# combined-v2.net
KiCad netlist of a schematic drawn in EAGLE
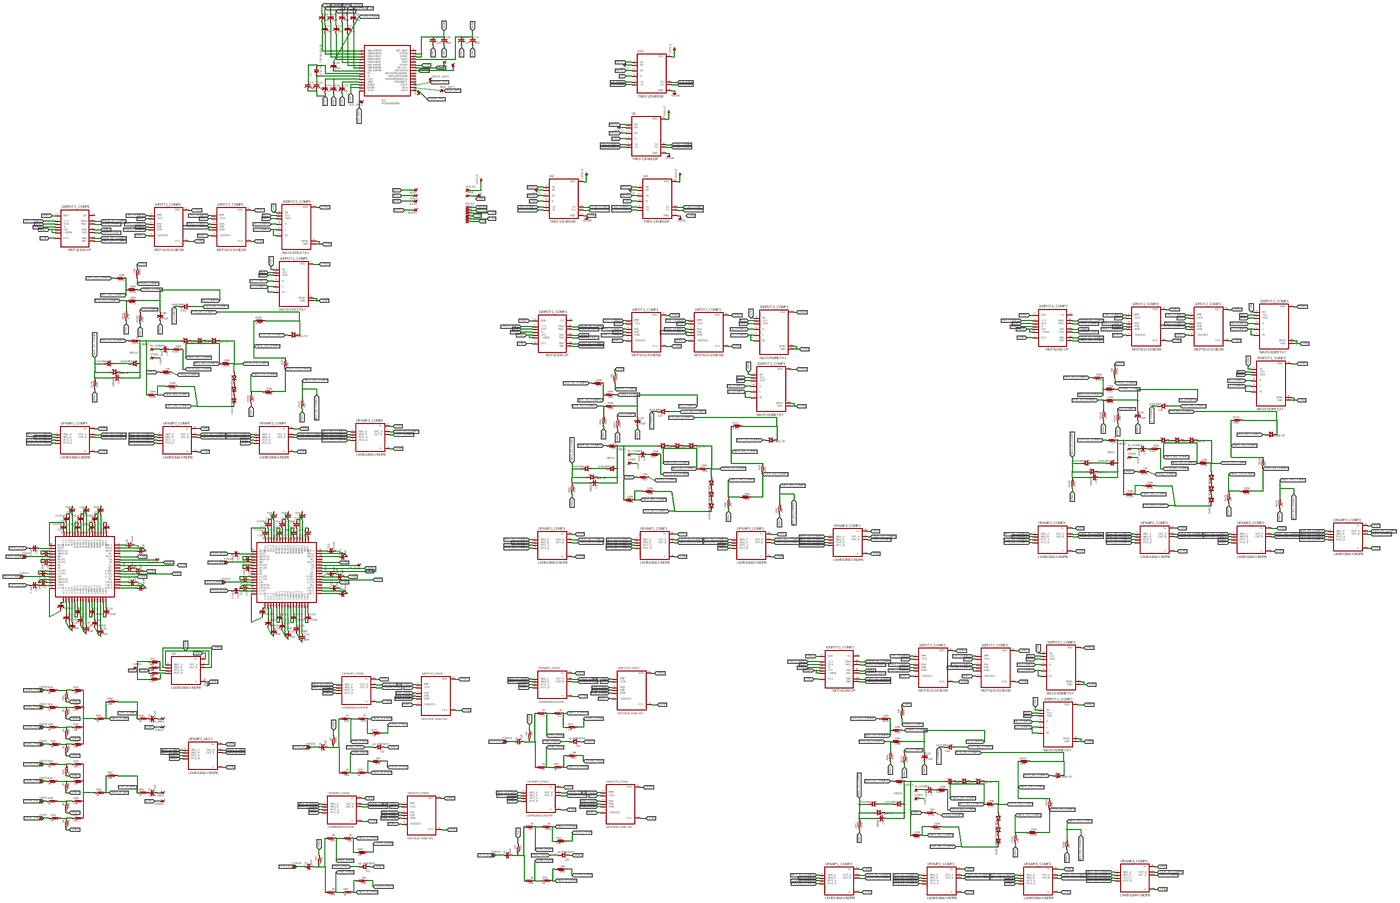
[diagram p0: schematic, sheet 1, overview]
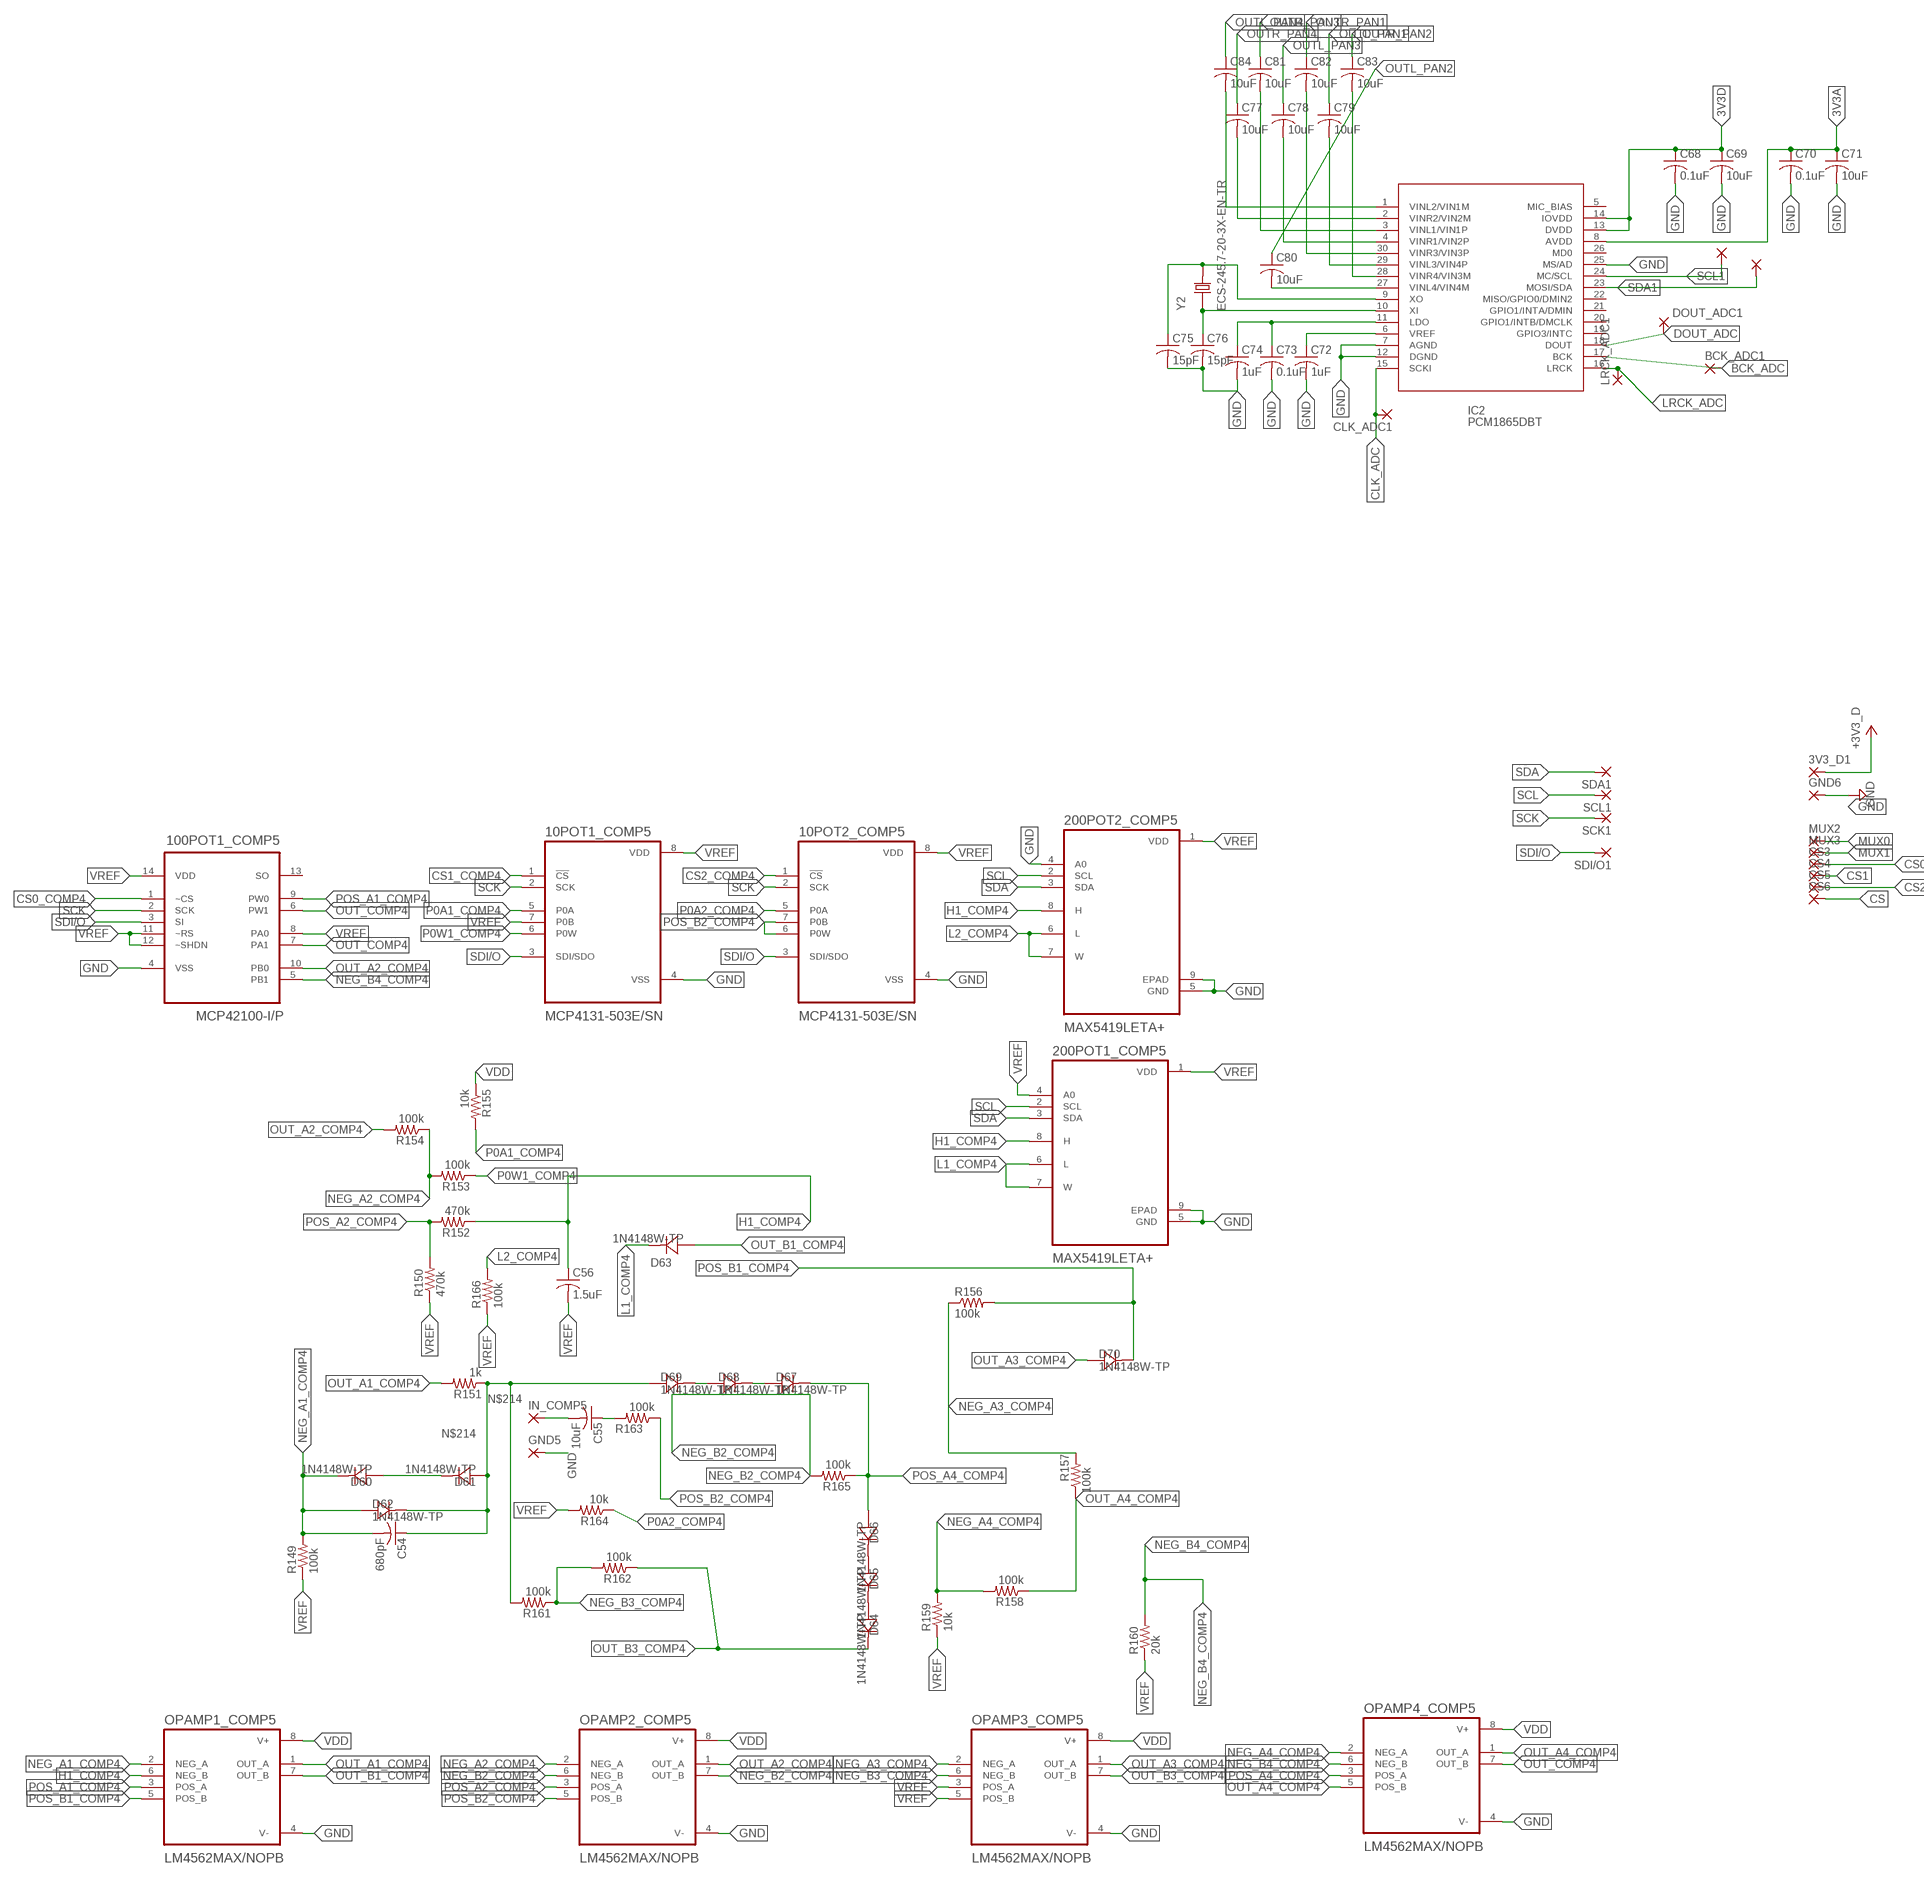
[diagram p1: schematic, sheet 1, part 1 of 5]
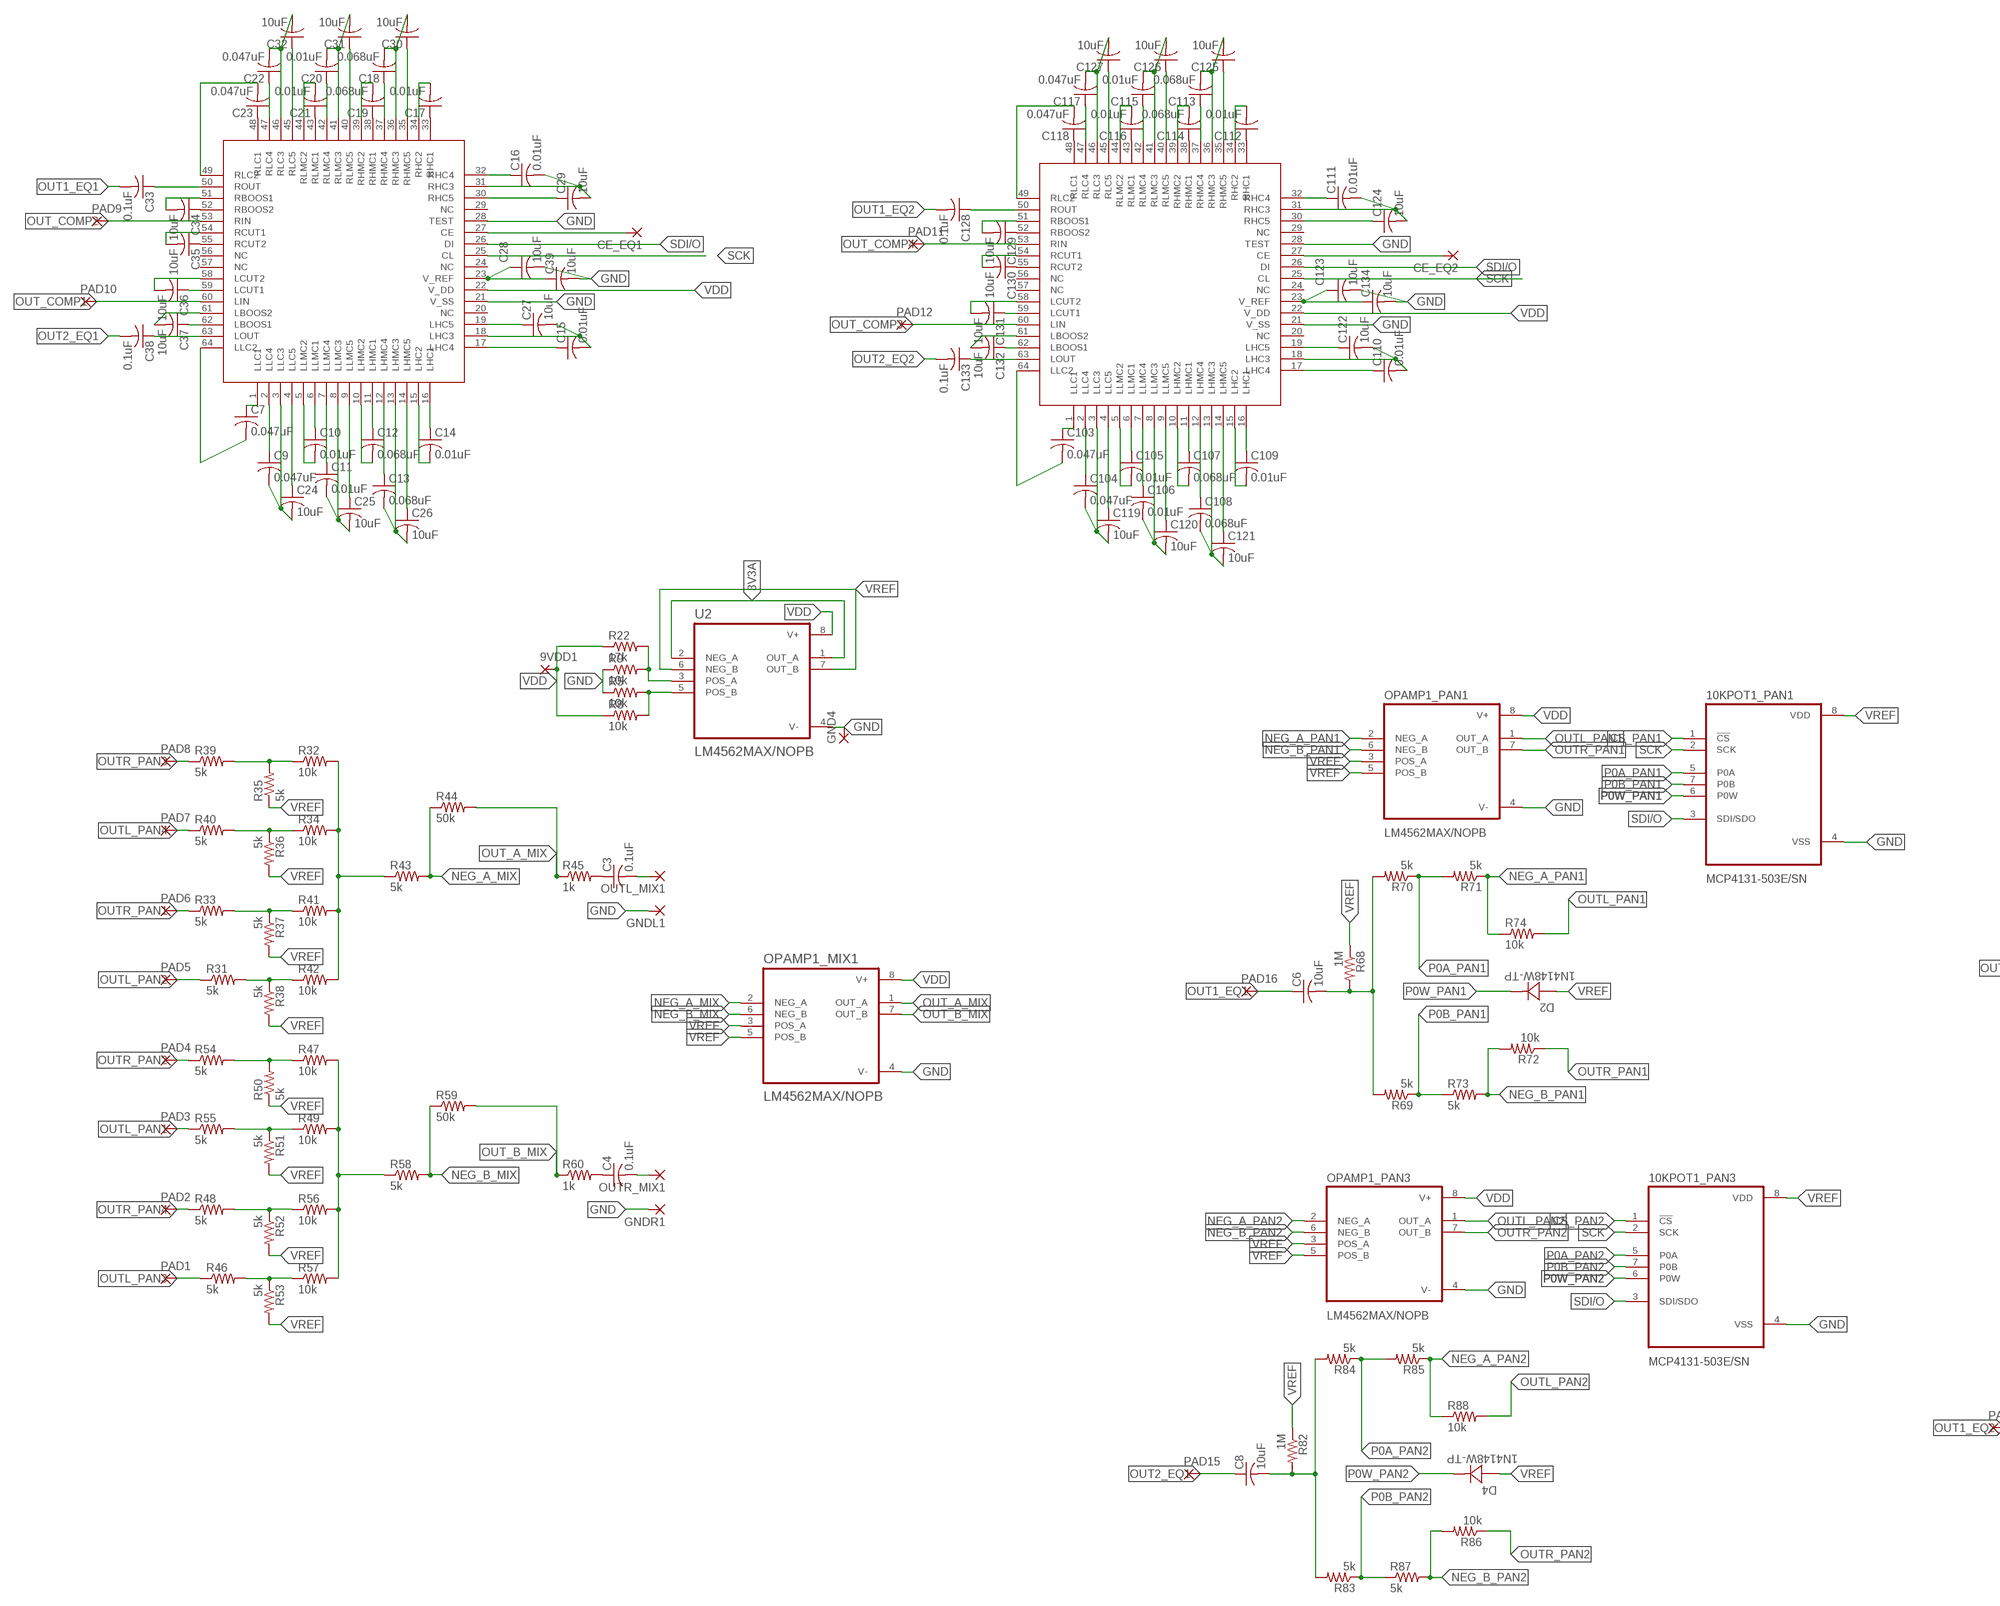
[diagram p2: schematic, sheet 1, part 2 of 5]
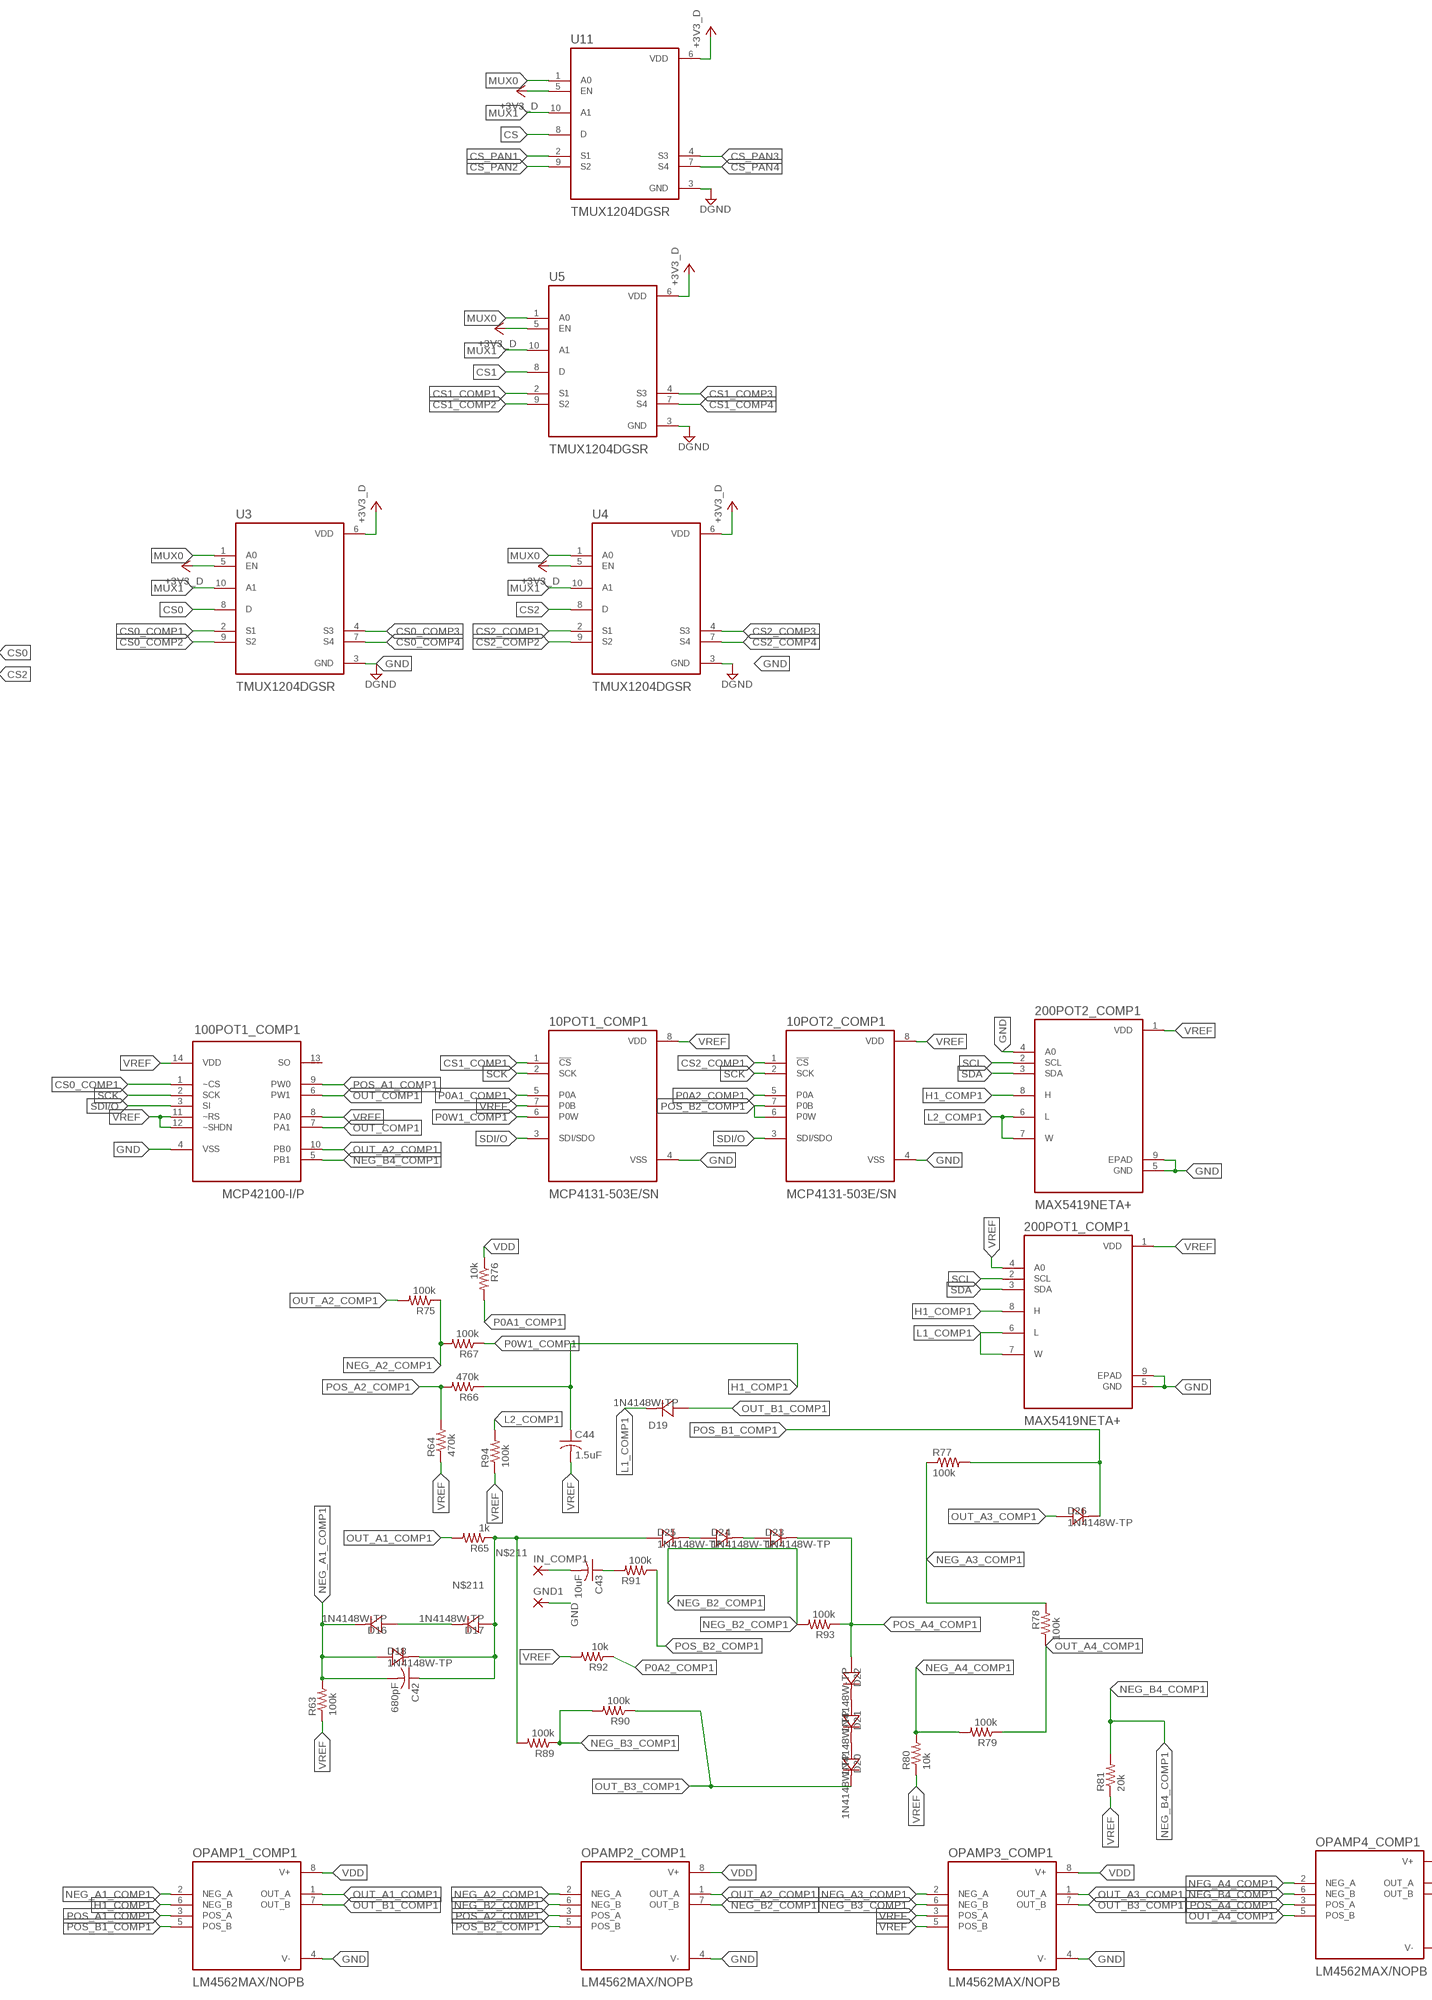
[diagram p3: schematic, sheet 1, part 3 of 5]
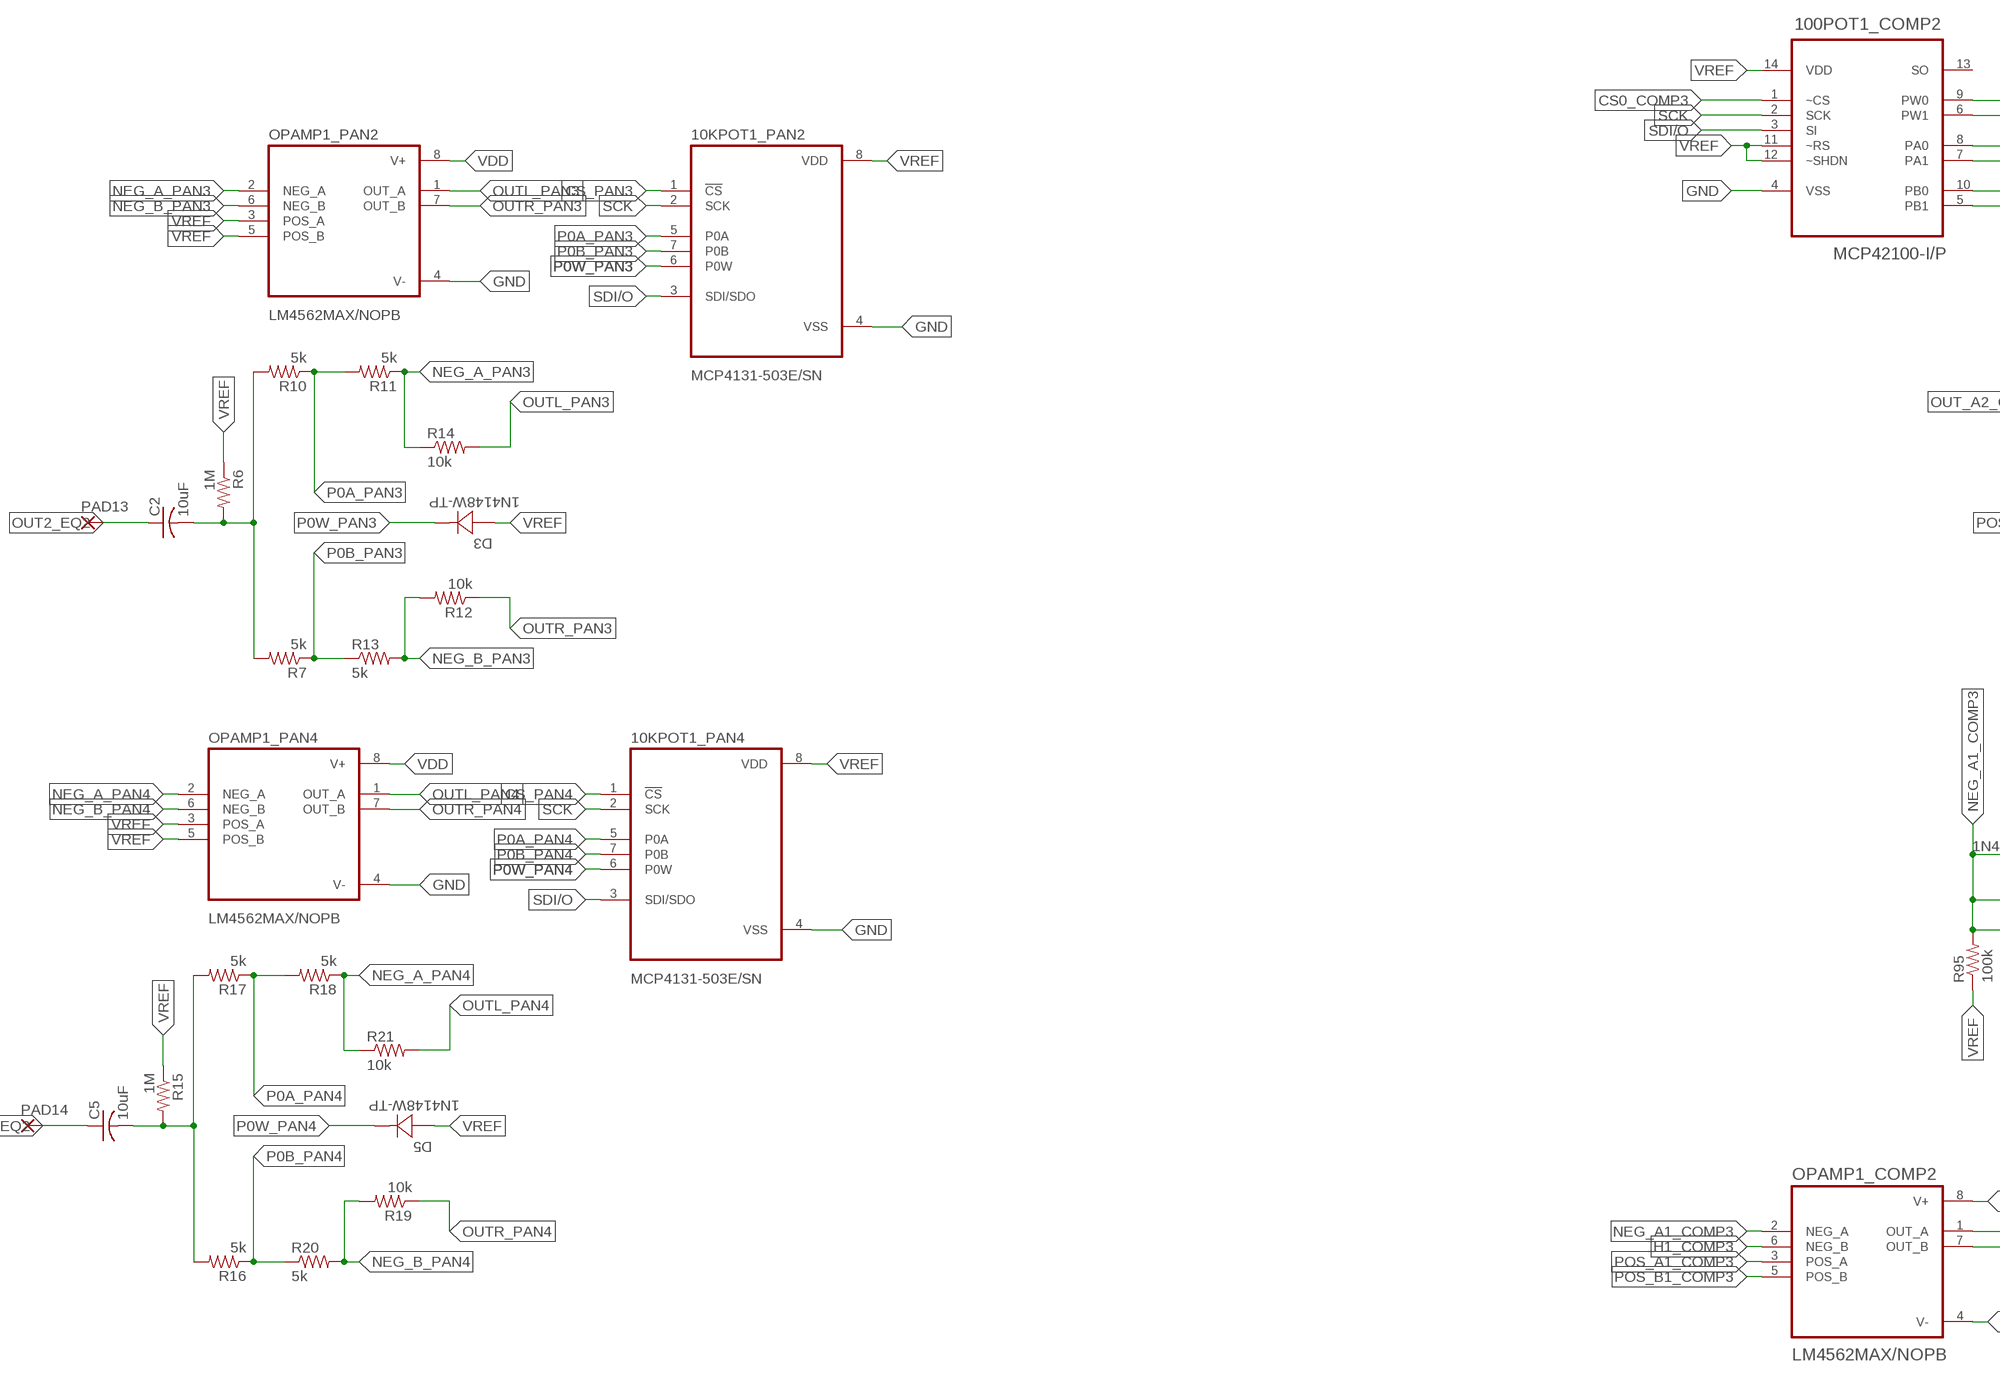
[diagram p4: schematic, sheet 1, part 4 of 5]
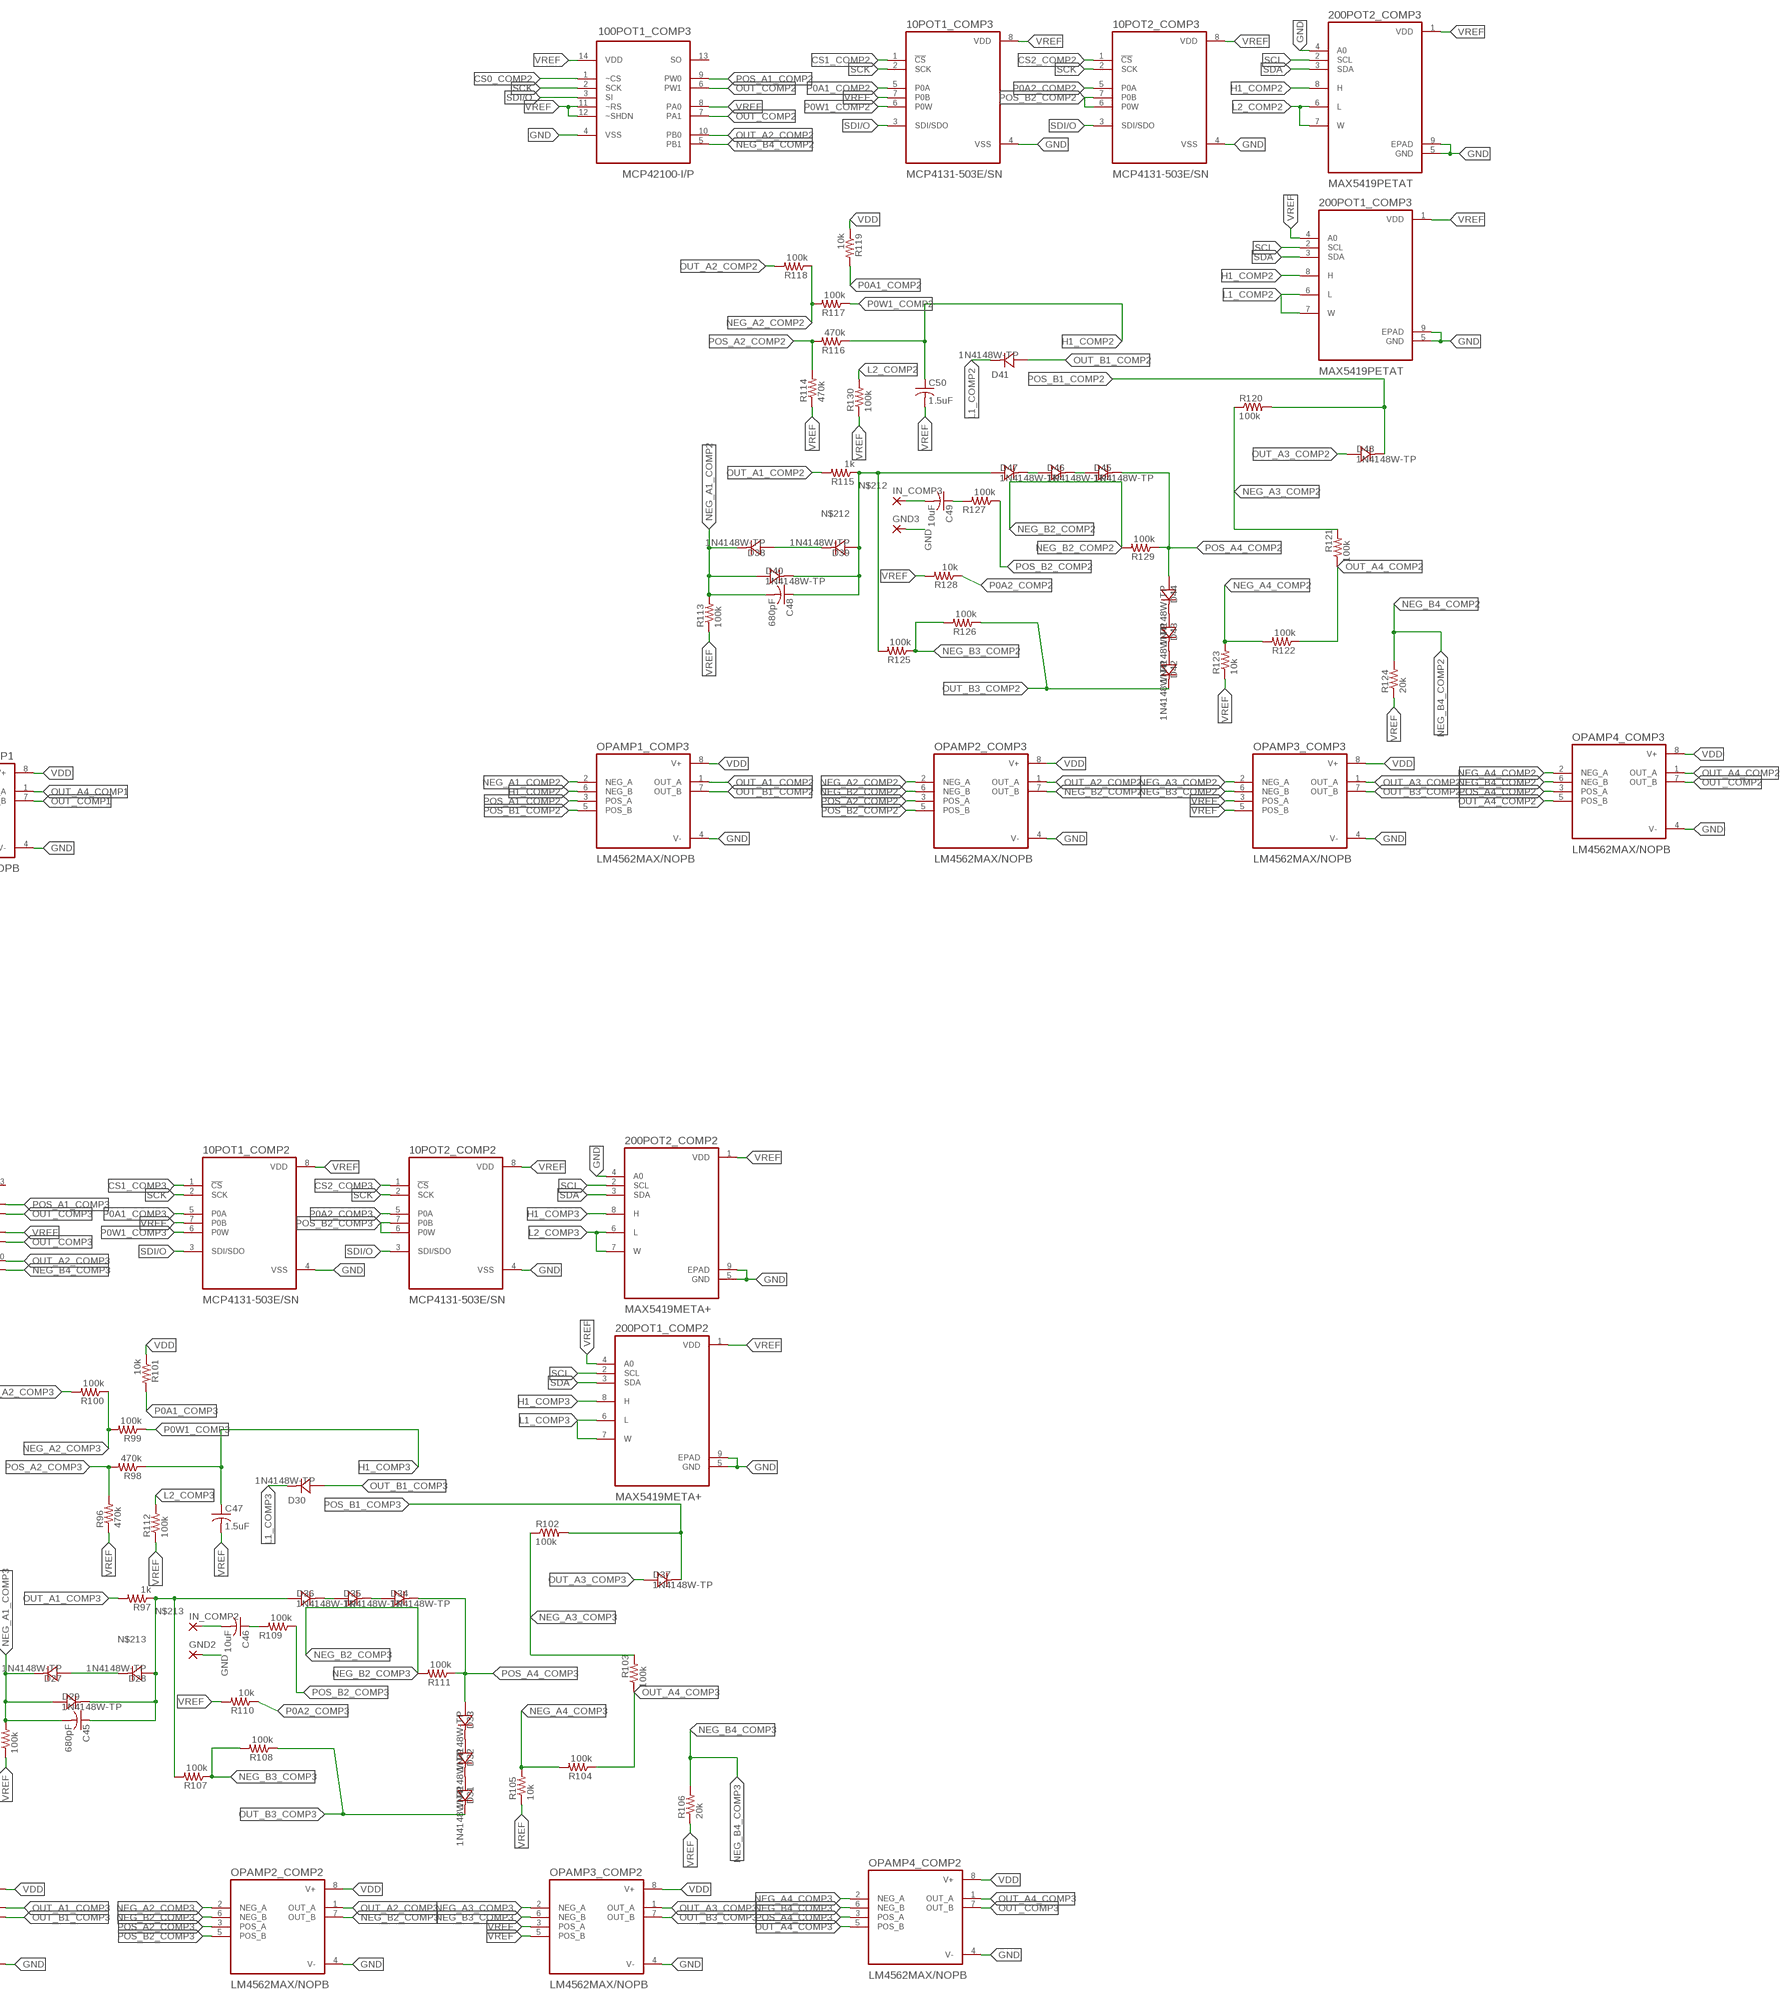
[diagram p5: schematic, sheet 1, part 5 of 5]

(export (version "E")
  (design (tool "Eeschema 10.0.6"))
  (components
    (comp (ref "3V3_D1")
      (value "SMD2")
      (footprint "eagle-import:SMD1,27-2,54")
      (libsource (lib "eagle-import") (part "SMD2"))
    )
    (comp (ref "9VDD1")
      (value "SMD2")
      (footprint "eagle-import:SMD1,27-2,54")
      (libsource (lib "eagle-import") (part "SMD2"))
    )
    (comp (ref "10KPOT1_PAN1")
      (value "MCP4131-503E/SN")
      (footprint "eagle-import:SOIC127P599X175-8N")
      (fields (field (name "MF") "Microchip") (field (name "SPICEPREFIX") "X"))
      (libsource (lib "eagle-import") (part "MCP4131-503E/SN"))
    )
    (comp (ref "10KPOT1_PAN2")
      (value "MCP4131-503E/SN")
      (footprint "eagle-import:SOIC127P599X175-8N")
      (fields (field (name "MF") "Microchip") (field (name "SPICEPREFIX") "X"))
      (libsource (lib "eagle-import") (part "MCP4131-503E/SN"))
    )
    (comp (ref "10KPOT1_PAN3")
      (value "MCP4131-503E/SN")
      (footprint "eagle-import:SOIC127P599X175-8N")
      (fields (field (name "MF") "Microchip") (field (name "SPICEPREFIX") "X"))
      (libsource (lib "eagle-import") (part "MCP4131-503E/SN"))
    )
    (comp (ref "10KPOT1_PAN4")
      (value "MCP4131-503E/SN")
      (footprint "eagle-import:SOIC127P599X175-8N")
      (fields (field (name "MF") "Microchip") (field (name "SPICEPREFIX") "X"))
      (libsource (lib "eagle-import") (part "MCP4131-503E/SN"))
    )
    (comp (ref "10POT1_COMP1")
      (value "MCP4131-503E/SN")
      (footprint "eagle-import:SOIC127P599X175-8N")
      (fields (field (name "MF") "Microchip"))
      (libsource (lib "eagle-import") (part "MCP4131-503E/SN"))
    )
    (comp (ref "10POT1_COMP2")
      (value "MCP4131-503E/SN")
      (footprint "eagle-import:SOIC127P599X175-8N")
      (fields (field (name "MF") "Microchip"))
      (libsource (lib "eagle-import") (part "MCP4131-503E/SN"))
    )
    (comp (ref "10POT1_COMP3")
      (value "MCP4131-503E/SN")
      (footprint "eagle-import:SOIC127P599X175-8N")
      (fields (field (name "MF") "Microchip"))
      (libsource (lib "eagle-import") (part "MCP4131-503E/SN"))
    )
    (comp (ref "10POT1_COMP5")
      (value "MCP4131-503E/SN")
      (footprint "eagle-import:SOIC127P599X175-8N")
      (fields (field (name "MF") "Microchip"))
      (libsource (lib "eagle-import") (part "MCP4131-503E/SN"))
    )
    (comp (ref "10POT2_COMP1")
      (value "MCP4131-503E/SN")
      (footprint "eagle-import:SOIC127P599X175-8N")
      (fields (field (name "MF") "Microchip"))
      (libsource (lib "eagle-import") (part "MCP4131-503E/SN"))
    )
    (comp (ref "10POT2_COMP2")
      (value "MCP4131-503E/SN")
      (footprint "eagle-import:SOIC127P599X175-8N")
      (fields (field (name "MF") "Microchip"))
      (libsource (lib "eagle-import") (part "MCP4131-503E/SN"))
    )
    (comp (ref "10POT2_COMP3")
      (value "MCP4131-503E/SN")
      (footprint "eagle-import:SOIC127P599X175-8N")
      (fields (field (name "MF") "Microchip"))
      (libsource (lib "eagle-import") (part "MCP4131-503E/SN"))
    )
    (comp (ref "10POT2_COMP5")
      (value "MCP4131-503E/SN")
      (footprint "eagle-import:SOIC127P599X175-8N")
      (fields (field (name "MF") "Microchip"))
      (libsource (lib "eagle-import") (part "MCP4131-503E/SN"))
    )
    (comp (ref "100POT1_COMP1")
      (value "MCP42100-I/P")
      (footprint "eagle-import:DIP254P762X432-14")
      (fields (field (name "MF") "Microchip"))
      (libsource (lib "eagle-import") (part "MCP42100-I/P"))
    )
    (comp (ref "100POT1_COMP2")
      (value "MCP42100-I/P")
      (footprint "eagle-import:DIP254P762X432-14")
      (fields (field (name "MF") "Microchip"))
      (libsource (lib "eagle-import") (part "MCP42100-I/P"))
    )
    (comp (ref "100POT1_COMP3")
      (value "MCP42100-I/P")
      (footprint "eagle-import:DIP254P762X432-14")
      (fields (field (name "MF") "Microchip"))
      (libsource (lib "eagle-import") (part "MCP42100-I/P"))
    )
    (comp (ref "100POT1_COMP5")
      (value "MCP42100-I/P")
      (footprint "eagle-import:DIP254P762X432-14")
      (fields (field (name "MF") "Microchip"))
      (libsource (lib "eagle-import") (part "MCP42100-I/P"))
    )
    (comp (ref "200POT1_COMP1")
      (value "MAX5419NETA+")
      (footprint "eagle-import:SON65P300X300X80-9N")
      (fields (field (name "MF") "Analog Devices"))
      (libsource (lib "eagle-import") (part "MAX5419NETA+"))
    )
    (comp (ref "200POT1_COMP2")
      (value "MAX5419META+")
      (footprint "eagle-import:SON65P300X300X80-9N")
      (fields (field (name "MF") "Analog Devices") (field (name "MP") "MAX5419LETA+"))
      (libsource (lib "eagle-import") (part "MAX5419META+"))
    )
    (comp (ref "200POT1_COMP3")
      (value "MAX5419PETAT")
      (footprint "eagle-import:SON65P300X300X80-9N")
      (fields (field (name "MF") "Analog Devices") (field (name "MP") "MAX5419PETA+"))
      (libsource (lib "eagle-import") (part "MAX5419PETAT"))
    )
    (comp (ref "200POT1_COMP5")
      (value "MAX5419LETA+")
      (footprint "eagle-import:SON65P300X300X80-9N")
      (fields (field (name "MF") "Analog Devices"))
      (libsource (lib "eagle-import") (part "MAX5419LETA+"))
    )
    (comp (ref "200POT2_COMP1")
      (value "MAX5419NETA+")
      (footprint "eagle-import:SON65P300X300X80-9N")
      (fields (field (name "MF") "Analog Devices"))
      (libsource (lib "eagle-import") (part "MAX5419NETA+"))
    )
    (comp (ref "200POT2_COMP2")
      (value "MAX5419META+")
      (footprint "eagle-import:SON65P300X300X80-9N")
      (fields (field (name "MF") "Analog Devices") (field (name "MP") "MAX5419LETA+"))
      (libsource (lib "eagle-import") (part "MAX5419META+"))
    )
    (comp (ref "200POT2_COMP3")
      (value "MAX5419PETAT")
      (footprint "eagle-import:SON65P300X300X80-9N")
      (fields (field (name "MF") "Analog Devices") (field (name "MP") "MAX5419PETA+"))
      (libsource (lib "eagle-import") (part "MAX5419PETAT"))
    )
    (comp (ref "200POT2_COMP5")
      (value "MAX5419LETA+")
      (footprint "eagle-import:SON65P300X300X80-9N")
      (fields (field (name "MF") "Analog Devices"))
      (libsource (lib "eagle-import") (part "MAX5419LETA+"))
    )
    (comp (ref "BCK_ADC1")
      (value "SMD2")
      (footprint "eagle-import:SMD1,27-2,54")
      (libsource (lib "eagle-import") (part "SMD2"))
    )
    (comp (ref "C2")
      (value "10uF")
      (footprint "eagle-import:C0402")
      (libsource (lib "eagle-import") (part "C-USC0402"))
    )
    (comp (ref "C3")
      (value "0.1uF")
      (footprint "eagle-import:C0402")
      (libsource (lib "eagle-import") (part "C-USC0402"))
    )
    (comp (ref "C4")
      (value "0.1uF")
      (footprint "eagle-import:C0402")
      (libsource (lib "eagle-import") (part "C-USC0402"))
    )
    (comp (ref "C5")
      (value "10uF")
      (footprint "eagle-import:C0402")
      (libsource (lib "eagle-import") (part "C-USC0402"))
    )
    (comp (ref "C6")
      (value "10uF")
      (footprint "eagle-import:C0402")
      (libsource (lib "eagle-import") (part "C-USC0402"))
    )
    (comp (ref "C7")
      (value "0.047uF")
      (footprint "eagle-import:C0402")
      (libsource (lib "eagle-import") (part "C-USC0402"))
    )
    (comp (ref "C8")
      (value "10uF")
      (footprint "eagle-import:C0402")
      (libsource (lib "eagle-import") (part "C-USC0402"))
    )
    (comp (ref "C9")
      (value "0.047uF")
      (footprint "eagle-import:C0402")
      (libsource (lib "eagle-import") (part "C-USC0402"))
    )
    (comp (ref "C10")
      (value "0.01uF")
      (footprint "eagle-import:C0402")
      (libsource (lib "eagle-import") (part "C-USC0402"))
    )
    (comp (ref "C11")
      (value "0.01uF")
      (footprint "eagle-import:C0402")
      (libsource (lib "eagle-import") (part "C-USC0402"))
    )
    (comp (ref "C12")
      (value "0.068uF")
      (footprint "eagle-import:C0402")
      (libsource (lib "eagle-import") (part "C-USC0402"))
    )
    (comp (ref "C13")
      (value "0.068uF")
      (footprint "eagle-import:C0402")
      (libsource (lib "eagle-import") (part "C-USC0402"))
    )
    (comp (ref "C14")
      (value "0.01uF")
      (footprint "eagle-import:C0402")
      (libsource (lib "eagle-import") (part "C-USC0402"))
    )
    (comp (ref "C15")
      (value "0.01uF")
      (footprint "eagle-import:C0402")
      (libsource (lib "eagle-import") (part "C-USC0402"))
    )
    (comp (ref "C16")
      (value "0.01uF")
      (footprint "eagle-import:C0402")
      (libsource (lib "eagle-import") (part "C-USC0402"))
    )
    (comp (ref "C17")
      (value "0.01uF")
      (footprint "eagle-import:C0402")
      (libsource (lib "eagle-import") (part "C-USC0402"))
    )
    (comp (ref "C18")
      (value "0.068uF")
      (footprint "eagle-import:C0402")
      (libsource (lib "eagle-import") (part "C-USC0402"))
    )
    (comp (ref "C19")
      (value "0.068uF")
      (footprint "eagle-import:C0402")
      (libsource (lib "eagle-import") (part "C-USC0402"))
    )
    (comp (ref "C20")
      (value "0.01uF")
      (footprint "eagle-import:C0402")
      (libsource (lib "eagle-import") (part "C-USC0402"))
    )
    (comp (ref "C21")
      (value "0.01uF")
      (footprint "eagle-import:C0402")
      (libsource (lib "eagle-import") (part "C-USC0402"))
    )
    (comp (ref "C22")
      (value "0.047uF")
      (footprint "eagle-import:C0402")
      (libsource (lib "eagle-import") (part "C-USC0402"))
    )
    (comp (ref "C23")
      (value "0.047uF")
      (footprint "eagle-import:C0402")
      (libsource (lib "eagle-import") (part "C-USC0402"))
    )
    (comp (ref "C24")
      (value "10uF")
      (footprint "eagle-import:C0402")
      (libsource (lib "eagle-import") (part "C-USC0402"))
    )
    (comp (ref "C25")
      (value "10uF")
      (footprint "eagle-import:C0402")
      (libsource (lib "eagle-import") (part "C-USC0402"))
    )
    (comp (ref "C26")
      (value "10uF")
      (footprint "eagle-import:C0402")
      (libsource (lib "eagle-import") (part "C-USC0402"))
    )
    (comp (ref "C27")
      (value "10uF")
      (footprint "eagle-import:C0402")
      (libsource (lib "eagle-import") (part "C-USC0402"))
    )
    (comp (ref "C28")
      (value "10uF")
      (footprint "eagle-import:C0402")
      (libsource (lib "eagle-import") (part "C-USC0402"))
    )
    (comp (ref "C29")
      (value "10uF")
      (footprint "eagle-import:C0402")
      (libsource (lib "eagle-import") (part "C-USC0402"))
    )
    (comp (ref "C30")
      (value "10uF")
      (footprint "eagle-import:C0402")
      (libsource (lib "eagle-import") (part "C-USC0402"))
    )
    (comp (ref "C31")
      (value "10uF")
      (footprint "eagle-import:C0402")
      (libsource (lib "eagle-import") (part "C-USC0402"))
    )
    (comp (ref "C32")
      (value "10uF")
      (footprint "eagle-import:C0402")
      (libsource (lib "eagle-import") (part "C-USC0402"))
    )
    (comp (ref "C33")
      (value "0.1uF")
      (footprint "eagle-import:C0402")
      (libsource (lib "eagle-import") (part "C-USC0402"))
    )
    (comp (ref "C34")
      (value "10uF")
      (footprint "eagle-import:C0402")
      (libsource (lib "eagle-import") (part "C-USC0402"))
    )
    (comp (ref "C35")
      (value "10uF")
      (footprint "eagle-import:C0402")
      (libsource (lib "eagle-import") (part "C-USC0402"))
    )
    (comp (ref "C36")
      (value "10uF")
      (footprint "eagle-import:C0402")
      (libsource (lib "eagle-import") (part "C-USC0402"))
    )
    (comp (ref "C37")
      (value "10uF")
      (footprint "eagle-import:C0402")
      (libsource (lib "eagle-import") (part "C-USC0402"))
    )
    (comp (ref "C38")
      (value "0.1uF")
      (footprint "eagle-import:C0402")
      (libsource (lib "eagle-import") (part "C-USC0402"))
    )
    (comp (ref "C39")
      (value "10uF")
      (footprint "eagle-import:C0402")
      (libsource (lib "eagle-import") (part "C-USC0402"))
    )
    (comp (ref "C42")
      (value "680pF")
      (footprint "eagle-import:C0402")
      (libsource (lib "eagle-import") (part "C-USC0402"))
    )
    (comp (ref "C43")
      (value "10uF")
      (footprint "eagle-import:C0402")
      (libsource (lib "eagle-import") (part "C-USC0402"))
    )
    (comp (ref "C44")
      (value "1.5uF")
      (footprint "eagle-import:C0402")
      (libsource (lib "eagle-import") (part "C-USC0402"))
    )
    (comp (ref "C45")
      (value "680pF")
      (footprint "eagle-import:C0402")
      (libsource (lib "eagle-import") (part "C-USC0402"))
    )
    (comp (ref "C46")
      (value "10uF")
      (footprint "eagle-import:C0402")
      (libsource (lib "eagle-import") (part "C-USC0402"))
    )
    (comp (ref "C47")
      (value "1.5uF")
      (footprint "eagle-import:C0402")
      (libsource (lib "eagle-import") (part "C-USC0402"))
    )
    (comp (ref "C48")
      (value "680pF")
      (footprint "eagle-import:C0402")
      (libsource (lib "eagle-import") (part "C-USC0402"))
    )
    (comp (ref "C49")
      (value "10uF")
      (footprint "eagle-import:C0402")
      (libsource (lib "eagle-import") (part "C-USC0402"))
    )
    (comp (ref "C50")
      (value "1.5uF")
      (footprint "eagle-import:C0402")
      (libsource (lib "eagle-import") (part "C-USC0402"))
    )
    (comp (ref "C54")
      (value "680pF")
      (footprint "eagle-import:C0402")
      (libsource (lib "eagle-import") (part "C-USC0402"))
    )
    (comp (ref "C55")
      (value "10uF")
      (footprint "eagle-import:C0402")
      (libsource (lib "eagle-import") (part "C-USC0402"))
    )
    (comp (ref "C56")
      (value "1.5uF")
      (footprint "eagle-import:C0402")
      (libsource (lib "eagle-import") (part "C-USC0402"))
    )
    (comp (ref "C68")
      (value "0.1uF")
      (footprint "eagle-import:C0402")
      (libsource (lib "eagle-import") (part "C-USC0402"))
    )
    (comp (ref "C69")
      (value "10uF")
      (footprint "eagle-import:C0402")
      (libsource (lib "eagle-import") (part "C-USC0402"))
    )
    (comp (ref "C70")
      (value "0.1uF")
      (footprint "eagle-import:C0402")
      (libsource (lib "eagle-import") (part "C-USC0402"))
    )
    (comp (ref "C71")
      (value "10uF")
      (footprint "eagle-import:C0402")
      (libsource (lib "eagle-import") (part "C-USC0402"))
    )
    (comp (ref "C72")
      (value "1uF")
      (footprint "eagle-import:C0402")
      (libsource (lib "eagle-import") (part "C-USC0402"))
    )
    (comp (ref "C73")
      (value "0.1uF")
      (footprint "eagle-import:C0402")
      (libsource (lib "eagle-import") (part "C-USC0402"))
    )
    (comp (ref "C74")
      (value "1uF")
      (footprint "eagle-import:C0402")
      (libsource (lib "eagle-import") (part "C-USC0402"))
    )
    (comp (ref "C75")
      (value "15pF")
      (footprint "eagle-import:C0402")
      (libsource (lib "eagle-import") (part "C-USC0402"))
    )
    (comp (ref "C76")
      (value "15pF")
      (footprint "eagle-import:C0402")
      (libsource (lib "eagle-import") (part "C-USC0402"))
    )
    (comp (ref "C77")
      (value "10uF")
      (footprint "eagle-import:C0402")
      (libsource (lib "eagle-import") (part "C-USC0402"))
    )
    (comp (ref "C78")
      (value "10uF")
      (footprint "eagle-import:C0402")
      (libsource (lib "eagle-import") (part "C-USC0402"))
    )
    (comp (ref "C79")
      (value "10uF")
      (footprint "eagle-import:C0402")
      (libsource (lib "eagle-import") (part "C-USC0402"))
    )
    (comp (ref "C80")
      (value "10uF")
      (footprint "eagle-import:C0402")
      (libsource (lib "eagle-import") (part "C-USC0402"))
    )
    (comp (ref "C81")
      (value "10uF")
      (footprint "eagle-import:C0402")
      (libsource (lib "eagle-import") (part "C-USC0402"))
    )
    (comp (ref "C82")
      (value "10uF")
      (footprint "eagle-import:C0402")
      (libsource (lib "eagle-import") (part "C-USC0402"))
    )
    (comp (ref "C83")
      (value "10uF")
      (footprint "eagle-import:C0402")
      (libsource (lib "eagle-import") (part "C-USC0402"))
    )
    (comp (ref "C84")
      (value "10uF")
      (footprint "eagle-import:C0402")
      (libsource (lib "eagle-import") (part "C-USC0402"))
    )
    (comp (ref "C103")
      (value "0.047uF")
      (footprint "eagle-import:C0402")
      (libsource (lib "eagle-import") (part "C-USC0402"))
    )
    (comp (ref "C104")
      (value "0.047uF")
      (footprint "eagle-import:C0402")
      (libsource (lib "eagle-import") (part "C-USC0402"))
    )
    (comp (ref "C105")
      (value "0.01uF")
      (footprint "eagle-import:C0402")
      (libsource (lib "eagle-import") (part "C-USC0402"))
    )
    (comp (ref "C106")
      (value "0.01uF")
      (footprint "eagle-import:C0402")
      (libsource (lib "eagle-import") (part "C-USC0402"))
    )
    (comp (ref "C107")
      (value "0.068uF")
      (footprint "eagle-import:C0402")
      (libsource (lib "eagle-import") (part "C-USC0402"))
    )
    (comp (ref "C108")
      (value "0.068uF")
      (footprint "eagle-import:C0402")
      (libsource (lib "eagle-import") (part "C-USC0402"))
    )
    (comp (ref "C109")
      (value "0.01uF")
      (footprint "eagle-import:C0402")
      (libsource (lib "eagle-import") (part "C-USC0402"))
    )
    (comp (ref "C110")
      (value "0.01uF")
      (footprint "eagle-import:C0402")
      (libsource (lib "eagle-import") (part "C-USC0402"))
    )
    (comp (ref "C111")
      (value "0.01uF")
      (footprint "eagle-import:C0402")
      (libsource (lib "eagle-import") (part "C-USC0402"))
    )
    (comp (ref "C112")
      (value "0.01uF")
      (footprint "eagle-import:C0402")
      (libsource (lib "eagle-import") (part "C-USC0402"))
    )
    (comp (ref "C113")
      (value "0.068uF")
      (footprint "eagle-import:C0402")
      (libsource (lib "eagle-import") (part "C-USC0402"))
    )
    (comp (ref "C114")
      (value "0.068uF")
      (footprint "eagle-import:C0402")
      (libsource (lib "eagle-import") (part "C-USC0402"))
    )
    (comp (ref "C115")
      (value "0.01uF")
      (footprint "eagle-import:C0402")
      (libsource (lib "eagle-import") (part "C-USC0402"))
    )
    (comp (ref "C116")
      (value "0.01uF")
      (footprint "eagle-import:C0402")
      (libsource (lib "eagle-import") (part "C-USC0402"))
    )
    (comp (ref "C117")
      (value "0.047uF")
      (footprint "eagle-import:C0402")
      (libsource (lib "eagle-import") (part "C-USC0402"))
    )
    (comp (ref "C118")
      (value "0.047uF")
      (footprint "eagle-import:C0402")
      (libsource (lib "eagle-import") (part "C-USC0402"))
    )
    (comp (ref "C119")
      (value "10uF")
      (footprint "eagle-import:C0402")
      (libsource (lib "eagle-import") (part "C-USC0402"))
    )
    (comp (ref "C120")
      (value "10uF")
      (footprint "eagle-import:C0402")
      (libsource (lib "eagle-import") (part "C-USC0402"))
    )
    (comp (ref "C121")
      (value "10uF")
      (footprint "eagle-import:C0402")
      (libsource (lib "eagle-import") (part "C-USC0402"))
    )
    (comp (ref "C122")
      (value "10uF")
      (footprint "eagle-import:C0402")
      (libsource (lib "eagle-import") (part "C-USC0402"))
    )
    (comp (ref "C123")
      (value "10uF")
      (footprint "eagle-import:C0402")
      (libsource (lib "eagle-import") (part "C-USC0402"))
    )
    (comp (ref "C124")
      (value "10uF")
      (footprint "eagle-import:C0402")
      (libsource (lib "eagle-import") (part "C-USC0402"))
    )
    (comp (ref "C125")
      (value "10uF")
      (footprint "eagle-import:C0402")
      (libsource (lib "eagle-import") (part "C-USC0402"))
    )
    (comp (ref "C126")
      (value "10uF")
      (footprint "eagle-import:C0402")
      (libsource (lib "eagle-import") (part "C-USC0402"))
    )
    (comp (ref "C127")
      (value "10uF")
      (footprint "eagle-import:C0402")
      (libsource (lib "eagle-import") (part "C-USC0402"))
    )
    (comp (ref "C128")
      (value "0.1uF")
      (footprint "eagle-import:C0402")
      (libsource (lib "eagle-import") (part "C-USC0402"))
    )
    (comp (ref "C129")
      (value "10uF")
      (footprint "eagle-import:C0402")
      (libsource (lib "eagle-import") (part "C-USC0402"))
    )
    (comp (ref "C130")
      (value "10uF")
      (footprint "eagle-import:C0402")
      (libsource (lib "eagle-import") (part "C-USC0402"))
    )
    (comp (ref "C131")
      (value "10uF")
      (footprint "eagle-import:C0402")
      (libsource (lib "eagle-import") (part "C-USC0402"))
    )
    (comp (ref "C132")
      (value "10uF")
      (footprint "eagle-import:C0402")
      (libsource (lib "eagle-import") (part "C-USC0402"))
    )
    (comp (ref "C133")
      (value "0.1uF")
      (footprint "eagle-import:C0402")
      (libsource (lib "eagle-import") (part "C-USC0402"))
    )
    (comp (ref "C134")
      (value "10uF")
      (footprint "eagle-import:C0402")
      (libsource (lib "eagle-import") (part "C-USC0402"))
    )
    (comp (ref "CE_EQ1")
      (value "SMD2")
      (footprint "eagle-import:SMD1,27-2,54")
      (libsource (lib "eagle-import") (part "SMD2"))
    )
    (comp (ref "CE_EQ2")
      (value "SMD2")
      (footprint "eagle-import:SMD1,27-2,54")
      (libsource (lib "eagle-import") (part "SMD2"))
    )
    (comp (ref "CLK_ADC1")
      (value "SMD2")
      (footprint "eagle-import:SMD1,27-2,54")
      (libsource (lib "eagle-import") (part "SMD2"))
    )
    (comp (ref "CS3")
      (value "SMD2")
      (footprint "eagle-import:SMD1,27-2,54")
      (libsource (lib "eagle-import") (part "SMD2"))
    )
    (comp (ref "CS4")
      (value "SMD2")
      (footprint "eagle-import:SMD1,27-2,54")
      (libsource (lib "eagle-import") (part "SMD2"))
    )
    (comp (ref "CS5")
      (value "SMD2")
      (footprint "eagle-import:SMD1,27-2,54")
      (libsource (lib "eagle-import") (part "SMD2"))
    )
    (comp (ref "CS6")
      (value "SMD2")
      (footprint "eagle-import:SMD1,27-2,54")
      (libsource (lib "eagle-import") (part "SMD2"))
    )
    (comp (ref "D2")
      (value "1N4148W-TP")
      (footprint "eagle-import:SOD123")
      (fields (field (name "MF") "Diodes Inc.") (field (name "MP") "1N4148WTP"))
      (libsource (lib "eagle-import") (part "1N4148W-TP"))
    )
    (comp (ref "D3")
      (value "1N4148W-TP")
      (footprint "eagle-import:SOD123")
      (fields (field (name "MF") "Diodes Inc.") (field (name "MP") "1N4148WTP"))
      (libsource (lib "eagle-import") (part "1N4148W-TP"))
    )
    (comp (ref "D4")
      (value "1N4148W-TP")
      (footprint "eagle-import:SOD123")
      (fields (field (name "MF") "Diodes Inc.") (field (name "MP") "1N4148WTP"))
      (libsource (lib "eagle-import") (part "1N4148W-TP"))
    )
    (comp (ref "D5")
      (value "1N4148W-TP")
      (footprint "eagle-import:SOD123")
      (fields (field (name "MF") "Diodes Inc.") (field (name "MP") "1N4148WTP"))
      (libsource (lib "eagle-import") (part "1N4148W-TP"))
    )
    (comp (ref "D16")
      (value "1N4148W-TP")
      (footprint "eagle-import:SOD123")
      (fields (field (name "MF") "Diodes Inc.") (field (name "MP") "1N4148WTP"))
      (libsource (lib "eagle-import") (part "1N4148W-TP"))
    )
    (comp (ref "D17")
      (value "1N4148W-TP")
      (footprint "eagle-import:SOD123")
      (fields (field (name "MF") "Diodes Inc.") (field (name "MP") "1N4148WTP"))
      (libsource (lib "eagle-import") (part "1N4148W-TP"))
    )
    (comp (ref "D18")
      (value "1N4148W-TP")
      (footprint "eagle-import:SOD123")
      (fields (field (name "MF") "Diodes Inc.") (field (name "MP") "1N4148WTP"))
      (libsource (lib "eagle-import") (part "1N4148W-TP"))
    )
    (comp (ref "D19")
      (value "1N4148W-TP")
      (footprint "eagle-import:SOD123")
      (fields (field (name "MF") "Diodes Inc.") (field (name "MP") "1N4148WTP"))
      (libsource (lib "eagle-import") (part "1N4148W-TP"))
    )
    (comp (ref "D20")
      (value "1N4148W-TP")
      (footprint "eagle-import:SOD123")
      (fields (field (name "MF") "Diodes Inc.") (field (name "MP") "1N4148WTP"))
      (libsource (lib "eagle-import") (part "1N4148W-TP"))
    )
    (comp (ref "D21")
      (value "1N4148W-TP")
      (footprint "eagle-import:SOD123")
      (fields (field (name "MF") "Diodes Inc.") (field (name "MP") "1N4148WTP"))
      (libsource (lib "eagle-import") (part "1N4148W-TP"))
    )
    (comp (ref "D22")
      (value "1N4148W-TP")
      (footprint "eagle-import:SOD123")
      (fields (field (name "MF") "Diodes Inc.") (field (name "MP") "1N4148WTP"))
      (libsource (lib "eagle-import") (part "1N4148W-TP"))
    )
    (comp (ref "D23")
      (value "1N4148W-TP")
      (footprint "eagle-import:SOD123")
      (fields (field (name "MF") "Diodes Inc.") (field (name "MP") "1N4148WTP"))
      (libsource (lib "eagle-import") (part "1N4148W-TP"))
    )
    (comp (ref "D24")
      (value "1N4148W-TP")
      (footprint "eagle-import:SOD123")
      (fields (field (name "MF") "Diodes Inc.") (field (name "MP") "1N4148WTP"))
      (libsource (lib "eagle-import") (part "1N4148W-TP"))
    )
    (comp (ref "D25")
      (value "1N4148W-TP")
      (footprint "eagle-import:SOD123")
      (fields (field (name "MF") "Diodes Inc.") (field (name "MP") "1N4148WTP"))
      (libsource (lib "eagle-import") (part "1N4148W-TP"))
    )
    (comp (ref "D26")
      (value "1N4148W-TP")
      (footprint "eagle-import:SOD123")
      (fields (field (name "MF") "Diodes Inc.") (field (name "MP") "1N4148WTP"))
      (libsource (lib "eagle-import") (part "1N4148W-TP"))
    )
    (comp (ref "D27")
      (value "1N4148W-TP")
      (footprint "eagle-import:SOD123")
      (fields (field (name "MF") "Diodes Inc.") (field (name "MP") "1N4148WTP"))
      (libsource (lib "eagle-import") (part "1N4148W-TP"))
    )
    (comp (ref "D28")
      (value "1N4148W-TP")
      (footprint "eagle-import:SOD123")
      (fields (field (name "MF") "Diodes Inc.") (field (name "MP") "1N4148WTP"))
      (libsource (lib "eagle-import") (part "1N4148W-TP"))
    )
    (comp (ref "D29")
      (value "1N4148W-TP")
      (footprint "eagle-import:SOD123")
      (fields (field (name "MF") "Diodes Inc.") (field (name "MP") "1N4148WTP"))
      (libsource (lib "eagle-import") (part "1N4148W-TP"))
    )
    (comp (ref "D30")
      (value "1N4148W-TP")
      (footprint "eagle-import:SOD123")
      (fields (field (name "MF") "Diodes Inc.") (field (name "MP") "1N4148WTP"))
      (libsource (lib "eagle-import") (part "1N4148W-TP"))
    )
    (comp (ref "D31")
      (value "1N4148W-TP")
      (footprint "eagle-import:SOD123")
      (fields (field (name "MF") "Diodes Inc.") (field (name "MP") "1N4148WTP"))
      (libsource (lib "eagle-import") (part "1N4148W-TP"))
    )
    (comp (ref "D32")
      (value "1N4148W-TP")
      (footprint "eagle-import:SOD123")
      (fields (field (name "MF") "Diodes Inc.") (field (name "MP") "1N4148WTP"))
      (libsource (lib "eagle-import") (part "1N4148W-TP"))
    )
    (comp (ref "D33")
      (value "1N4148W-TP")
      (footprint "eagle-import:SOD123")
      (fields (field (name "MF") "Diodes Inc.") (field (name "MP") "1N4148WTP"))
      (libsource (lib "eagle-import") (part "1N4148W-TP"))
    )
    (comp (ref "D34")
      (value "1N4148W-TP")
      (footprint "eagle-import:SOD123")
      (fields (field (name "MF") "Diodes Inc.") (field (name "MP") "1N4148WTP"))
      (libsource (lib "eagle-import") (part "1N4148W-TP"))
    )
    (comp (ref "D35")
      (value "1N4148W-TP")
      (footprint "eagle-import:SOD123")
      (fields (field (name "MF") "Diodes Inc.") (field (name "MP") "1N4148WTP"))
      (libsource (lib "eagle-import") (part "1N4148W-TP"))
    )
    (comp (ref "D36")
      (value "1N4148W-TP")
      (footprint "eagle-import:SOD123")
      (fields (field (name "MF") "Diodes Inc.") (field (name "MP") "1N4148WTP"))
      (libsource (lib "eagle-import") (part "1N4148W-TP"))
    )
    (comp (ref "D37")
      (value "1N4148W-TP")
      (footprint "eagle-import:SOD123")
      (fields (field (name "MF") "Diodes Inc.") (field (name "MP") "1N4148WTP"))
      (libsource (lib "eagle-import") (part "1N4148W-TP"))
    )
    (comp (ref "D38")
      (value "1N4148W-TP")
      (footprint "eagle-import:SOD123")
      (fields (field (name "MF") "Diodes Inc.") (field (name "MP") "1N4148WTP"))
      (libsource (lib "eagle-import") (part "1N4148W-TP"))
    )
    (comp (ref "D39")
      (value "1N4148W-TP")
      (footprint "eagle-import:SOD123")
      (fields (field (name "MF") "Diodes Inc.") (field (name "MP") "1N4148WTP"))
      (libsource (lib "eagle-import") (part "1N4148W-TP"))
    )
    (comp (ref "D40")
      (value "1N4148W-TP")
      (footprint "eagle-import:SOD123")
      (fields (field (name "MF") "Diodes Inc.") (field (name "MP") "1N4148WTP"))
      (libsource (lib "eagle-import") (part "1N4148W-TP"))
    )
    (comp (ref "D41")
      (value "1N4148W-TP")
      (footprint "eagle-import:SOD123")
      (fields (field (name "MF") "Diodes Inc.") (field (name "MP") "1N4148WTP"))
      (libsource (lib "eagle-import") (part "1N4148W-TP"))
    )
    (comp (ref "D42")
      (value "1N4148W-TP")
      (footprint "eagle-import:SOD123")
      (fields (field (name "MF") "Diodes Inc.") (field (name "MP") "1N4148WTP"))
      (libsource (lib "eagle-import") (part "1N4148W-TP"))
    )
    (comp (ref "D43")
      (value "1N4148W-TP")
      (footprint "eagle-import:SOD123")
      (fields (field (name "MF") "Diodes Inc.") (field (name "MP") "1N4148WTP"))
      (libsource (lib "eagle-import") (part "1N4148W-TP"))
    )
    (comp (ref "D44")
      (value "1N4148W-TP")
      (footprint "eagle-import:SOD123")
      (fields (field (name "MF") "Diodes Inc.") (field (name "MP") "1N4148WTP"))
      (libsource (lib "eagle-import") (part "1N4148W-TP"))
    )
    (comp (ref "D45")
      (value "1N4148W-TP")
      (footprint "eagle-import:SOD123")
      (fields (field (name "MF") "Diodes Inc.") (field (name "MP") "1N4148WTP"))
      (libsource (lib "eagle-import") (part "1N4148W-TP"))
    )
    (comp (ref "D46")
      (value "1N4148W-TP")
      (footprint "eagle-import:SOD123")
      (fields (field (name "MF") "Diodes Inc.") (field (name "MP") "1N4148WTP"))
      (libsource (lib "eagle-import") (part "1N4148W-TP"))
    )
    (comp (ref "D47")
      (value "1N4148W-TP")
      (footprint "eagle-import:SOD123")
      (fields (field (name "MF") "Diodes Inc.") (field (name "MP") "1N4148WTP"))
      (libsource (lib "eagle-import") (part "1N4148W-TP"))
    )
    (comp (ref "D48")
      (value "1N4148W-TP")
      (footprint "eagle-import:SOD123")
      (fields (field (name "MF") "Diodes Inc.") (field (name "MP") "1N4148WTP"))
      (libsource (lib "eagle-import") (part "1N4148W-TP"))
    )
    (comp (ref "D60")
      (value "1N4148W-TP")
      (footprint "eagle-import:SOD123")
      (fields (field (name "MF") "Diodes Inc.") (field (name "MP") "1N4148WTP"))
      (libsource (lib "eagle-import") (part "1N4148W-TP"))
    )
    (comp (ref "D61")
      (value "1N4148W-TP")
      (footprint "eagle-import:SOD123")
      (fields (field (name "MF") "Diodes Inc.") (field (name "MP") "1N4148WTP"))
      (libsource (lib "eagle-import") (part "1N4148W-TP"))
    )
    (comp (ref "D62")
      (value "1N4148W-TP")
      (footprint "eagle-import:SOD123")
      (fields (field (name "MF") "Diodes Inc.") (field (name "MP") "1N4148WTP"))
      (libsource (lib "eagle-import") (part "1N4148W-TP"))
    )
    (comp (ref "D63")
      (value "1N4148W-TP")
      (footprint "eagle-import:SOD123")
      (fields (field (name "MF") "Diodes Inc.") (field (name "MP") "1N4148WTP"))
      (libsource (lib "eagle-import") (part "1N4148W-TP"))
    )
    (comp (ref "D64")
      (value "1N4148W-TP")
      (footprint "eagle-import:SOD123")
      (fields (field (name "MF") "Diodes Inc.") (field (name "MP") "1N4148WTP"))
      (libsource (lib "eagle-import") (part "1N4148W-TP"))
    )
    (comp (ref "D65")
      (value "1N4148W-TP")
      (footprint "eagle-import:SOD123")
      (fields (field (name "MF") "Diodes Inc.") (field (name "MP") "1N4148WTP"))
      (libsource (lib "eagle-import") (part "1N4148W-TP"))
    )
    (comp (ref "D66")
      (value "1N4148W-TP")
      (footprint "eagle-import:SOD123")
      (fields (field (name "MF") "Diodes Inc.") (field (name "MP") "1N4148WTP"))
      (libsource (lib "eagle-import") (part "1N4148W-TP"))
    )
    (comp (ref "D67")
      (value "1N4148W-TP")
      (footprint "eagle-import:SOD123")
      (fields (field (name "MF") "Diodes Inc.") (field (name "MP") "1N4148WTP"))
      (libsource (lib "eagle-import") (part "1N4148W-TP"))
    )
    (comp (ref "D68")
      (value "1N4148W-TP")
      (footprint "eagle-import:SOD123")
      (fields (field (name "MF") "Diodes Inc.") (field (name "MP") "1N4148WTP"))
      (libsource (lib "eagle-import") (part "1N4148W-TP"))
    )
    (comp (ref "D69")
      (value "1N4148W-TP")
      (footprint "eagle-import:SOD123")
      (fields (field (name "MF") "Diodes Inc.") (field (name "MP") "1N4148WTP"))
      (libsource (lib "eagle-import") (part "1N4148W-TP"))
    )
    (comp (ref "D70")
      (value "1N4148W-TP")
      (footprint "eagle-import:SOD123")
      (fields (field (name "MF") "Diodes Inc.") (field (name "MP") "1N4148WTP"))
      (libsource (lib "eagle-import") (part "1N4148W-TP"))
    )
    (comp (ref "DOUT_ADC1")
      (value "SMD2")
      (footprint "eagle-import:SMD1,27-2,54")
      (libsource (lib "eagle-import") (part "SMD2"))
    )
    (comp (ref "GND1")
      (value "SMD5")
      (footprint "eagle-import:SMD2,54-5,08")
      (libsource (lib "eagle-import") (part "SMD5"))
    )
    (comp (ref "GND2")
      (value "SMD5")
      (footprint "eagle-import:SMD2,54-5,08")
      (libsource (lib "eagle-import") (part "SMD5"))
    )
    (comp (ref "GND3")
      (value "SMD5")
      (footprint "eagle-import:SMD2,54-5,08")
      (libsource (lib "eagle-import") (part "SMD5"))
    )
    (comp (ref "GND4")
      (value "SMD2")
      (footprint "eagle-import:SMD1,27-2,54")
      (libsource (lib "eagle-import") (part "SMD2"))
    )
    (comp (ref "GND5")
      (value "SMD5")
      (footprint "eagle-import:SMD2,54-5,08")
      (libsource (lib "eagle-import") (part "SMD5"))
    )
    (comp (ref "GND6")
      (value "SMD2")
      (footprint "eagle-import:SMD1,27-2,54")
      (libsource (lib "eagle-import") (part "SMD2"))
    )
    (comp (ref "GNDL1")
      (value "SMD5")
      (footprint "eagle-import:SMD2,54-5,08")
      (libsource (lib "eagle-import") (part "SMD5"))
    )
    (comp (ref "GNDR1")
      (value "SMD5")
      (footprint "eagle-import:SMD2,54-5,08")
      (libsource (lib "eagle-import") (part "SMD5"))
    )
    (comp (ref "IC2")
      (value "PCM1865DBT")
      (footprint "eagle-import:TSSOP-30")
      (fields (field (name "MF") "Texas Instruments"))
      (libsource (lib "eagle-import") (part "PCM1865DBT"))
    )
    (comp (ref "IN_COMP1")
      (value "SMD5")
      (footprint "eagle-import:SMD2,54-5,08")
      (libsource (lib "eagle-import") (part "SMD5"))
    )
    (comp (ref "IN_COMP2")
      (value "SMD5")
      (footprint "eagle-import:SMD2,54-5,08")
      (libsource (lib "eagle-import") (part "SMD5"))
    )
    (comp (ref "IN_COMP3")
      (value "SMD5")
      (footprint "eagle-import:SMD2,54-5,08")
      (libsource (lib "eagle-import") (part "SMD5"))
    )
    (comp (ref "IN_COMP5")
      (value "SMD5")
      (footprint "eagle-import:SMD2,54-5,08")
      (libsource (lib "eagle-import") (part "SMD5"))
    )
    (comp (ref "LRCK_ADC1")
      (value "SMD2")
      (footprint "eagle-import:SMD1,27-2,54")
      (libsource (lib "eagle-import") (part "SMD2"))
    )
    (comp (ref "MUX2")
      (value "SMD2")
      (footprint "eagle-import:SMD1,27-2,54")
      (libsource (lib "eagle-import") (part "SMD2"))
    )
    (comp (ref "MUX3")
      (value "SMD2")
      (footprint "eagle-import:SMD1,27-2,54")
      (libsource (lib "eagle-import") (part "SMD2"))
    )
    (comp (ref "OPAMP1_COMP1")
      (value "LM4562MAX/NOPB")
      (footprint "eagle-import:SOIC127P599X175-8N")
      (fields (field (name "MF") "Texas Instruments"))
      (libsource (lib "eagle-import") (part "LM4562MAX/NOPB"))
    )
    (comp (ref "OPAMP1_COMP2")
      (value "LM4562MAX/NOPB")
      (footprint "eagle-import:SOIC127P599X175-8N")
      (fields (field (name "MF") "Texas Instruments"))
      (libsource (lib "eagle-import") (part "LM4562MAX/NOPB"))
    )
    (comp (ref "OPAMP1_COMP3")
      (value "LM4562MAX/NOPB")
      (footprint "eagle-import:SOIC127P599X175-8N")
      (fields (field (name "MF") "Texas Instruments"))
      (libsource (lib "eagle-import") (part "LM4562MAX/NOPB"))
    )
    (comp (ref "OPAMP1_COMP5")
      (value "LM4562MAX/NOPB")
      (footprint "eagle-import:SOIC127P599X175-8N")
      (fields (field (name "MF") "Texas Instruments"))
      (libsource (lib "eagle-import") (part "LM4562MAX/NOPB"))
    )
    (comp (ref "OPAMP1_MIX1")
      (value "LM4562MAX/NOPB")
      (footprint "eagle-import:SOIC127P599X175-8N")
      (fields (field (name "MF") "Texas Instruments"))
      (libsource (lib "eagle-import") (part "LM4562MAX/NOPB"))
    )
    (comp (ref "OPAMP1_PAN1")
      (value "LM4562MAX/NOPB")
      (footprint "eagle-import:SOIC127P599X175-8N")
      (fields (field (name "MF") "Texas Instruments"))
      (libsource (lib "eagle-import") (part "LM4562MAX/NOPB"))
    )
    (comp (ref "OPAMP1_PAN2")
      (value "LM4562MAX/NOPB")
      (footprint "eagle-import:SOIC127P599X175-8N")
      (fields (field (name "MF") "Texas Instruments"))
      (libsource (lib "eagle-import") (part "LM4562MAX/NOPB"))
    )
    (comp (ref "OPAMP1_PAN3")
      (value "LM4562MAX/NOPB")
      (footprint "eagle-import:SOIC127P599X175-8N")
      (fields (field (name "MF") "Texas Instruments"))
      (libsource (lib "eagle-import") (part "LM4562MAX/NOPB"))
    )
    (comp (ref "OPAMP1_PAN4")
      (value "LM4562MAX/NOPB")
      (footprint "eagle-import:SOIC127P599X175-8N")
      (fields (field (name "MF") "Texas Instruments"))
      (libsource (lib "eagle-import") (part "LM4562MAX/NOPB"))
    )
    (comp (ref "OPAMP2_COMP1")
      (value "LM4562MAX/NOPB")
      (footprint "eagle-import:SOIC127P599X175-8N")
      (fields (field (name "MF") "Texas Instruments"))
      (libsource (lib "eagle-import") (part "LM4562MAX/NOPB"))
    )
    (comp (ref "OPAMP2_COMP2")
      (value "LM4562MAX/NOPB")
      (footprint "eagle-import:SOIC127P599X175-8N")
      (fields (field (name "MF") "Texas Instruments"))
      (libsource (lib "eagle-import") (part "LM4562MAX/NOPB"))
    )
    (comp (ref "OPAMP2_COMP3")
      (value "LM4562MAX/NOPB")
      (footprint "eagle-import:SOIC127P599X175-8N")
      (fields (field (name "MF") "Texas Instruments"))
      (libsource (lib "eagle-import") (part "LM4562MAX/NOPB"))
    )
    (comp (ref "OPAMP2_COMP5")
      (value "LM4562MAX/NOPB")
      (footprint "eagle-import:SOIC127P599X175-8N")
      (fields (field (name "MF") "Texas Instruments"))
      (libsource (lib "eagle-import") (part "LM4562MAX/NOPB"))
    )
    (comp (ref "OPAMP3_COMP1")
      (value "LM4562MAX/NOPB")
      (footprint "eagle-import:SOIC127P599X175-8N")
      (fields (field (name "MF") "Texas Instruments"))
      (libsource (lib "eagle-import") (part "LM4562MAX/NOPB"))
    )
    (comp (ref "OPAMP3_COMP2")
      (value "LM4562MAX/NOPB")
      (footprint "eagle-import:SOIC127P599X175-8N")
      (fields (field (name "MF") "Texas Instruments"))
      (libsource (lib "eagle-import") (part "LM4562MAX/NOPB"))
    )
    (comp (ref "OPAMP3_COMP3")
      (value "LM4562MAX/NOPB")
      (footprint "eagle-import:SOIC127P599X175-8N")
      (fields (field (name "MF") "Texas Instruments"))
      (libsource (lib "eagle-import") (part "LM4562MAX/NOPB"))
    )
    (comp (ref "OPAMP3_COMP5")
      (value "LM4562MAX/NOPB")
      (footprint "eagle-import:SOIC127P599X175-8N")
      (fields (field (name "MF") "Texas Instruments"))
      (libsource (lib "eagle-import") (part "LM4562MAX/NOPB"))
    )
    (comp (ref "OPAMP4_COMP1")
      (value "LM4562MAX/NOPB")
      (footprint "eagle-import:SOIC127P599X175-8N")
      (fields (field (name "MF") "Texas Instruments"))
      (libsource (lib "eagle-import") (part "LM4562MAX/NOPB"))
    )
    (comp (ref "OPAMP4_COMP2")
      (value "LM4562MAX/NOPB")
      (footprint "eagle-import:SOIC127P599X175-8N")
      (fields (field (name "MF") "Texas Instruments"))
      (libsource (lib "eagle-import") (part "LM4562MAX/NOPB"))
    )
    (comp (ref "OPAMP4_COMP3")
      (value "LM4562MAX/NOPB")
      (footprint "eagle-import:SOIC127P599X175-8N")
      (fields (field (name "MF") "Texas Instruments"))
      (libsource (lib "eagle-import") (part "LM4562MAX/NOPB"))
    )
    (comp (ref "OPAMP4_COMP5")
      (value "LM4562MAX/NOPB")
      (footprint "eagle-import:SOIC127P599X175-8N")
      (fields (field (name "MF") "Texas Instruments"))
      (libsource (lib "eagle-import") (part "LM4562MAX/NOPB"))
    )
    (comp (ref "OUTL_MIX1")
      (value "SMD5")
      (footprint "eagle-import:SMD2,54-5,08")
      (libsource (lib "eagle-import") (part "SMD5"))
    )
    (comp (ref "OUTR_MIX1")
      (value "SMD5")
      (footprint "eagle-import:SMD2,54-5,08")
      (libsource (lib "eagle-import") (part "SMD5"))
    )
    (comp (ref "PAD1")
      (value "SMD2")
      (footprint "eagle-import:SMD1,27-2,54")
      (libsource (lib "eagle-import") (part "SMD2"))
    )
    (comp (ref "PAD2")
      (value "SMD2")
      (footprint "eagle-import:SMD1,27-2,54")
      (libsource (lib "eagle-import") (part "SMD2"))
    )
    (comp (ref "PAD3")
      (value "SMD2")
      (footprint "eagle-import:SMD1,27-2,54")
      (libsource (lib "eagle-import") (part "SMD2"))
    )
    (comp (ref "PAD4")
      (value "SMD2")
      (footprint "eagle-import:SMD1,27-2,54")
      (libsource (lib "eagle-import") (part "SMD2"))
    )
    (comp (ref "PAD5")
      (value "SMD2")
      (footprint "eagle-import:SMD1,27-2,54")
      (libsource (lib "eagle-import") (part "SMD2"))
    )
    (comp (ref "PAD6")
      (value "SMD2")
      (footprint "eagle-import:SMD1,27-2,54")
      (libsource (lib "eagle-import") (part "SMD2"))
    )
    (comp (ref "PAD7")
      (value "SMD2")
      (footprint "eagle-import:SMD1,27-2,54")
      (libsource (lib "eagle-import") (part "SMD2"))
    )
    (comp (ref "PAD8")
      (value "SMD2")
      (footprint "eagle-import:SMD1,27-2,54")
      (libsource (lib "eagle-import") (part "SMD2"))
    )
    (comp (ref "PAD9")
      (value "SMD2")
      (footprint "eagle-import:SMD1,27-2,54")
      (libsource (lib "eagle-import") (part "SMD2"))
    )
    (comp (ref "PAD10")
      (value "SMD2")
      (footprint "eagle-import:SMD1,27-2,54")
      (libsource (lib "eagle-import") (part "SMD2"))
    )
    (comp (ref "PAD11")
      (value "SMD2")
      (footprint "eagle-import:SMD1,27-2,54")
      (libsource (lib "eagle-import") (part "SMD2"))
    )
    (comp (ref "PAD12")
      (value "SMD2")
      (footprint "eagle-import:SMD1,27-2,54")
      (libsource (lib "eagle-import") (part "SMD2"))
    )
    (comp (ref "PAD13")
      (value "SMD2")
      (footprint "eagle-import:SMD1,27-2,54")
      (libsource (lib "eagle-import") (part "SMD2"))
    )
    (comp (ref "PAD14")
      (value "SMD2")
      (footprint "eagle-import:SMD1,27-2,54")
      (libsource (lib "eagle-import") (part "SMD2"))
    )
    (comp (ref "PAD15")
      (value "SMD2")
      (footprint "eagle-import:SMD1,27-2,54")
      (libsource (lib "eagle-import") (part "SMD2"))
    )
    (comp (ref "PAD16")
      (value "SMD2")
      (footprint "eagle-import:SMD1,27-2,54")
      (libsource (lib "eagle-import") (part "SMD2"))
    )
    (comp (ref "R5")
      (value "10k")
      (footprint "eagle-import:R0402")
      (libsource (lib "eagle-import") (part "R-US_R0402"))
    )
    (comp (ref "R6")
      (value "1M")
      (footprint "eagle-import:R0402")
      (libsource (lib "eagle-import") (part "R-US_R0402"))
    )
    (comp (ref "R7")
      (value "5k")
      (footprint "eagle-import:R0402")
      (libsource (lib "eagle-import") (part "R-US_R0402"))
    )
    (comp (ref "R8")
      (value "10k")
      (footprint "eagle-import:R0402")
      (libsource (lib "eagle-import") (part "R-US_R0402"))
    )
    (comp (ref "R9")
      (value "10k")
      (footprint "eagle-import:R0402")
      (libsource (lib "eagle-import") (part "R-US_R0402"))
    )
    (comp (ref "R10")
      (value "5k")
      (footprint "eagle-import:R0402")
      (libsource (lib "eagle-import") (part "R-US_R0402"))
    )
    (comp (ref "R11")
      (value "5k")
      (footprint "eagle-import:R0402")
      (libsource (lib "eagle-import") (part "R-US_R0402"))
    )
    (comp (ref "R12")
      (value "10k")
      (footprint "eagle-import:R0402")
      (libsource (lib "eagle-import") (part "R-US_R0402"))
    )
    (comp (ref "R13")
      (value "5k")
      (footprint "eagle-import:R0402")
      (libsource (lib "eagle-import") (part "R-US_R0402"))
    )
    (comp (ref "R14")
      (value "10k")
      (footprint "eagle-import:R0402")
      (libsource (lib "eagle-import") (part "R-US_R0402"))
    )
    (comp (ref "R15")
      (value "1M")
      (footprint "eagle-import:R0402")
      (libsource (lib "eagle-import") (part "R-US_R0402"))
    )
    (comp (ref "R16")
      (value "5k")
      (footprint "eagle-import:R0402")
      (libsource (lib "eagle-import") (part "R-US_R0402"))
    )
    (comp (ref "R17")
      (value "5k")
      (footprint "eagle-import:R0402")
      (libsource (lib "eagle-import") (part "R-US_R0402"))
    )
    (comp (ref "R18")
      (value "5k")
      (footprint "eagle-import:R0402")
      (libsource (lib "eagle-import") (part "R-US_R0402"))
    )
    (comp (ref "R19")
      (value "10k")
      (footprint "eagle-import:R0402")
      (libsource (lib "eagle-import") (part "R-US_R0402"))
    )
    (comp (ref "R20")
      (value "5k")
      (footprint "eagle-import:R0402")
      (libsource (lib "eagle-import") (part "R-US_R0402"))
    )
    (comp (ref "R21")
      (value "10k")
      (footprint "eagle-import:R0402")
      (libsource (lib "eagle-import") (part "R-US_R0402"))
    )
    (comp (ref "R22")
      (value "17k")
      (footprint "eagle-import:R0402")
      (libsource (lib "eagle-import") (part "R-US_R0402"))
    )
    (comp (ref "R31")
      (value "5k")
      (footprint "eagle-import:R0402")
      (libsource (lib "eagle-import") (part "R-US_R0402"))
    )
    (comp (ref "R32")
      (value "10k")
      (footprint "eagle-import:R0402")
      (libsource (lib "eagle-import") (part "R-US_R0402"))
    )
    (comp (ref "R33")
      (value "5k")
      (footprint "eagle-import:R0402")
      (libsource (lib "eagle-import") (part "R-US_R0402"))
    )
    (comp (ref "R34")
      (value "10k")
      (footprint "eagle-import:R0402")
      (libsource (lib "eagle-import") (part "R-US_R0402"))
    )
    (comp (ref "R35")
      (value "5k")
      (footprint "eagle-import:R0402")
      (libsource (lib "eagle-import") (part "R-US_R0402"))
    )
    (comp (ref "R36")
      (value "5k")
      (footprint "eagle-import:R0402")
      (libsource (lib "eagle-import") (part "R-US_R0402"))
    )
    (comp (ref "R37")
      (value "5k")
      (footprint "eagle-import:R0402")
      (libsource (lib "eagle-import") (part "R-US_R0402"))
    )
    (comp (ref "R38")
      (value "5k")
      (footprint "eagle-import:R0402")
      (libsource (lib "eagle-import") (part "R-US_R0402"))
    )
    (comp (ref "R39")
      (value "5k")
      (footprint "eagle-import:R0402")
      (libsource (lib "eagle-import") (part "R-US_R0402"))
    )
    (comp (ref "R40")
      (value "5k")
      (footprint "eagle-import:R0402")
      (libsource (lib "eagle-import") (part "R-US_R0402"))
    )
    (comp (ref "R41")
      (value "10k")
      (footprint "eagle-import:R0402")
      (libsource (lib "eagle-import") (part "R-US_R0402"))
    )
    (comp (ref "R42")
      (value "10k")
      (footprint "eagle-import:R0402")
      (libsource (lib "eagle-import") (part "R-US_R0402"))
    )
    (comp (ref "R43")
      (value "5k")
      (footprint "eagle-import:R0402")
      (libsource (lib "eagle-import") (part "R-US_R0402"))
    )
    (comp (ref "R44")
      (value "50k")
      (footprint "eagle-import:R0402")
      (libsource (lib "eagle-import") (part "R-US_R0402"))
    )
    (comp (ref "R45")
      (value "1k")
      (footprint "eagle-import:R0402")
      (libsource (lib "eagle-import") (part "R-US_R0402"))
    )
    (comp (ref "R46")
      (value "5k")
      (footprint "eagle-import:R0402")
      (libsource (lib "eagle-import") (part "R-US_R0402"))
    )
    (comp (ref "R47")
      (value "10k")
      (footprint "eagle-import:R0402")
      (libsource (lib "eagle-import") (part "R-US_R0402"))
    )
    (comp (ref "R48")
      (value "5k")
      (footprint "eagle-import:R0402")
      (libsource (lib "eagle-import") (part "R-US_R0402"))
    )
    (comp (ref "R49")
      (value "10k")
      (footprint "eagle-import:R0402")
      (libsource (lib "eagle-import") (part "R-US_R0402"))
    )
    (comp (ref "R50")
      (value "5k")
      (footprint "eagle-import:R0402")
      (libsource (lib "eagle-import") (part "R-US_R0402"))
    )
    (comp (ref "R51")
      (value "5k")
      (footprint "eagle-import:R0402")
      (libsource (lib "eagle-import") (part "R-US_R0402"))
    )
    (comp (ref "R52")
      (value "5k")
      (footprint "eagle-import:R0402")
      (libsource (lib "eagle-import") (part "R-US_R0402"))
    )
    (comp (ref "R53")
      (value "5k")
      (footprint "eagle-import:R0402")
      (libsource (lib "eagle-import") (part "R-US_R0402"))
    )
    (comp (ref "R54")
      (value "5k")
      (footprint "eagle-import:R0402")
      (libsource (lib "eagle-import") (part "R-US_R0402"))
    )
    (comp (ref "R55")
      (value "5k")
      (footprint "eagle-import:R0402")
      (libsource (lib "eagle-import") (part "R-US_R0402"))
    )
    (comp (ref "R56")
      (value "10k")
      (footprint "eagle-import:R0402")
      (libsource (lib "eagle-import") (part "R-US_R0402"))
    )
    (comp (ref "R57")
      (value "10k")
      (footprint "eagle-import:R0402")
      (libsource (lib "eagle-import") (part "R-US_R0402"))
    )
    (comp (ref "R58")
      (value "5k")
      (footprint "eagle-import:R0402")
      (libsource (lib "eagle-import") (part "R-US_R0402"))
    )
    (comp (ref "R59")
      (value "50k")
      (footprint "eagle-import:R0402")
      (libsource (lib "eagle-import") (part "R-US_R0402"))
    )
    (comp (ref "R60")
      (value "1k")
      (footprint "eagle-import:R0402")
      (libsource (lib "eagle-import") (part "R-US_R0402"))
    )
    (comp (ref "R63")
      (value "100k")
      (footprint "eagle-import:R0402")
      (libsource (lib "eagle-import") (part "R-US_R0402"))
    )
    (comp (ref "R64")
      (value "470k")
      (footprint "eagle-import:R0402")
      (libsource (lib "eagle-import") (part "R-US_R0402"))
    )
    (comp (ref "R65")
      (value "1k")
      (footprint "eagle-import:R0402")
      (libsource (lib "eagle-import") (part "R-US_R0402"))
    )
    (comp (ref "R66")
      (value "470k")
      (footprint "eagle-import:R0402")
      (libsource (lib "eagle-import") (part "R-US_R0402"))
    )
    (comp (ref "R67")
      (value "100k")
      (footprint "eagle-import:R0402")
      (libsource (lib "eagle-import") (part "R-US_R0402"))
    )
    (comp (ref "R68")
      (value "1M")
      (footprint "eagle-import:R0402")
      (libsource (lib "eagle-import") (part "R-US_R0402"))
    )
    (comp (ref "R69")
      (value "5k")
      (footprint "eagle-import:R0402")
      (libsource (lib "eagle-import") (part "R-US_R0402"))
    )
    (comp (ref "R70")
      (value "5k")
      (footprint "eagle-import:R0402")
      (libsource (lib "eagle-import") (part "R-US_R0402"))
    )
    (comp (ref "R71")
      (value "5k")
      (footprint "eagle-import:R0402")
      (libsource (lib "eagle-import") (part "R-US_R0402"))
    )
    (comp (ref "R72")
      (value "10k")
      (footprint "eagle-import:R0402")
      (libsource (lib "eagle-import") (part "R-US_R0402"))
    )
    (comp (ref "R73")
      (value "5k")
      (footprint "eagle-import:R0402")
      (libsource (lib "eagle-import") (part "R-US_R0402"))
    )
    (comp (ref "R74")
      (value "10k")
      (footprint "eagle-import:R0402")
      (libsource (lib "eagle-import") (part "R-US_R0402"))
    )
    (comp (ref "R75")
      (value "100k")
      (footprint "eagle-import:R0402")
      (libsource (lib "eagle-import") (part "R-US_R0402"))
    )
    (comp (ref "R76")
      (value "10k")
      (footprint "eagle-import:R0402")
      (libsource (lib "eagle-import") (part "R-US_R0402"))
    )
    (comp (ref "R77")
      (value "100k")
      (footprint "eagle-import:R0402")
      (libsource (lib "eagle-import") (part "R-US_R0402"))
    )
    (comp (ref "R78")
      (value "100k")
      (footprint "eagle-import:R0402")
      (libsource (lib "eagle-import") (part "R-US_R0402"))
    )
    (comp (ref "R79")
      (value "100k")
      (footprint "eagle-import:R0402")
      (libsource (lib "eagle-import") (part "R-US_R0402"))
    )
    (comp (ref "R80")
      (value "10k")
      (footprint "eagle-import:R0402")
      (libsource (lib "eagle-import") (part "R-US_R0402"))
    )
    (comp (ref "R81")
      (value "20k")
      (footprint "eagle-import:R0402")
      (libsource (lib "eagle-import") (part "R-US_R0402"))
    )
    (comp (ref "R82")
      (value "1M")
      (footprint "eagle-import:R0402")
      (libsource (lib "eagle-import") (part "R-US_R0402"))
    )
    (comp (ref "R83")
      (value "5k")
      (footprint "eagle-import:R0402")
      (libsource (lib "eagle-import") (part "R-US_R0402"))
    )
    (comp (ref "R84")
      (value "5k")
      (footprint "eagle-import:R0402")
      (libsource (lib "eagle-import") (part "R-US_R0402"))
    )
    (comp (ref "R85")
      (value "5k")
      (footprint "eagle-import:R0402")
      (libsource (lib "eagle-import") (part "R-US_R0402"))
    )
    (comp (ref "R86")
      (value "10k")
      (footprint "eagle-import:R0402")
      (libsource (lib "eagle-import") (part "R-US_R0402"))
    )
    (comp (ref "R87")
      (value "5k")
      (footprint "eagle-import:R0402")
      (libsource (lib "eagle-import") (part "R-US_R0402"))
    )
    (comp (ref "R88")
      (value "10k")
      (footprint "eagle-import:R0402")
      (libsource (lib "eagle-import") (part "R-US_R0402"))
    )
    (comp (ref "R89")
      (value "100k")
      (footprint "eagle-import:R0402")
      (libsource (lib "eagle-import") (part "R-US_R0402"))
    )
    (comp (ref "R90")
      (value "100k")
      (footprint "eagle-import:R0402")
      (libsource (lib "eagle-import") (part "R-US_R0402"))
    )
    (comp (ref "R91")
      (value "100k")
      (footprint "eagle-import:R0402")
      (libsource (lib "eagle-import") (part "R-US_R0402"))
    )
    (comp (ref "R92")
      (value "10k")
      (footprint "eagle-import:R0402")
      (libsource (lib "eagle-import") (part "R-US_R0402"))
    )
    (comp (ref "R93")
      (value "100k")
      (footprint "eagle-import:R0402")
      (libsource (lib "eagle-import") (part "R-US_R0402"))
    )
    (comp (ref "R94")
      (value "100k")
      (footprint "eagle-import:R0402")
      (libsource (lib "eagle-import") (part "R-US_R0402"))
    )
    (comp (ref "R95")
      (value "100k")
      (footprint "eagle-import:R0402")
      (libsource (lib "eagle-import") (part "R-US_R0402"))
    )
    (comp (ref "R96")
      (value "470k")
      (footprint "eagle-import:R0402")
      (libsource (lib "eagle-import") (part "R-US_R0402"))
    )
    (comp (ref "R97")
      (value "1k")
      (footprint "eagle-import:R0402")
      (libsource (lib "eagle-import") (part "R-US_R0402"))
    )
    (comp (ref "R98")
      (value "470k")
      (footprint "eagle-import:R0402")
      (libsource (lib "eagle-import") (part "R-US_R0402"))
    )
    (comp (ref "R99")
      (value "100k")
      (footprint "eagle-import:R0402")
      (libsource (lib "eagle-import") (part "R-US_R0402"))
    )
    (comp (ref "R100")
      (value "100k")
      (footprint "eagle-import:R0402")
      (libsource (lib "eagle-import") (part "R-US_R0402"))
    )
    (comp (ref "R101")
      (value "10k")
      (footprint "eagle-import:R0402")
      (libsource (lib "eagle-import") (part "R-US_R0402"))
    )
    (comp (ref "R102")
      (value "100k")
      (footprint "eagle-import:R0402")
      (libsource (lib "eagle-import") (part "R-US_R0402"))
    )
    (comp (ref "R103")
      (value "100k")
      (footprint "eagle-import:R0402")
      (libsource (lib "eagle-import") (part "R-US_R0402"))
    )
    (comp (ref "R104")
      (value "100k")
      (footprint "eagle-import:R0402")
      (libsource (lib "eagle-import") (part "R-US_R0402"))
    )
    (comp (ref "R105")
      (value "10k")
      (footprint "eagle-import:R0402")
      (libsource (lib "eagle-import") (part "R-US_R0402"))
    )
    (comp (ref "R106")
      (value "20k")
      (footprint "eagle-import:R0402")
      (libsource (lib "eagle-import") (part "R-US_R0402"))
    )
    (comp (ref "R107")
      (value "100k")
      (footprint "eagle-import:R0402")
      (libsource (lib "eagle-import") (part "R-US_R0402"))
    )
    (comp (ref "R108")
      (value "100k")
      (footprint "eagle-import:R0402")
      (libsource (lib "eagle-import") (part "R-US_R0402"))
    )
    (comp (ref "R109")
      (value "100k")
      (footprint "eagle-import:R0402")
      (libsource (lib "eagle-import") (part "R-US_R0402"))
    )
    (comp (ref "R110")
      (value "10k")
      (footprint "eagle-import:R0402")
      (libsource (lib "eagle-import") (part "R-US_R0402"))
    )
    (comp (ref "R111")
      (value "100k")
      (footprint "eagle-import:R0402")
      (libsource (lib "eagle-import") (part "R-US_R0402"))
    )
    (comp (ref "R112")
      (value "100k")
      (footprint "eagle-import:R0402")
      (libsource (lib "eagle-import") (part "R-US_R0402"))
    )
    (comp (ref "R113")
      (value "100k")
      (footprint "eagle-import:R0402")
      (libsource (lib "eagle-import") (part "R-US_R0402"))
    )
    (comp (ref "R114")
      (value "470k")
      (footprint "eagle-import:R0402")
      (libsource (lib "eagle-import") (part "R-US_R0402"))
    )
    (comp (ref "R115")
      (value "1k")
      (footprint "eagle-import:R0402")
      (libsource (lib "eagle-import") (part "R-US_R0402"))
    )
    (comp (ref "R116")
      (value "470k")
      (footprint "eagle-import:R0402")
      (libsource (lib "eagle-import") (part "R-US_R0402"))
    )
    (comp (ref "R117")
      (value "100k")
      (footprint "eagle-import:R0402")
      (libsource (lib "eagle-import") (part "R-US_R0402"))
    )
    (comp (ref "R118")
      (value "100k")
      (footprint "eagle-import:R0402")
      (libsource (lib "eagle-import") (part "R-US_R0402"))
    )
    (comp (ref "R119")
      (value "10k")
      (footprint "eagle-import:R0402")
      (libsource (lib "eagle-import") (part "R-US_R0402"))
    )
    (comp (ref "R120")
      (value "100k")
      (footprint "eagle-import:R0402")
      (libsource (lib "eagle-import") (part "R-US_R0402"))
    )
    (comp (ref "R121")
      (value "100k")
      (footprint "eagle-import:R0402")
      (libsource (lib "eagle-import") (part "R-US_R0402"))
    )
    (comp (ref "R122")
      (value "100k")
      (footprint "eagle-import:R0402")
      (libsource (lib "eagle-import") (part "R-US_R0402"))
    )
    (comp (ref "R123")
      (value "10k")
      (footprint "eagle-import:R0402")
      (libsource (lib "eagle-import") (part "R-US_R0402"))
    )
    (comp (ref "R124")
      (value "20k")
      (footprint "eagle-import:R0402")
      (libsource (lib "eagle-import") (part "R-US_R0402"))
    )
    (comp (ref "R125")
      (value "100k")
      (footprint "eagle-import:R0402")
      (libsource (lib "eagle-import") (part "R-US_R0402"))
    )
    (comp (ref "R126")
      (value "100k")
      (footprint "eagle-import:R0402")
      (libsource (lib "eagle-import") (part "R-US_R0402"))
    )
    (comp (ref "R127")
      (value "100k")
      (footprint "eagle-import:R0402")
      (libsource (lib "eagle-import") (part "R-US_R0402"))
    )
    (comp (ref "R128")
      (value "10k")
      (footprint "eagle-import:R0402")
      (libsource (lib "eagle-import") (part "R-US_R0402"))
    )
    (comp (ref "R129")
      (value "100k")
      (footprint "eagle-import:R0402")
      (libsource (lib "eagle-import") (part "R-US_R0402"))
    )
    (comp (ref "R130")
      (value "100k")
      (footprint "eagle-import:R0402")
      (libsource (lib "eagle-import") (part "R-US_R0402"))
    )
    (comp (ref "R149")
      (value "100k")
      (footprint "eagle-import:R0402")
      (libsource (lib "eagle-import") (part "R-US_R0402"))
    )
    (comp (ref "R150")
      (value "470k")
      (footprint "eagle-import:R0402")
      (libsource (lib "eagle-import") (part "R-US_R0402"))
    )
    (comp (ref "R151")
      (value "1k")
      (footprint "eagle-import:R0402")
      (libsource (lib "eagle-import") (part "R-US_R0402"))
    )
    (comp (ref "R152")
      (value "470k")
      (footprint "eagle-import:R0402")
      (libsource (lib "eagle-import") (part "R-US_R0402"))
    )
    (comp (ref "R153")
      (value "100k")
      (footprint "eagle-import:R0402")
      (libsource (lib "eagle-import") (part "R-US_R0402"))
    )
    (comp (ref "R154")
      (value "100k")
      (footprint "eagle-import:R0402")
      (libsource (lib "eagle-import") (part "R-US_R0402"))
    )
    (comp (ref "R155")
      (value "10k")
      (footprint "eagle-import:R0402")
      (libsource (lib "eagle-import") (part "R-US_R0402"))
    )
    (comp (ref "R156")
      (value "100k")
      (footprint "eagle-import:R0402")
      (libsource (lib "eagle-import") (part "R-US_R0402"))
    )
    (comp (ref "R157")
      (value "100k")
      (footprint "eagle-import:R0402")
      (libsource (lib "eagle-import") (part "R-US_R0402"))
    )
    (comp (ref "R158")
      (value "100k")
      (footprint "eagle-import:R0402")
      (libsource (lib "eagle-import") (part "R-US_R0402"))
    )
    (comp (ref "R159")
      (value "10k")
      (footprint "eagle-import:R0402")
      (libsource (lib "eagle-import") (part "R-US_R0402"))
    )
    (comp (ref "R160")
      (value "20k")
      (footprint "eagle-import:R0402")
      (libsource (lib "eagle-import") (part "R-US_R0402"))
    )
    (comp (ref "R161")
      (value "100k")
      (footprint "eagle-import:R0402")
      (libsource (lib "eagle-import") (part "R-US_R0402"))
    )
    (comp (ref "R162")
      (value "100k")
      (footprint "eagle-import:R0402")
      (libsource (lib "eagle-import") (part "R-US_R0402"))
    )
    (comp (ref "R163")
      (value "100k")
      (footprint "eagle-import:R0402")
      (libsource (lib "eagle-import") (part "R-US_R0402"))
    )
    (comp (ref "R164")
      (value "10k")
      (footprint "eagle-import:R0402")
      (libsource (lib "eagle-import") (part "R-US_R0402"))
    )
    (comp (ref "R165")
      (value "100k")
      (footprint "eagle-import:R0402")
      (libsource (lib "eagle-import") (part "R-US_R0402"))
    )
    (comp (ref "R166")
      (value "100k")
      (footprint "eagle-import:R0402")
      (libsource (lib "eagle-import") (part "R-US_R0402"))
    )
    (comp (ref "SCK1")
      (value "SMD2")
      (footprint "eagle-import:SMD1,27-2,54")
      (libsource (lib "eagle-import") (part "SMD2"))
    )
    (comp (ref "SCL1")
      (value "SMD2")
      (footprint "eagle-import:SMD1,27-2,54")
      (libsource (lib "eagle-import") (part "SMD2"))
    )
    (comp (ref "SCL2")
      (value "SMD2")
      (footprint "eagle-import:SMD1,27-2,54")
      (libsource (lib "eagle-import") (part "SMD2"))
    )
    (comp (ref "SDA1")
      (value "SMD2")
      (footprint "eagle-import:SMD1,27-2,54")
      (libsource (lib "eagle-import") (part "SMD2"))
    )
    (comp (ref "SDA2")
      (value "SMD2")
      (footprint "eagle-import:SMD1,27-2,54")
      (libsource (lib "eagle-import") (part "SMD2"))
    )
    (comp (ref "SDI/O1")
      (value "SMD2")
      (footprint "eagle-import:SMD1,27-2,54")
      (libsource (lib "eagle-import") (part "SMD2"))
    )
    (comp (ref "U$1")
      (value "LC75281E")
      (footprint "eagle-import:QFP80P1720X1720X270-64N")
      (libsource (lib "eagle-import") (part "LC75281E"))
    )
    (comp (ref "U$3")
      (value "LC75281E")
      (footprint "eagle-import:QFP80P1720X1720X270-64N")
      (libsource (lib "eagle-import") (part "LC75281E"))
    )
    (comp (ref "U2")
      (value "LM4562MAX/NOPB")
      (footprint "eagle-import:SOIC127P599X175-8N")
      (fields (field (name "MF") "Texas Instruments"))
      (libsource (lib "eagle-import") (part "LM4562MAX/NOPB"))
    )
    (comp (ref "U3")
      (value "TMUX1204DGSR")
      (footprint "eagle-import:SOP50P490X110-10N")
      (fields (field (name "MF") "Texas Instruments"))
      (libsource (lib "eagle-import") (part "TMUX1204DGSR"))
    )
    (comp (ref "U4")
      (value "TMUX1204DGSR")
      (footprint "eagle-import:SOP50P490X110-10N")
      (fields (field (name "MF") "Texas Instruments"))
      (libsource (lib "eagle-import") (part "TMUX1204DGSR"))
    )
    (comp (ref "U5")
      (value "TMUX1204DGSR")
      (footprint "eagle-import:SOP50P490X110-10N")
      (fields (field (name "MF") "Texas Instruments"))
      (libsource (lib "eagle-import") (part "TMUX1204DGSR"))
    )
    (comp (ref "U11")
      (value "TMUX1204DGSR")
      (footprint "eagle-import:SOP50P490X110-10N")
      (fields (field (name "MF") "Texas Instruments"))
      (libsource (lib "eagle-import") (part "TMUX1204DGSR"))
    )
    (comp (ref "Y2")
      (value "ECS-245.7-20-3X-EN-TR")
      (footprint "eagle-import:XTAL_ECS-245.7-20-3X-EN-TR")
      (fields (field (name "MF") "ECS Inc."))
      (libsource (lib "eagle-import") (part "ECS-245.7-20-3X-EN-TR"))
    )
  )
  (nets
    (net (code "1") (name "+3V3_D") (class "Default")
      (node (ref "3V3_D1") (pin "1") (pinfunction "P_1") (pintype "passive"))
      (node (ref "U11") (pin "5") (pinfunction "EN_5") (pintype "input"))
      (node (ref "U11") (pin "6") (pinfunction "VDD_6") (pintype "power_in"))
      (node (ref "U3") (pin "5") (pinfunction "EN_5") (pintype "input"))
      (node (ref "U3") (pin "6") (pinfunction "VDD_6") (pintype "power_in"))
      (node (ref "U4") (pin "5") (pinfunction "EN_5") (pintype "input"))
      (node (ref "U4") (pin "6") (pinfunction "VDD_6") (pintype "power_in"))
      (node (ref "U5") (pin "5") (pinfunction "EN_5") (pintype "input"))
      (node (ref "U5") (pin "6") (pinfunction "VDD_6") (pintype "power_in"))
    )
    (net (code "2") (name "/N$211") (class "Default")
      (node (ref "C42") (pin "1") (pinfunction "1_1") (pintype "passive"))
      (node (ref "D17") (pin "2") (pinfunction "2_2") (pintype "passive"))
      (node (ref "D18") (pin "1") (pinfunction "1_1") (pintype "passive"))
      (node (ref "D25") (pin "2") (pinfunction "2_2") (pintype "passive"))
      (node (ref "R65") (pin "1") (pinfunction "1_1") (pintype "passive"))
      (node (ref "R89") (pin "2") (pinfunction "2_2") (pintype "passive"))
    )
    (net (code "3") (name "/N$212") (class "Default")
      (node (ref "C48") (pin "1") (pinfunction "1_1") (pintype "passive"))
      (node (ref "D39") (pin "2") (pinfunction "2_2") (pintype "passive"))
      (node (ref "D40") (pin "1") (pinfunction "1_1") (pintype "passive"))
      (node (ref "D47") (pin "2") (pinfunction "2_2") (pintype "passive"))
      (node (ref "R115") (pin "1") (pinfunction "1_1") (pintype "passive"))
      (node (ref "R125") (pin "2") (pinfunction "2_2") (pintype "passive"))
    )
    (net (code "4") (name "/N$213") (class "Default")
      (node (ref "C45") (pin "1") (pinfunction "1_1") (pintype "passive"))
      (node (ref "D28") (pin "2") (pinfunction "2_2") (pintype "passive"))
      (node (ref "D29") (pin "1") (pinfunction "1_1") (pintype "passive"))
      (node (ref "D36") (pin "2") (pinfunction "2_2") (pintype "passive"))
      (node (ref "R107") (pin "2") (pinfunction "2_2") (pintype "passive"))
      (node (ref "R97") (pin "1") (pinfunction "1_1") (pintype "passive"))
    )
    (net (code "5") (name "/N$214") (class "Default")
      (node (ref "C54") (pin "1") (pinfunction "1_1") (pintype "passive"))
      (node (ref "D61") (pin "2") (pinfunction "2_2") (pintype "passive"))
      (node (ref "D62") (pin "1") (pinfunction "1_1") (pintype "passive"))
      (node (ref "D69") (pin "2") (pinfunction "2_2") (pintype "passive"))
      (node (ref "R151") (pin "1") (pinfunction "1_1") (pintype "passive"))
      (node (ref "R161") (pin "2") (pinfunction "2_2") (pintype "passive"))
    )
    (net (code "6") (name "3V3A") (class "Default")
      (node (ref "C70") (pin "1") (pinfunction "1_1") (pintype "passive"))
      (node (ref "C71") (pin "1") (pinfunction "1_1") (pintype "passive"))
      (node (ref "IC2") (pin "8") (pinfunction "AVDD_8") (pintype "bidirectional"))
      (node (ref "U2") (pin "1") (pinfunction "OUT_A_1") (pintype "output"))
      (node (ref "U2") (pin "2") (pinfunction "NEG_A_2") (pintype "input"))
    )
    (net (code "7") (name "3V3D") (class "Default")
      (node (ref "C68") (pin "1") (pinfunction "1_1") (pintype "passive"))
      (node (ref "C69") (pin "1") (pinfunction "1_1") (pintype "passive"))
      (node (ref "IC2") (pin "13") (pinfunction "DVDD_13") (pintype "bidirectional"))
      (node (ref "IC2") (pin "14") (pinfunction "IOVDD_14") (pintype "bidirectional"))
    )
    (net (code "8") (name "BCK_ADC") (class "Default")
      (node (ref "BCK_ADC1") (pin "1") (pinfunction "P_1") (pintype "passive"))
      (node (ref "IC2") (pin "17") (pinfunction "BCK_17") (pintype "bidirectional"))
    )
    (net (code "9") (name "CLK_ADC") (class "Default")
      (node (ref "CLK_ADC1") (pin "1") (pinfunction "P_1") (pintype "passive"))
      (node (ref "IC2") (pin "15") (pinfunction "SCKI_15") (pintype "bidirectional"))
    )
    (net (code "10") (name "CS") (class "Default")
      (node (ref "CS6") (pin "1") (pinfunction "P_1") (pintype "passive"))
      (node (ref "U11") (pin "8") (pinfunction "D_8") (pintype "bidirectional"))
    )
    (net (code "11") (name "CS0") (class "Default")
      (node (ref "CS3") (pin "1") (pinfunction "P_1") (pintype "passive"))
      (node (ref "U3") (pin "8") (pinfunction "D_8") (pintype "bidirectional"))
    )
    (net (code "12") (name "CS0_COMP1") (class "Default")
      (node (ref "100POT1_COMP1") (pin "1") (pinfunction "~{CS}_1") (pintype "input"))
      (node (ref "U3") (pin "2") (pinfunction "S1_2") (pintype "bidirectional"))
    )
    (net (code "13") (name "CS0_COMP2") (class "Default")
      (node (ref "100POT1_COMP3") (pin "1") (pinfunction "~{CS}_1") (pintype "input"))
      (node (ref "U3") (pin "9") (pinfunction "S2_9") (pintype "bidirectional"))
    )
    (net (code "14") (name "CS0_COMP3") (class "Default")
      (node (ref "100POT1_COMP2") (pin "1") (pinfunction "~{CS}_1") (pintype "input"))
      (node (ref "U3") (pin "4") (pinfunction "S3_4") (pintype "bidirectional"))
    )
    (net (code "15") (name "CS0_COMP4") (class "Default")
      (node (ref "100POT1_COMP5") (pin "1") (pinfunction "~{CS}_1") (pintype "input"))
      (node (ref "U3") (pin "7") (pinfunction "S4_7") (pintype "bidirectional"))
    )
    (net (code "16") (name "CS1") (class "Default")
      (node (ref "CS4") (pin "1") (pinfunction "P_1") (pintype "passive"))
      (node (ref "U5") (pin "8") (pinfunction "D_8") (pintype "bidirectional"))
    )
    (net (code "17") (name "CS1_COMP1") (class "Default")
      (node (ref "10POT1_COMP1") (pin "1") (pinfunction "~{CS}_1") (pintype "input"))
      (node (ref "U5") (pin "2") (pinfunction "S1_2") (pintype "bidirectional"))
    )
    (net (code "18") (name "CS1_COMP2") (class "Default")
      (node (ref "10POT1_COMP3") (pin "1") (pinfunction "~{CS}_1") (pintype "input"))
      (node (ref "U5") (pin "9") (pinfunction "S2_9") (pintype "bidirectional"))
    )
    (net (code "19") (name "CS1_COMP3") (class "Default")
      (node (ref "10POT1_COMP2") (pin "1") (pinfunction "~{CS}_1") (pintype "input"))
      (node (ref "U5") (pin "4") (pinfunction "S3_4") (pintype "bidirectional"))
    )
    (net (code "20") (name "CS1_COMP4") (class "Default")
      (node (ref "10POT1_COMP5") (pin "1") (pinfunction "~{CS}_1") (pintype "input"))
      (node (ref "U5") (pin "7") (pinfunction "S4_7") (pintype "bidirectional"))
    )
    (net (code "21") (name "CS2") (class "Default")
      (node (ref "CS5") (pin "1") (pinfunction "P_1") (pintype "passive"))
      (node (ref "U4") (pin "8") (pinfunction "D_8") (pintype "bidirectional"))
    )
    (net (code "22") (name "CS2_COMP1") (class "Default")
      (node (ref "10POT2_COMP1") (pin "1") (pinfunction "~{CS}_1") (pintype "input"))
      (node (ref "U4") (pin "2") (pinfunction "S1_2") (pintype "bidirectional"))
    )
    (net (code "23") (name "CS2_COMP2") (class "Default")
      (node (ref "10POT2_COMP3") (pin "1") (pinfunction "~{CS}_1") (pintype "input"))
      (node (ref "U4") (pin "9") (pinfunction "S2_9") (pintype "bidirectional"))
    )
    (net (code "24") (name "CS2_COMP3") (class "Default")
      (node (ref "10POT2_COMP2") (pin "1") (pinfunction "~{CS}_1") (pintype "input"))
      (node (ref "U4") (pin "4") (pinfunction "S3_4") (pintype "bidirectional"))
    )
    (net (code "25") (name "CS2_COMP4") (class "Default")
      (node (ref "10POT2_COMP5") (pin "1") (pinfunction "~{CS}_1") (pintype "input"))
      (node (ref "U4") (pin "7") (pinfunction "S4_7") (pintype "bidirectional"))
    )
    (net (code "26") (name "CS_PAN1") (class "Default")
      (node (ref "10KPOT1_PAN1") (pin "1") (pinfunction "~{CS}_1") (pintype "input"))
      (node (ref "U11") (pin "2") (pinfunction "S1_2") (pintype "bidirectional"))
    )
    (net (code "27") (name "CS_PAN2") (class "Default")
      (node (ref "10KPOT1_PAN3") (pin "1") (pinfunction "~{CS}_1") (pintype "input"))
      (node (ref "U11") (pin "9") (pinfunction "S2_9") (pintype "bidirectional"))
    )
    (net (code "28") (name "CS_PAN3") (class "Default")
      (node (ref "10KPOT1_PAN2") (pin "1") (pinfunction "~{CS}_1") (pintype "input"))
      (node (ref "U11") (pin "4") (pinfunction "S3_4") (pintype "bidirectional"))
    )
    (net (code "29") (name "CS_PAN4") (class "Default")
      (node (ref "10KPOT1_PAN4") (pin "1") (pinfunction "~{CS}_1") (pintype "input"))
      (node (ref "U11") (pin "7") (pinfunction "S4_7") (pintype "bidirectional"))
    )
    (net (code "30") (name "DOUT_ADC") (class "Default")
      (node (ref "DOUT_ADC1") (pin "1") (pinfunction "P_1") (pintype "passive"))
      (node (ref "IC2") (pin "18") (pinfunction "DOUT_18") (pintype "bidirectional"))
    )
    (net (code "31") (name "GND") (class "Default")
      (node (ref "100POT1_COMP1") (pin "4") (pinfunction "VSS_4") (pintype "passive"))
      (node (ref "100POT1_COMP2") (pin "4") (pinfunction "VSS_4") (pintype "passive"))
      (node (ref "100POT1_COMP3") (pin "4") (pinfunction "VSS_4") (pintype "passive"))
      (node (ref "100POT1_COMP5") (pin "4") (pinfunction "VSS_4") (pintype "passive"))
      (node (ref "10KPOT1_PAN1") (pin "4") (pinfunction "VSS_4") (pintype "power_in"))
      (node (ref "10KPOT1_PAN2") (pin "4") (pinfunction "VSS_4") (pintype "power_in"))
      (node (ref "10KPOT1_PAN3") (pin "4") (pinfunction "VSS_4") (pintype "power_in"))
      (node (ref "10KPOT1_PAN4") (pin "4") (pinfunction "VSS_4") (pintype "power_in"))
      (node (ref "10POT1_COMP1") (pin "4") (pinfunction "VSS_4") (pintype "power_in"))
      (node (ref "10POT1_COMP2") (pin "4") (pinfunction "VSS_4") (pintype "power_in"))
      (node (ref "10POT1_COMP3") (pin "4") (pinfunction "VSS_4") (pintype "power_in"))
      (node (ref "10POT1_COMP5") (pin "4") (pinfunction "VSS_4") (pintype "power_in"))
      (node (ref "10POT2_COMP1") (pin "4") (pinfunction "VSS_4") (pintype "power_in"))
      (node (ref "10POT2_COMP2") (pin "4") (pinfunction "VSS_4") (pintype "power_in"))
      (node (ref "10POT2_COMP3") (pin "4") (pinfunction "VSS_4") (pintype "power_in"))
      (node (ref "10POT2_COMP5") (pin "4") (pinfunction "VSS_4") (pintype "power_in"))
      (node (ref "200POT1_COMP1") (pin "5") (pinfunction "GND_5") (pintype "power_in"))
      (node (ref "200POT1_COMP1") (pin "9") (pinfunction "EPAD_9") (pintype "power_in"))
      (node (ref "200POT1_COMP2") (pin "5") (pinfunction "GND_5") (pintype "power_in"))
      (node (ref "200POT1_COMP2") (pin "9") (pinfunction "EPAD_9") (pintype "power_in"))
      (node (ref "200POT1_COMP3") (pin "5") (pinfunction "GND_5") (pintype "power_in"))
      (node (ref "200POT1_COMP3") (pin "9") (pinfunction "EPAD_9") (pintype "power_in"))
      (node (ref "200POT1_COMP5") (pin "5") (pinfunction "GND_5") (pintype "power_in"))
      (node (ref "200POT1_COMP5") (pin "9") (pinfunction "EPAD_9") (pintype "power_in"))
      (node (ref "200POT2_COMP1") (pin "4") (pinfunction "A0_4") (pintype "input"))
      (node (ref "200POT2_COMP1") (pin "5") (pinfunction "GND_5") (pintype "power_in"))
      (node (ref "200POT2_COMP1") (pin "9") (pinfunction "EPAD_9") (pintype "power_in"))
      (node (ref "200POT2_COMP2") (pin "4") (pinfunction "A0_4") (pintype "input"))
      (node (ref "200POT2_COMP2") (pin "5") (pinfunction "GND_5") (pintype "power_in"))
      (node (ref "200POT2_COMP2") (pin "9") (pinfunction "EPAD_9") (pintype "power_in"))
      (node (ref "200POT2_COMP3") (pin "4") (pinfunction "A0_4") (pintype "input"))
      (node (ref "200POT2_COMP3") (pin "5") (pinfunction "GND_5") (pintype "power_in"))
      (node (ref "200POT2_COMP3") (pin "9") (pinfunction "EPAD_9") (pintype "power_in"))
      (node (ref "200POT2_COMP5") (pin "4") (pinfunction "A0_4") (pintype "input"))
      (node (ref "200POT2_COMP5") (pin "5") (pinfunction "GND_5") (pintype "power_in"))
      (node (ref "200POT2_COMP5") (pin "9") (pinfunction "EPAD_9") (pintype "power_in"))
      (node (ref "C123") (pin "2") (pinfunction "2_2") (pintype "passive"))
      (node (ref "C134") (pin "2") (pinfunction "2_2") (pintype "passive"))
      (node (ref "C28") (pin "2") (pinfunction "2_2") (pintype "passive"))
      (node (ref "C39") (pin "2") (pinfunction "2_2") (pintype "passive"))
      (node (ref "C68") (pin "2") (pinfunction "2_2") (pintype "passive"))
      (node (ref "C69") (pin "2") (pinfunction "2_2") (pintype "passive"))
      (node (ref "C70") (pin "2") (pinfunction "2_2") (pintype "passive"))
      (node (ref "C71") (pin "2") (pinfunction "2_2") (pintype "passive"))
      (node (ref "C72") (pin "2") (pinfunction "2_2") (pintype "passive"))
      (node (ref "C73") (pin "2") (pinfunction "2_2") (pintype "passive"))
      (node (ref "C74") (pin "2") (pinfunction "2_2") (pintype "passive"))
      (node (ref "C75") (pin "2") (pinfunction "2_2") (pintype "passive"))
      (node (ref "C76") (pin "2") (pinfunction "2_2") (pintype "passive"))
      (node (ref "GND1") (pin "1") (pinfunction "P_1") (pintype "passive"))
      (node (ref "GND2") (pin "1") (pinfunction "P_1") (pintype "passive"))
      (node (ref "GND3") (pin "1") (pinfunction "P_1") (pintype "passive"))
      (node (ref "GND4") (pin "1") (pinfunction "P_1") (pintype "passive"))
      (node (ref "GND5") (pin "1") (pinfunction "P_1") (pintype "passive"))
      (node (ref "GND6") (pin "1") (pinfunction "P_1") (pintype "passive"))
      (node (ref "GNDL1") (pin "1") (pinfunction "P_1") (pintype "passive"))
      (node (ref "GNDR1") (pin "1") (pinfunction "P_1") (pintype "passive"))
      (node (ref "IC2") (pin "12") (pinfunction "DGND_12") (pintype "bidirectional"))
      (node (ref "IC2") (pin "25") (pinfunction "MS/AD_25") (pintype "bidirectional"))
      (node (ref "IC2") (pin "7") (pinfunction "AGND_7") (pintype "bidirectional"))
      (node (ref "OPAMP1_COMP1") (pin "4") (pinfunction "V-_4") (pintype "power_in"))
      (node (ref "OPAMP1_COMP2") (pin "4") (pinfunction "V-_4") (pintype "power_in"))
      (node (ref "OPAMP1_COMP3") (pin "4") (pinfunction "V-_4") (pintype "power_in"))
      (node (ref "OPAMP1_COMP5") (pin "4") (pinfunction "V-_4") (pintype "power_in"))
      (node (ref "OPAMP1_MIX1") (pin "4") (pinfunction "V-_4") (pintype "power_in"))
      (node (ref "OPAMP1_PAN1") (pin "4") (pinfunction "V-_4") (pintype "power_in"))
      (node (ref "OPAMP1_PAN2") (pin "4") (pinfunction "V-_4") (pintype "power_in"))
      (node (ref "OPAMP1_PAN3") (pin "4") (pinfunction "V-_4") (pintype "power_in"))
      (node (ref "OPAMP1_PAN4") (pin "4") (pinfunction "V-_4") (pintype "power_in"))
      (node (ref "OPAMP2_COMP1") (pin "4") (pinfunction "V-_4") (pintype "power_in"))
      (node (ref "OPAMP2_COMP2") (pin "4") (pinfunction "V-_4") (pintype "power_in"))
      (node (ref "OPAMP2_COMP3") (pin "4") (pinfunction "V-_4") (pintype "power_in"))
      (node (ref "OPAMP2_COMP5") (pin "4") (pinfunction "V-_4") (pintype "power_in"))
      (node (ref "OPAMP3_COMP1") (pin "4") (pinfunction "V-_4") (pintype "power_in"))
      (node (ref "OPAMP3_COMP2") (pin "4") (pinfunction "V-_4") (pintype "power_in"))
      (node (ref "OPAMP3_COMP3") (pin "4") (pinfunction "V-_4") (pintype "power_in"))
      (node (ref "OPAMP3_COMP5") (pin "4") (pinfunction "V-_4") (pintype "power_in"))
      (node (ref "OPAMP4_COMP1") (pin "4") (pinfunction "V-_4") (pintype "power_in"))
      (node (ref "OPAMP4_COMP2") (pin "4") (pinfunction "V-_4") (pintype "power_in"))
      (node (ref "OPAMP4_COMP3") (pin "4") (pinfunction "V-_4") (pintype "power_in"))
      (node (ref "OPAMP4_COMP5") (pin "4") (pinfunction "V-_4") (pintype "power_in"))
      (node (ref "R5") (pin "1") (pinfunction "1_1") (pintype "passive"))
      (node (ref "R9") (pin "1") (pinfunction "1_1") (pintype "passive"))
      (node (ref "U$1") (pin "21") (pinfunction "V_SS_21") (pintype "bidirectional"))
      (node (ref "U$1") (pin "28") (pinfunction "TEST_28") (pintype "bidirectional"))
      (node (ref "U$3") (pin "21") (pinfunction "V_SS_21") (pintype "bidirectional"))
      (node (ref "U$3") (pin "28") (pinfunction "TEST_28") (pintype "bidirectional"))
      (node (ref "U11") (pin "3") (pinfunction "GND_3") (pintype "power_in"))
      (node (ref "U2") (pin "4") (pinfunction "V-_4") (pintype "power_in"))
      (node (ref "U3") (pin "3") (pinfunction "GND_3") (pintype "power_in"))
      (node (ref "U4") (pin "3") (pinfunction "GND_3") (pintype "power_in"))
      (node (ref "U5") (pin "3") (pinfunction "GND_3") (pintype "power_in"))
    )
    (net (code "32") (name "H1_COMP1") (class "Default")
      (node (ref "200POT1_COMP1") (pin "8") (pinfunction "H_8") (pintype "bidirectional"))
      (node (ref "200POT2_COMP1") (pin "8") (pinfunction "H_8") (pintype "bidirectional"))
      (node (ref "C44") (pin "1") (pinfunction "1_1") (pintype "passive"))
      (node (ref "OPAMP1_COMP1") (pin "6") (pinfunction "NEG_B_6") (pintype "input"))
      (node (ref "R66") (pin "1") (pinfunction "1_1") (pintype "passive"))
    )
    (net (code "33") (name "H1_COMP2") (class "Default")
      (node (ref "200POT1_COMP3") (pin "8") (pinfunction "H_8") (pintype "bidirectional"))
      (node (ref "200POT2_COMP3") (pin "8") (pinfunction "H_8") (pintype "bidirectional"))
      (node (ref "C50") (pin "1") (pinfunction "1_1") (pintype "passive"))
      (node (ref "OPAMP1_COMP3") (pin "6") (pinfunction "NEG_B_6") (pintype "input"))
      (node (ref "R116") (pin "1") (pinfunction "1_1") (pintype "passive"))
    )
    (net (code "34") (name "H1_COMP3") (class "Default")
      (node (ref "200POT1_COMP2") (pin "8") (pinfunction "H_8") (pintype "bidirectional"))
      (node (ref "200POT2_COMP2") (pin "8") (pinfunction "H_8") (pintype "bidirectional"))
      (node (ref "C47") (pin "1") (pinfunction "1_1") (pintype "passive"))
      (node (ref "OPAMP1_COMP2") (pin "6") (pinfunction "NEG_B_6") (pintype "input"))
      (node (ref "R98") (pin "1") (pinfunction "1_1") (pintype "passive"))
    )
    (net (code "35") (name "H1_COMP4") (class "Default")
      (node (ref "200POT1_COMP5") (pin "8") (pinfunction "H_8") (pintype "bidirectional"))
      (node (ref "200POT2_COMP5") (pin "8") (pinfunction "H_8") (pintype "bidirectional"))
      (node (ref "C56") (pin "1") (pinfunction "1_1") (pintype "passive"))
      (node (ref "OPAMP1_COMP5") (pin "6") (pinfunction "NEG_B_6") (pintype "input"))
      (node (ref "R152") (pin "1") (pinfunction "1_1") (pintype "passive"))
    )
    (net (code "36") (name "L1_COMP1") (class "Default")
      (node (ref "200POT1_COMP1") (pin "6") (pinfunction "L_6") (pintype "bidirectional"))
      (node (ref "200POT1_COMP1") (pin "7") (pinfunction "W_7") (pintype "bidirectional"))
      (node (ref "D19") (pin "1") (pinfunction "1_1") (pintype "passive"))
    )
    (net (code "37") (name "L1_COMP2") (class "Default")
      (node (ref "200POT1_COMP3") (pin "6") (pinfunction "L_6") (pintype "bidirectional"))
      (node (ref "200POT1_COMP3") (pin "7") (pinfunction "W_7") (pintype "bidirectional"))
      (node (ref "D41") (pin "1") (pinfunction "1_1") (pintype "passive"))
    )
    (net (code "38") (name "L1_COMP3") (class "Default")
      (node (ref "200POT1_COMP2") (pin "6") (pinfunction "L_6") (pintype "bidirectional"))
      (node (ref "200POT1_COMP2") (pin "7") (pinfunction "W_7") (pintype "bidirectional"))
      (node (ref "D30") (pin "1") (pinfunction "1_1") (pintype "passive"))
    )
    (net (code "39") (name "L1_COMP4") (class "Default")
      (node (ref "200POT1_COMP5") (pin "6") (pinfunction "L_6") (pintype "bidirectional"))
      (node (ref "200POT1_COMP5") (pin "7") (pinfunction "W_7") (pintype "bidirectional"))
      (node (ref "D63") (pin "1") (pinfunction "1_1") (pintype "passive"))
    )
    (net (code "40") (name "L2_COMP1") (class "Default")
      (node (ref "200POT2_COMP1") (pin "6") (pinfunction "L_6") (pintype "bidirectional"))
      (node (ref "200POT2_COMP1") (pin "7") (pinfunction "W_7") (pintype "bidirectional"))
      (node (ref "R94") (pin "2") (pinfunction "2_2") (pintype "passive"))
    )
    (net (code "41") (name "L2_COMP2") (class "Default")
      (node (ref "200POT2_COMP3") (pin "6") (pinfunction "L_6") (pintype "bidirectional"))
      (node (ref "200POT2_COMP3") (pin "7") (pinfunction "W_7") (pintype "bidirectional"))
      (node (ref "R130") (pin "2") (pinfunction "2_2") (pintype "passive"))
    )
    (net (code "42") (name "L2_COMP3") (class "Default")
      (node (ref "200POT2_COMP2") (pin "6") (pinfunction "L_6") (pintype "bidirectional"))
      (node (ref "200POT2_COMP2") (pin "7") (pinfunction "W_7") (pintype "bidirectional"))
      (node (ref "R112") (pin "2") (pinfunction "2_2") (pintype "passive"))
    )
    (net (code "43") (name "L2_COMP4") (class "Default")
      (node (ref "200POT2_COMP5") (pin "6") (pinfunction "L_6") (pintype "bidirectional"))
      (node (ref "200POT2_COMP5") (pin "7") (pinfunction "W_7") (pintype "bidirectional"))
      (node (ref "R166") (pin "2") (pinfunction "2_2") (pintype "passive"))
    )
    (net (code "44") (name "LRCK_ADC") (class "Default")
      (node (ref "IC2") (pin "16") (pinfunction "LRCK_16") (pintype "bidirectional"))
      (node (ref "LRCK_ADC1") (pin "1") (pinfunction "P_1") (pintype "passive"))
    )
    (net (code "45") (name "MUX0") (class "Default")
      (node (ref "MUX2") (pin "1") (pinfunction "P_1") (pintype "passive"))
      (node (ref "U11") (pin "1") (pinfunction "A0_1") (pintype "input"))
      (node (ref "U3") (pin "1") (pinfunction "A0_1") (pintype "input"))
      (node (ref "U4") (pin "1") (pinfunction "A0_1") (pintype "input"))
      (node (ref "U5") (pin "1") (pinfunction "A0_1") (pintype "input"))
    )
    (net (code "46") (name "MUX1") (class "Default")
      (node (ref "MUX3") (pin "1") (pinfunction "P_1") (pintype "passive"))
      (node (ref "U11") (pin "10") (pinfunction "A1_10") (pintype "bidirectional"))
      (node (ref "U3") (pin "10") (pinfunction "A1_10") (pintype "bidirectional"))
      (node (ref "U4") (pin "10") (pinfunction "A1_10") (pintype "bidirectional"))
      (node (ref "U5") (pin "10") (pinfunction "A1_10") (pintype "bidirectional"))
    )
    (net (code "47") (name "NEG_A1_COMP1") (class "Default")
      (node (ref "C42") (pin "2") (pinfunction "2_2") (pintype "passive"))
      (node (ref "D16") (pin "1") (pinfunction "1_1") (pintype "passive"))
      (node (ref "D18") (pin "2") (pinfunction "2_2") (pintype "passive"))
      (node (ref "OPAMP1_COMP1") (pin "2") (pinfunction "NEG_A_2") (pintype "input"))
      (node (ref "R63") (pin "2") (pinfunction "2_2") (pintype "passive"))
    )
    (net (code "48") (name "NEG_A1_COMP2") (class "Default")
      (node (ref "C48") (pin "2") (pinfunction "2_2") (pintype "passive"))
      (node (ref "D38") (pin "1") (pinfunction "1_1") (pintype "passive"))
      (node (ref "D40") (pin "2") (pinfunction "2_2") (pintype "passive"))
      (node (ref "OPAMP1_COMP3") (pin "2") (pinfunction "NEG_A_2") (pintype "input"))
      (node (ref "R113") (pin "2") (pinfunction "2_2") (pintype "passive"))
    )
    (net (code "49") (name "NEG_A1_COMP3") (class "Default")
      (node (ref "C45") (pin "2") (pinfunction "2_2") (pintype "passive"))
      (node (ref "D27") (pin "1") (pinfunction "1_1") (pintype "passive"))
      (node (ref "D29") (pin "2") (pinfunction "2_2") (pintype "passive"))
      (node (ref "OPAMP1_COMP2") (pin "2") (pinfunction "NEG_A_2") (pintype "input"))
      (node (ref "R95") (pin "2") (pinfunction "2_2") (pintype "passive"))
    )
    (net (code "50") (name "NEG_A1_COMP4") (class "Default")
      (node (ref "C54") (pin "2") (pinfunction "2_2") (pintype "passive"))
      (node (ref "D60") (pin "1") (pinfunction "1_1") (pintype "passive"))
      (node (ref "D62") (pin "2") (pinfunction "2_2") (pintype "passive"))
      (node (ref "OPAMP1_COMP5") (pin "2") (pinfunction "NEG_A_2") (pintype "input"))
      (node (ref "R149") (pin "2") (pinfunction "2_2") (pintype "passive"))
    )
    (net (code "51") (name "NEG_A2_COMP1") (class "Default")
      (node (ref "OPAMP2_COMP1") (pin "2") (pinfunction "NEG_A_2") (pintype "input"))
      (node (ref "R67") (pin "2") (pinfunction "2_2") (pintype "passive"))
      (node (ref "R75") (pin "1") (pinfunction "1_1") (pintype "passive"))
    )
    (net (code "52") (name "NEG_A2_COMP2") (class "Default")
      (node (ref "OPAMP2_COMP3") (pin "2") (pinfunction "NEG_A_2") (pintype "input"))
      (node (ref "R117") (pin "2") (pinfunction "2_2") (pintype "passive"))
      (node (ref "R118") (pin "1") (pinfunction "1_1") (pintype "passive"))
    )
    (net (code "53") (name "NEG_A2_COMP3") (class "Default")
      (node (ref "OPAMP2_COMP2") (pin "2") (pinfunction "NEG_A_2") (pintype "input"))
      (node (ref "R100") (pin "1") (pinfunction "1_1") (pintype "passive"))
      (node (ref "R99") (pin "2") (pinfunction "2_2") (pintype "passive"))
    )
    (net (code "54") (name "NEG_A2_COMP4") (class "Default")
      (node (ref "OPAMP2_COMP5") (pin "2") (pinfunction "NEG_A_2") (pintype "input"))
      (node (ref "R153") (pin "2") (pinfunction "2_2") (pintype "passive"))
      (node (ref "R154") (pin "1") (pinfunction "1_1") (pintype "passive"))
    )
    (net (code "55") (name "NEG_A3_COMP1") (class "Default")
      (node (ref "OPAMP3_COMP1") (pin "2") (pinfunction "NEG_A_2") (pintype "input"))
      (node (ref "R77") (pin "1") (pinfunction "1_1") (pintype "passive"))
      (node (ref "R78") (pin "2") (pinfunction "2_2") (pintype "passive"))
    )
    (net (code "56") (name "NEG_A3_COMP2") (class "Default")
      (node (ref "OPAMP3_COMP3") (pin "2") (pinfunction "NEG_A_2") (pintype "input"))
      (node (ref "R120") (pin "1") (pinfunction "1_1") (pintype "passive"))
      (node (ref "R121") (pin "2") (pinfunction "2_2") (pintype "passive"))
    )
    (net (code "57") (name "NEG_A3_COMP3") (class "Default")
      (node (ref "OPAMP3_COMP2") (pin "2") (pinfunction "NEG_A_2") (pintype "input"))
      (node (ref "R102") (pin "1") (pinfunction "1_1") (pintype "passive"))
      (node (ref "R103") (pin "2") (pinfunction "2_2") (pintype "passive"))
    )
    (net (code "58") (name "NEG_A3_COMP4") (class "Default")
      (node (ref "OPAMP3_COMP5") (pin "2") (pinfunction "NEG_A_2") (pintype "input"))
      (node (ref "R156") (pin "1") (pinfunction "1_1") (pintype "passive"))
      (node (ref "R157") (pin "2") (pinfunction "2_2") (pintype "passive"))
    )
    (net (code "59") (name "NEG_A4_COMP1") (class "Default")
      (node (ref "OPAMP4_COMP1") (pin "2") (pinfunction "NEG_A_2") (pintype "input"))
      (node (ref "R79") (pin "2") (pinfunction "2_2") (pintype "passive"))
      (node (ref "R80") (pin "2") (pinfunction "2_2") (pintype "passive"))
    )
    (net (code "60") (name "NEG_A4_COMP2") (class "Default")
      (node (ref "OPAMP4_COMP3") (pin "2") (pinfunction "NEG_A_2") (pintype "input"))
      (node (ref "R122") (pin "2") (pinfunction "2_2") (pintype "passive"))
      (node (ref "R123") (pin "2") (pinfunction "2_2") (pintype "passive"))
    )
    (net (code "61") (name "NEG_A4_COMP3") (class "Default")
      (node (ref "OPAMP4_COMP2") (pin "2") (pinfunction "NEG_A_2") (pintype "input"))
      (node (ref "R104") (pin "2") (pinfunction "2_2") (pintype "passive"))
      (node (ref "R105") (pin "2") (pinfunction "2_2") (pintype "passive"))
    )
    (net (code "62") (name "NEG_A4_COMP4") (class "Default")
      (node (ref "OPAMP4_COMP5") (pin "2") (pinfunction "NEG_A_2") (pintype "input"))
      (node (ref "R158") (pin "2") (pinfunction "2_2") (pintype "passive"))
      (node (ref "R159") (pin "2") (pinfunction "2_2") (pintype "passive"))
    )
    (net (code "63") (name "NEG_A_MIX") (class "Default")
      (node (ref "OPAMP1_MIX1") (pin "2") (pinfunction "NEG_A_2") (pintype "input"))
      (node (ref "R43") (pin "2") (pinfunction "2_2") (pintype "passive"))
      (node (ref "R44") (pin "1") (pinfunction "1_1") (pintype "passive"))
    )
    (net (code "64") (name "NEG_A_PAN1") (class "Default")
      (node (ref "OPAMP1_PAN1") (pin "2") (pinfunction "NEG_A_2") (pintype "input"))
      (node (ref "R71") (pin "1") (pinfunction "1_1") (pintype "passive"))
      (node (ref "R74") (pin "1") (pinfunction "1_1") (pintype "passive"))
    )
    (net (code "65") (name "NEG_A_PAN2") (class "Default")
      (node (ref "OPAMP1_PAN3") (pin "2") (pinfunction "NEG_A_2") (pintype "input"))
      (node (ref "R85") (pin "1") (pinfunction "1_1") (pintype "passive"))
      (node (ref "R88") (pin "1") (pinfunction "1_1") (pintype "passive"))
    )
    (net (code "66") (name "NEG_A_PAN3") (class "Default")
      (node (ref "OPAMP1_PAN2") (pin "2") (pinfunction "NEG_A_2") (pintype "input"))
      (node (ref "R11") (pin "1") (pinfunction "1_1") (pintype "passive"))
      (node (ref "R14") (pin "1") (pinfunction "1_1") (pintype "passive"))
    )
    (net (code "67") (name "NEG_A_PAN4") (class "Default")
      (node (ref "OPAMP1_PAN4") (pin "2") (pinfunction "NEG_A_2") (pintype "input"))
      (node (ref "R18") (pin "1") (pinfunction "1_1") (pintype "passive"))
      (node (ref "R21") (pin "1") (pinfunction "1_1") (pintype "passive"))
    )
    (net (code "68") (name "NEG_B2_COMP1") (class "Default")
      (node (ref "OPAMP2_COMP1") (pin "6") (pinfunction "NEG_B_6") (pintype "input"))
      (node (ref "OPAMP2_COMP1") (pin "7") (pinfunction "OUT_B_7") (pintype "output"))
      (node (ref "R93") (pin "2") (pinfunction "2_2") (pintype "passive"))
    )
    (net (code "69") (name "NEG_B2_COMP2") (class "Default")
      (node (ref "OPAMP2_COMP3") (pin "6") (pinfunction "NEG_B_6") (pintype "input"))
      (node (ref "OPAMP2_COMP3") (pin "7") (pinfunction "OUT_B_7") (pintype "output"))
      (node (ref "R129") (pin "2") (pinfunction "2_2") (pintype "passive"))
    )
    (net (code "70") (name "NEG_B2_COMP3") (class "Default")
      (node (ref "OPAMP2_COMP2") (pin "6") (pinfunction "NEG_B_6") (pintype "input"))
      (node (ref "OPAMP2_COMP2") (pin "7") (pinfunction "OUT_B_7") (pintype "output"))
      (node (ref "R111") (pin "2") (pinfunction "2_2") (pintype "passive"))
    )
    (net (code "71") (name "NEG_B2_COMP4") (class "Default")
      (node (ref "OPAMP2_COMP5") (pin "6") (pinfunction "NEG_B_6") (pintype "input"))
      (node (ref "OPAMP2_COMP5") (pin "7") (pinfunction "OUT_B_7") (pintype "output"))
      (node (ref "R165") (pin "2") (pinfunction "2_2") (pintype "passive"))
    )
    (net (code "72") (name "NEG_B3_COMP1") (class "Default")
      (node (ref "OPAMP3_COMP1") (pin "6") (pinfunction "NEG_B_6") (pintype "input"))
      (node (ref "R89") (pin "1") (pinfunction "1_1") (pintype "passive"))
      (node (ref "R90") (pin "2") (pinfunction "2_2") (pintype "passive"))
    )
    (net (code "73") (name "NEG_B3_COMP2") (class "Default")
      (node (ref "OPAMP3_COMP3") (pin "6") (pinfunction "NEG_B_6") (pintype "input"))
      (node (ref "R125") (pin "1") (pinfunction "1_1") (pintype "passive"))
      (node (ref "R126") (pin "2") (pinfunction "2_2") (pintype "passive"))
    )
    (net (code "74") (name "NEG_B3_COMP3") (class "Default")
      (node (ref "OPAMP3_COMP2") (pin "6") (pinfunction "NEG_B_6") (pintype "input"))
      (node (ref "R107") (pin "1") (pinfunction "1_1") (pintype "passive"))
      (node (ref "R108") (pin "2") (pinfunction "2_2") (pintype "passive"))
    )
    (net (code "75") (name "NEG_B3_COMP4") (class "Default")
      (node (ref "OPAMP3_COMP5") (pin "6") (pinfunction "NEG_B_6") (pintype "input"))
      (node (ref "R161") (pin "1") (pinfunction "1_1") (pintype "passive"))
      (node (ref "R162") (pin "2") (pinfunction "2_2") (pintype "passive"))
    )
    (net (code "76") (name "NEG_B4_COMP1") (class "Default")
      (node (ref "100POT1_COMP1") (pin "5") (pinfunction "PB1_5") (pintype "passive"))
      (node (ref "OPAMP4_COMP1") (pin "6") (pinfunction "NEG_B_6") (pintype "input"))
      (node (ref "R81") (pin "2") (pinfunction "2_2") (pintype "passive"))
    )
    (net (code "77") (name "NEG_B4_COMP2") (class "Default")
      (node (ref "100POT1_COMP3") (pin "5") (pinfunction "PB1_5") (pintype "passive"))
      (node (ref "OPAMP4_COMP3") (pin "6") (pinfunction "NEG_B_6") (pintype "input"))
      (node (ref "R124") (pin "2") (pinfunction "2_2") (pintype "passive"))
    )
    (net (code "78") (name "NEG_B4_COMP3") (class "Default")
      (node (ref "100POT1_COMP2") (pin "5") (pinfunction "PB1_5") (pintype "passive"))
      (node (ref "OPAMP4_COMP2") (pin "6") (pinfunction "NEG_B_6") (pintype "input"))
      (node (ref "R106") (pin "2") (pinfunction "2_2") (pintype "passive"))
    )
    (net (code "79") (name "NEG_B4_COMP4") (class "Default")
      (node (ref "100POT1_COMP5") (pin "5") (pinfunction "PB1_5") (pintype "passive"))
      (node (ref "OPAMP4_COMP5") (pin "6") (pinfunction "NEG_B_6") (pintype "input"))
      (node (ref "R160") (pin "2") (pinfunction "2_2") (pintype "passive"))
    )
    (net (code "80") (name "NEG_B_MIX") (class "Default")
      (node (ref "OPAMP1_MIX1") (pin "6") (pinfunction "NEG_B_6") (pintype "input"))
      (node (ref "R58") (pin "2") (pinfunction "2_2") (pintype "passive"))
      (node (ref "R59") (pin "1") (pinfunction "1_1") (pintype "passive"))
    )
    (net (code "81") (name "NEG_B_PAN1") (class "Default")
      (node (ref "OPAMP1_PAN1") (pin "6") (pinfunction "NEG_B_6") (pintype "input"))
      (node (ref "R72") (pin "2") (pinfunction "2_2") (pintype "passive"))
      (node (ref "R73") (pin "2") (pinfunction "2_2") (pintype "passive"))
    )
    (net (code "82") (name "NEG_B_PAN2") (class "Default")
      (node (ref "OPAMP1_PAN3") (pin "6") (pinfunction "NEG_B_6") (pintype "input"))
      (node (ref "R86") (pin "2") (pinfunction "2_2") (pintype "passive"))
      (node (ref "R87") (pin "2") (pinfunction "2_2") (pintype "passive"))
    )
    (net (code "83") (name "NEG_B_PAN3") (class "Default")
      (node (ref "OPAMP1_PAN2") (pin "6") (pinfunction "NEG_B_6") (pintype "input"))
      (node (ref "R12") (pin "2") (pinfunction "2_2") (pintype "passive"))
      (node (ref "R13") (pin "2") (pinfunction "2_2") (pintype "passive"))
    )
    (net (code "84") (name "NEG_B_PAN4") (class "Default")
      (node (ref "OPAMP1_PAN4") (pin "6") (pinfunction "NEG_B_6") (pintype "input"))
      (node (ref "R19") (pin "2") (pinfunction "2_2") (pintype "passive"))
      (node (ref "R20") (pin "2") (pinfunction "2_2") (pintype "passive"))
    )
    (net (code "85") (name "Net-(C2-Pad2)") (class "Default")
      (node (ref "C2") (pin "2") (pinfunction "2_2") (pintype "passive"))
      (node (ref "R10") (pin "2") (pinfunction "2_2") (pintype "passive"))
      (node (ref "R6") (pin "2") (pinfunction "2_2") (pintype "passive"))
      (node (ref "R7") (pin "2") (pinfunction "2_2") (pintype "passive"))
    )
    (net (code "86") (name "Net-(C3-Pad1)") (class "Default")
      (node (ref "C3") (pin "1") (pinfunction "1_1") (pintype "passive"))
      (node (ref "R45") (pin "2") (pinfunction "2_2") (pintype "passive"))
    )
    (net (code "87") (name "Net-(C4-Pad1)") (class "Default")
      (node (ref "C4") (pin "1") (pinfunction "1_1") (pintype "passive"))
      (node (ref "R60") (pin "2") (pinfunction "2_2") (pintype "passive"))
    )
    (net (code "88") (name "Net-(C5-Pad2)") (class "Default")
      (node (ref "C5") (pin "2") (pinfunction "2_2") (pintype "passive"))
      (node (ref "R15") (pin "2") (pinfunction "2_2") (pintype "passive"))
      (node (ref "R16") (pin "2") (pinfunction "2_2") (pintype "passive"))
      (node (ref "R17") (pin "2") (pinfunction "2_2") (pintype "passive"))
    )
    (net (code "89") (name "Net-(C6-Pad2)") (class "Default")
      (node (ref "C6") (pin "2") (pinfunction "2_2") (pintype "passive"))
      (node (ref "R68") (pin "2") (pinfunction "2_2") (pintype "passive"))
      (node (ref "R69") (pin "2") (pinfunction "2_2") (pintype "passive"))
      (node (ref "R70") (pin "2") (pinfunction "2_2") (pintype "passive"))
    )
    (net (code "90") (name "Net-(C8-Pad2)") (class "Default")
      (node (ref "C8") (pin "2") (pinfunction "2_2") (pintype "passive"))
      (node (ref "R82") (pin "2") (pinfunction "2_2") (pintype "passive"))
      (node (ref "R83") (pin "2") (pinfunction "2_2") (pintype "passive"))
      (node (ref "R84") (pin "2") (pinfunction "2_2") (pintype "passive"))
    )
    (net (code "91") (name "Net-(C43-Pad1)") (class "Default")
      (node (ref "C43") (pin "1") (pinfunction "1_1") (pintype "passive"))
      (node (ref "R91") (pin "2") (pinfunction "2_2") (pintype "passive"))
    )
    (net (code "92") (name "Net-(C46-Pad1)") (class "Default")
      (node (ref "C46") (pin "1") (pinfunction "1_1") (pintype "passive"))
      (node (ref "R109") (pin "2") (pinfunction "2_2") (pintype "passive"))
    )
    (net (code "93") (name "Net-(C49-Pad1)") (class "Default")
      (node (ref "C49") (pin "1") (pinfunction "1_1") (pintype "passive"))
      (node (ref "R127") (pin "2") (pinfunction "2_2") (pintype "passive"))
    )
    (net (code "94") (name "Net-(C55-Pad1)") (class "Default")
      (node (ref "C55") (pin "1") (pinfunction "1_1") (pintype "passive"))
      (node (ref "R163") (pin "2") (pinfunction "2_2") (pintype "passive"))
    )
    (net (code "95") (name "Net-(CE_EQ1-P)") (class "Default")
      (node (ref "CE_EQ1") (pin "1") (pinfunction "P_1") (pintype "passive"))
      (node (ref "U$1") (pin "27") (pinfunction "CE_27") (pintype "bidirectional"))
    )
    (net (code "96") (name "Net-(CE_EQ2-P)") (class "Default")
      (node (ref "CE_EQ2") (pin "1") (pinfunction "P_1") (pintype "passive"))
      (node (ref "U$3") (pin "27") (pinfunction "CE_27") (pintype "bidirectional"))
    )
    (net (code "97") (name "Net-(D16-Pad2)") (class "Default")
      (node (ref "D16") (pin "2") (pinfunction "2_2") (pintype "passive"))
      (node (ref "D17") (pin "1") (pinfunction "1_1") (pintype "passive"))
    )
    (net (code "98") (name "Net-(D20-Pad2)") (class "Default")
      (node (ref "D20") (pin "2") (pinfunction "2_2") (pintype "passive"))
      (node (ref "D21") (pin "1") (pinfunction "1_1") (pintype "passive"))
    )
    (net (code "99") (name "Net-(D21-Pad2)") (class "Default")
      (node (ref "D21") (pin "2") (pinfunction "2_2") (pintype "passive"))
      (node (ref "D22") (pin "1") (pinfunction "1_1") (pintype "passive"))
    )
    (net (code "100") (name "Net-(D23-Pad2)") (class "Default")
      (node (ref "D23") (pin "2") (pinfunction "2_2") (pintype "passive"))
      (node (ref "D24") (pin "1") (pinfunction "1_1") (pintype "passive"))
    )
    (net (code "101") (name "Net-(D24-Pad2)") (class "Default")
      (node (ref "D24") (pin "2") (pinfunction "2_2") (pintype "passive"))
      (node (ref "D25") (pin "1") (pinfunction "1_1") (pintype "passive"))
    )
    (net (code "102") (name "Net-(D27-Pad2)") (class "Default")
      (node (ref "D27") (pin "2") (pinfunction "2_2") (pintype "passive"))
      (node (ref "D28") (pin "1") (pinfunction "1_1") (pintype "passive"))
    )
    (net (code "103") (name "Net-(D31-Pad2)") (class "Default")
      (node (ref "D31") (pin "2") (pinfunction "2_2") (pintype "passive"))
      (node (ref "D32") (pin "1") (pinfunction "1_1") (pintype "passive"))
    )
    (net (code "104") (name "Net-(D32-Pad2)") (class "Default")
      (node (ref "D32") (pin "2") (pinfunction "2_2") (pintype "passive"))
      (node (ref "D33") (pin "1") (pinfunction "1_1") (pintype "passive"))
    )
    (net (code "105") (name "Net-(D34-Pad2)") (class "Default")
      (node (ref "D34") (pin "2") (pinfunction "2_2") (pintype "passive"))
      (node (ref "D35") (pin "1") (pinfunction "1_1") (pintype "passive"))
    )
    (net (code "106") (name "Net-(D35-Pad2)") (class "Default")
      (node (ref "D35") (pin "2") (pinfunction "2_2") (pintype "passive"))
      (node (ref "D36") (pin "1") (pinfunction "1_1") (pintype "passive"))
    )
    (net (code "107") (name "Net-(D38-Pad2)") (class "Default")
      (node (ref "D38") (pin "2") (pinfunction "2_2") (pintype "passive"))
      (node (ref "D39") (pin "1") (pinfunction "1_1") (pintype "passive"))
    )
    (net (code "108") (name "Net-(D42-Pad2)") (class "Default")
      (node (ref "D42") (pin "2") (pinfunction "2_2") (pintype "passive"))
      (node (ref "D43") (pin "1") (pinfunction "1_1") (pintype "passive"))
    )
    (net (code "109") (name "Net-(D43-Pad2)") (class "Default")
      (node (ref "D43") (pin "2") (pinfunction "2_2") (pintype "passive"))
      (node (ref "D44") (pin "1") (pinfunction "1_1") (pintype "passive"))
    )
    (net (code "110") (name "Net-(D45-Pad2)") (class "Default")
      (node (ref "D45") (pin "2") (pinfunction "2_2") (pintype "passive"))
      (node (ref "D46") (pin "1") (pinfunction "1_1") (pintype "passive"))
    )
    (net (code "111") (name "Net-(D46-Pad2)") (class "Default")
      (node (ref "D46") (pin "2") (pinfunction "2_2") (pintype "passive"))
      (node (ref "D47") (pin "1") (pinfunction "1_1") (pintype "passive"))
    )
    (net (code "112") (name "Net-(D60-Pad2)") (class "Default")
      (node (ref "D60") (pin "2") (pinfunction "2_2") (pintype "passive"))
      (node (ref "D61") (pin "1") (pinfunction "1_1") (pintype "passive"))
    )
    (net (code "113") (name "Net-(D64-Pad2)") (class "Default")
      (node (ref "D64") (pin "2") (pinfunction "2_2") (pintype "passive"))
      (node (ref "D65") (pin "1") (pinfunction "1_1") (pintype "passive"))
    )
    (net (code "114") (name "Net-(D65-Pad2)") (class "Default")
      (node (ref "D65") (pin "2") (pinfunction "2_2") (pintype "passive"))
      (node (ref "D66") (pin "1") (pinfunction "1_1") (pintype "passive"))
    )
    (net (code "115") (name "Net-(D67-Pad2)") (class "Default")
      (node (ref "D67") (pin "2") (pinfunction "2_2") (pintype "passive"))
      (node (ref "D68") (pin "1") (pinfunction "1_1") (pintype "passive"))
    )
    (net (code "116") (name "Net-(D68-Pad2)") (class "Default")
      (node (ref "D68") (pin "2") (pinfunction "2_2") (pintype "passive"))
      (node (ref "D69") (pin "1") (pinfunction "1_1") (pintype "passive"))
    )
    (net (code "117") (name "Net-(IC2-LDO)") (class "Default")
      (node (ref "C73") (pin "1") (pinfunction "1_1") (pintype "passive"))
      (node (ref "C74") (pin "1") (pinfunction "1_1") (pintype "passive"))
      (node (ref "IC2") (pin "11") (pinfunction "LDO_11") (pintype "bidirectional"))
    )
    (net (code "118") (name "Net-(IC2-VINL1{slash}VIN1P)") (class "Default")
      (node (ref "C81") (pin "2") (pinfunction "2_2") (pintype "passive"))
      (node (ref "IC2") (pin "3") (pinfunction "VINL1/VIN1P_3") (pintype "bidirectional"))
    )
    (net (code "119") (name "Net-(IC2-VINL2{slash}VIN1M)") (class "Default")
      (node (ref "C84") (pin "2") (pinfunction "2_2") (pintype "passive"))
      (node (ref "IC2") (pin "1") (pinfunction "VINL2/VIN1M_1") (pintype "bidirectional"))
    )
    (net (code "120") (name "Net-(IC2-VINL3{slash}VIN4P)") (class "Default")
      (node (ref "C79") (pin "2") (pinfunction "2_2") (pintype "passive"))
      (node (ref "IC2") (pin "29") (pinfunction "VINL3/VIN4P_29") (pintype "bidirectional"))
    )
    (net (code "121") (name "Net-(IC2-VINL4{slash}VIN4M)") (class "Default")
      (node (ref "C80") (pin "2") (pinfunction "2_2") (pintype "passive"))
      (node (ref "IC2") (pin "27") (pinfunction "VINL4/VIN4M_27") (pintype "bidirectional"))
    )
    (net (code "122") (name "Net-(IC2-VINR1{slash}VIN2P)") (class "Default")
      (node (ref "C78") (pin "2") (pinfunction "2_2") (pintype "passive"))
      (node (ref "IC2") (pin "4") (pinfunction "VINR1/VIN2P_4") (pintype "bidirectional"))
    )
    (net (code "123") (name "Net-(IC2-VINR2{slash}VIN2M)") (class "Default")
      (node (ref "C77") (pin "2") (pinfunction "2_2") (pintype "passive"))
      (node (ref "IC2") (pin "2") (pinfunction "VINR2/VIN2M_2") (pintype "bidirectional"))
    )
    (net (code "124") (name "Net-(IC2-VINR3{slash}VIN3P)") (class "Default")
      (node (ref "C82") (pin "2") (pinfunction "2_2") (pintype "passive"))
      (node (ref "IC2") (pin "30") (pinfunction "VINR3/VIN3P_30") (pintype "bidirectional"))
    )
    (net (code "125") (name "Net-(IC2-VINR4{slash}VIN3M)") (class "Default")
      (node (ref "C83") (pin "2") (pinfunction "2_2") (pintype "passive"))
      (node (ref "IC2") (pin "28") (pinfunction "VINR4/VIN3M_28") (pintype "bidirectional"))
    )
    (net (code "126") (name "Net-(IC2-VREF)") (class "Default")
      (node (ref "C72") (pin "1") (pinfunction "1_1") (pintype "passive"))
      (node (ref "IC2") (pin "6") (pinfunction "VREF_6") (pintype "bidirectional"))
    )
    (net (code "127") (name "Net-(IC2-XI)") (class "Default")
      (node (ref "C76") (pin "1") (pinfunction "1_1") (pintype "passive"))
      (node (ref "IC2") (pin "10") (pinfunction "XI_10") (pintype "bidirectional"))
      (node (ref "Y2") (pin "1") (pinfunction "1_1") (pintype "passive"))
    )
    (net (code "128") (name "Net-(IC2-XO)") (class "Default")
      (node (ref "C75") (pin "1") (pinfunction "1_1") (pintype "passive"))
      (node (ref "IC2") (pin "9") (pinfunction "XO_9") (pintype "bidirectional"))
      (node (ref "Y2") (pin "2") (pinfunction "2_2") (pintype "passive"))
    )
    (net (code "129") (name "Net-(IN_COMP1-P)") (class "Default")
      (node (ref "C43") (pin "2") (pinfunction "2_2") (pintype "passive"))
      (node (ref "IN_COMP1") (pin "1") (pinfunction "P_1") (pintype "passive"))
    )
    (net (code "130") (name "Net-(IN_COMP2-P)") (class "Default")
      (node (ref "C46") (pin "2") (pinfunction "2_2") (pintype "passive"))
      (node (ref "IN_COMP2") (pin "1") (pinfunction "P_1") (pintype "passive"))
    )
    (net (code "131") (name "Net-(IN_COMP3-P)") (class "Default")
      (node (ref "C49") (pin "2") (pinfunction "2_2") (pintype "passive"))
      (node (ref "IN_COMP3") (pin "1") (pinfunction "P_1") (pintype "passive"))
    )
    (net (code "132") (name "Net-(IN_COMP5-P)") (class "Default")
      (node (ref "C55") (pin "2") (pinfunction "2_2") (pintype "passive"))
      (node (ref "IN_COMP5") (pin "1") (pinfunction "P_1") (pintype "passive"))
    )
    (net (code "133") (name "Net-(OUTL_MIX1-P)") (class "Default")
      (node (ref "C3") (pin "2") (pinfunction "2_2") (pintype "passive"))
      (node (ref "OUTL_MIX1") (pin "1") (pinfunction "P_1") (pintype "passive"))
    )
    (net (code "134") (name "Net-(OUTR_MIX1-P)") (class "Default")
      (node (ref "C4") (pin "2") (pinfunction "2_2") (pintype "passive"))
      (node (ref "OUTR_MIX1") (pin "1") (pinfunction "P_1") (pintype "passive"))
    )
    (net (code "135") (name "Net-(R31-Pad2)") (class "Default")
      (node (ref "R31") (pin "2") (pinfunction "2_2") (pintype "passive"))
      (node (ref "R38") (pin "1") (pinfunction "1_1") (pintype "passive"))
      (node (ref "R42") (pin "1") (pinfunction "1_1") (pintype "passive"))
    )
    (net (code "136") (name "Net-(R32-Pad1)") (class "Default")
      (node (ref "R32") (pin "1") (pinfunction "1_1") (pintype "passive"))
      (node (ref "R35") (pin "2") (pinfunction "2_2") (pintype "passive"))
      (node (ref "R39") (pin "2") (pinfunction "2_2") (pintype "passive"))
    )
    (net (code "137") (name "Net-(R32-Pad2)") (class "Default")
      (node (ref "R32") (pin "2") (pinfunction "2_2") (pintype "passive"))
      (node (ref "R34") (pin "2") (pinfunction "2_2") (pintype "passive"))
      (node (ref "R41") (pin "2") (pinfunction "2_2") (pintype "passive"))
      (node (ref "R42") (pin "2") (pinfunction "2_2") (pintype "passive"))
      (node (ref "R43") (pin "1") (pinfunction "1_1") (pintype "passive"))
    )
    (net (code "138") (name "Net-(R33-Pad2)") (class "Default")
      (node (ref "R33") (pin "2") (pinfunction "2_2") (pintype "passive"))
      (node (ref "R37") (pin "1") (pinfunction "1_1") (pintype "passive"))
      (node (ref "R41") (pin "1") (pinfunction "1_1") (pintype "passive"))
    )
    (net (code "139") (name "Net-(R34-Pad1)") (class "Default")
      (node (ref "R34") (pin "1") (pinfunction "1_1") (pintype "passive"))
      (node (ref "R36") (pin "1") (pinfunction "1_1") (pintype "passive"))
      (node (ref "R40") (pin "2") (pinfunction "2_2") (pintype "passive"))
    )
    (net (code "140") (name "Net-(R46-Pad2)") (class "Default")
      (node (ref "R46") (pin "2") (pinfunction "2_2") (pintype "passive"))
      (node (ref "R53") (pin "1") (pinfunction "1_1") (pintype "passive"))
      (node (ref "R57") (pin "1") (pinfunction "1_1") (pintype "passive"))
    )
    (net (code "141") (name "Net-(R47-Pad1)") (class "Default")
      (node (ref "R47") (pin "1") (pinfunction "1_1") (pintype "passive"))
      (node (ref "R50") (pin "2") (pinfunction "2_2") (pintype "passive"))
      (node (ref "R54") (pin "2") (pinfunction "2_2") (pintype "passive"))
    )
    (net (code "142") (name "Net-(R47-Pad2)") (class "Default")
      (node (ref "R47") (pin "2") (pinfunction "2_2") (pintype "passive"))
      (node (ref "R49") (pin "2") (pinfunction "2_2") (pintype "passive"))
      (node (ref "R56") (pin "2") (pinfunction "2_2") (pintype "passive"))
      (node (ref "R57") (pin "2") (pinfunction "2_2") (pintype "passive"))
      (node (ref "R58") (pin "1") (pinfunction "1_1") (pintype "passive"))
    )
    (net (code "143") (name "Net-(R48-Pad2)") (class "Default")
      (node (ref "R48") (pin "2") (pinfunction "2_2") (pintype "passive"))
      (node (ref "R52") (pin "1") (pinfunction "1_1") (pintype "passive"))
      (node (ref "R56") (pin "1") (pinfunction "1_1") (pintype "passive"))
    )
    (net (code "144") (name "Net-(R49-Pad1)") (class "Default")
      (node (ref "R49") (pin "1") (pinfunction "1_1") (pintype "passive"))
      (node (ref "R51") (pin "1") (pinfunction "1_1") (pintype "passive"))
      (node (ref "R55") (pin "2") (pinfunction "2_2") (pintype "passive"))
    )
    (net (code "145") (name "Net-(U$1-LBOOS1)") (class "Default")
      (node (ref "C37") (pin "1") (pinfunction "1_1") (pintype "passive"))
      (node (ref "U$1") (pin "62") (pinfunction "LBOOS1_62") (pintype "bidirectional"))
    )
    (net (code "146") (name "Net-(U$1-LBOOS2)") (class "Default")
      (node (ref "C37") (pin "2") (pinfunction "2_2") (pintype "passive"))
      (node (ref "U$1") (pin "61") (pinfunction "LBOOS2_61") (pintype "bidirectional"))
    )
    (net (code "147") (name "Net-(U$1-LCUT1)") (class "Default")
      (node (ref "C36") (pin "1") (pinfunction "1_1") (pintype "passive"))
      (node (ref "U$1") (pin "59") (pinfunction "LCUT1_59") (pintype "bidirectional"))
    )
    (net (code "148") (name "Net-(U$1-LCUT2)") (class "Default")
      (node (ref "C36") (pin "2") (pinfunction "2_2") (pintype "passive"))
      (node (ref "U$1") (pin "58") (pinfunction "LCUT2_58") (pintype "bidirectional"))
    )
    (net (code "149") (name "Net-(U$1-LHC1)") (class "Default")
      (node (ref "C14") (pin "1") (pinfunction "1_1") (pintype "passive"))
      (node (ref "U$1") (pin "16") (pinfunction "LHC1_16") (pintype "bidirectional"))
    )
    (net (code "150") (name "Net-(U$1-LHC2)") (class "Default")
      (node (ref "C14") (pin "2") (pinfunction "2_2") (pintype "passive"))
      (node (ref "U$1") (pin "15") (pinfunction "LHC2_15") (pintype "bidirectional"))
    )
    (net (code "151") (name "Net-(U$1-LHC3)") (class "Default")
      (node (ref "C15") (pin "2") (pinfunction "2_2") (pintype "passive"))
      (node (ref "C27") (pin "2") (pinfunction "2_2") (pintype "passive"))
      (node (ref "U$1") (pin "18") (pinfunction "LHC3_18") (pintype "bidirectional"))
    )
    (net (code "152") (name "Net-(U$1-LHC4)") (class "Default")
      (node (ref "C15") (pin "1") (pinfunction "1_1") (pintype "passive"))
      (node (ref "U$1") (pin "17") (pinfunction "LHC4_17") (pintype "bidirectional"))
    )
    (net (code "153") (name "Net-(U$1-LHC5)") (class "Default")
      (node (ref "C27") (pin "1") (pinfunction "1_1") (pintype "passive"))
      (node (ref "U$1") (pin "19") (pinfunction "LHC5_19") (pintype "bidirectional"))
    )
    (net (code "154") (name "Net-(U$1-LHMC1)") (class "Default")
      (node (ref "C12") (pin "1") (pinfunction "1_1") (pintype "passive"))
      (node (ref "U$1") (pin "11") (pinfunction "LHMC1_11") (pintype "bidirectional"))
    )
    (net (code "155") (name "Net-(U$1-LHMC2)") (class "Default")
      (node (ref "C12") (pin "2") (pinfunction "2_2") (pintype "passive"))
      (node (ref "U$1") (pin "10") (pinfunction "LHMC2_10") (pintype "bidirectional"))
    )
    (net (code "156") (name "Net-(U$1-LHMC3)") (class "Default")
      (node (ref "C13") (pin "2") (pinfunction "2_2") (pintype "passive"))
      (node (ref "C26") (pin "2") (pinfunction "2_2") (pintype "passive"))
      (node (ref "U$1") (pin "13") (pinfunction "LHMC3_13") (pintype "bidirectional"))
    )
    (net (code "157") (name "Net-(U$1-LHMC4)") (class "Default")
      (node (ref "C13") (pin "1") (pinfunction "1_1") (pintype "passive"))
      (node (ref "U$1") (pin "12") (pinfunction "LHMC4_12") (pintype "bidirectional"))
    )
    (net (code "158") (name "Net-(U$1-LHMC5)") (class "Default")
      (node (ref "C26") (pin "1") (pinfunction "1_1") (pintype "passive"))
      (node (ref "U$1") (pin "14") (pinfunction "LHMC5_14") (pintype "bidirectional"))
    )
    (net (code "159") (name "Net-(U$1-LLC1)") (class "Default")
      (node (ref "C7") (pin "1") (pinfunction "1_1") (pintype "passive"))
      (node (ref "U$1") (pin "1") (pinfunction "LLC1_1") (pintype "bidirectional"))
    )
    (net (code "160") (name "Net-(U$1-LLC2)") (class "Default")
      (node (ref "C7") (pin "2") (pinfunction "2_2") (pintype "passive"))
      (node (ref "U$1") (pin "64") (pinfunction "LLC2_64") (pintype "bidirectional"))
    )
    (net (code "161") (name "Net-(U$1-LLC3)") (class "Default")
      (node (ref "C24") (pin "2") (pinfunction "2_2") (pintype "passive"))
      (node (ref "C9") (pin "2") (pinfunction "2_2") (pintype "passive"))
      (node (ref "U$1") (pin "3") (pinfunction "LLC3_3") (pintype "bidirectional"))
    )
    (net (code "162") (name "Net-(U$1-LLC4)") (class "Default")
      (node (ref "C9") (pin "1") (pinfunction "1_1") (pintype "passive"))
      (node (ref "U$1") (pin "2") (pinfunction "LLC4_2") (pintype "bidirectional"))
    )
    (net (code "163") (name "Net-(U$1-LLC5)") (class "Default")
      (node (ref "C24") (pin "1") (pinfunction "1_1") (pintype "passive"))
      (node (ref "U$1") (pin "4") (pinfunction "LLC5_4") (pintype "bidirectional"))
    )
    (net (code "164") (name "Net-(U$1-LLMC1)") (class "Default")
      (node (ref "C10") (pin "1") (pinfunction "1_1") (pintype "passive"))
      (node (ref "U$1") (pin "6") (pinfunction "LLMC1_6") (pintype "bidirectional"))
    )
    (net (code "165") (name "Net-(U$1-LLMC2)") (class "Default")
      (node (ref "C10") (pin "2") (pinfunction "2_2") (pintype "passive"))
      (node (ref "U$1") (pin "5") (pinfunction "LLMC2_5") (pintype "bidirectional"))
    )
    (net (code "166") (name "Net-(U$1-LLMC3)") (class "Default")
      (node (ref "C11") (pin "2") (pinfunction "2_2") (pintype "passive"))
      (node (ref "C25") (pin "2") (pinfunction "2_2") (pintype "passive"))
      (node (ref "U$1") (pin "8") (pinfunction "LLMC3_8") (pintype "bidirectional"))
    )
    (net (code "167") (name "Net-(U$1-LLMC4)") (class "Default")
      (node (ref "C11") (pin "1") (pinfunction "1_1") (pintype "passive"))
      (node (ref "U$1") (pin "7") (pinfunction "LLMC4_7") (pintype "bidirectional"))
    )
    (net (code "168") (name "Net-(U$1-LLMC5)") (class "Default")
      (node (ref "C25") (pin "1") (pinfunction "1_1") (pintype "passive"))
      (node (ref "U$1") (pin "9") (pinfunction "LLMC5_9") (pintype "bidirectional"))
    )
    (net (code "169") (name "Net-(U$1-LOUT)") (class "Default")
      (node (ref "C38") (pin "1") (pinfunction "1_1") (pintype "passive"))
      (node (ref "U$1") (pin "63") (pinfunction "LOUT_63") (pintype "bidirectional"))
    )
    (net (code "170") (name "Net-(U$1-RBOOS1)") (class "Default")
      (node (ref "C34") (pin "2") (pinfunction "2_2") (pintype "passive"))
      (node (ref "U$1") (pin "51") (pinfunction "RBOOS1_51") (pintype "bidirectional"))
    )
    (net (code "171") (name "Net-(U$1-RBOOS2)") (class "Default")
      (node (ref "C34") (pin "1") (pinfunction "1_1") (pintype "passive"))
      (node (ref "U$1") (pin "52") (pinfunction "RBOOS2_52") (pintype "bidirectional"))
    )
    (net (code "172") (name "Net-(U$1-RCUT1)") (class "Default")
      (node (ref "C35") (pin "2") (pinfunction "2_2") (pintype "passive"))
      (node (ref "U$1") (pin "54") (pinfunction "RCUT1_54") (pintype "bidirectional"))
    )
    (net (code "173") (name "Net-(U$1-RCUT2)") (class "Default")
      (node (ref "C35") (pin "1") (pinfunction "1_1") (pintype "passive"))
      (node (ref "U$1") (pin "55") (pinfunction "RCUT2_55") (pintype "bidirectional"))
    )
    (net (code "174") (name "Net-(U$1-RHC1)") (class "Default")
      (node (ref "C17") (pin "1") (pinfunction "1_1") (pintype "passive"))
      (node (ref "U$1") (pin "33") (pinfunction "RHC1_33") (pintype "bidirectional"))
    )
    (net (code "175") (name "Net-(U$1-RHC2)") (class "Default")
      (node (ref "C17") (pin "2") (pinfunction "2_2") (pintype "passive"))
      (node (ref "U$1") (pin "34") (pinfunction "RHC2_34") (pintype "bidirectional"))
    )
    (net (code "176") (name "Net-(U$1-RHC3)") (class "Default")
      (node (ref "C16") (pin "2") (pinfunction "2_2") (pintype "passive"))
      (node (ref "C29") (pin "2") (pinfunction "2_2") (pintype "passive"))
      (node (ref "U$1") (pin "31") (pinfunction "RHC3_31") (pintype "bidirectional"))
    )
    (net (code "177") (name "Net-(U$1-RHC4)") (class "Default")
      (node (ref "C16") (pin "1") (pinfunction "1_1") (pintype "passive"))
      (node (ref "U$1") (pin "32") (pinfunction "RHC4_32") (pintype "bidirectional"))
    )
    (net (code "178") (name "Net-(U$1-RHC5)") (class "Default")
      (node (ref "C29") (pin "1") (pinfunction "1_1") (pintype "passive"))
      (node (ref "U$1") (pin "30") (pinfunction "RHC5_30") (pintype "bidirectional"))
    )
    (net (code "179") (name "Net-(U$1-RHMC1)") (class "Default")
      (node (ref "C19") (pin "1") (pinfunction "1_1") (pintype "passive"))
      (node (ref "U$1") (pin "38") (pinfunction "RHMC1_38") (pintype "bidirectional"))
    )
    (net (code "180") (name "Net-(U$1-RHMC2)") (class "Default")
      (node (ref "C19") (pin "2") (pinfunction "2_2") (pintype "passive"))
      (node (ref "U$1") (pin "39") (pinfunction "RHMC2_39") (pintype "bidirectional"))
    )
    (net (code "181") (name "Net-(U$1-RHMC3)") (class "Default")
      (node (ref "C18") (pin "2") (pinfunction "2_2") (pintype "passive"))
      (node (ref "C30") (pin "2") (pinfunction "2_2") (pintype "passive"))
      (node (ref "U$1") (pin "36") (pinfunction "RHMC3_36") (pintype "bidirectional"))
    )
    (net (code "182") (name "Net-(U$1-RHMC4)") (class "Default")
      (node (ref "C18") (pin "1") (pinfunction "1_1") (pintype "passive"))
      (node (ref "U$1") (pin "37") (pinfunction "RHMC4_37") (pintype "bidirectional"))
    )
    (net (code "183") (name "Net-(U$1-RHMC5)") (class "Default")
      (node (ref "C30") (pin "1") (pinfunction "1_1") (pintype "passive"))
      (node (ref "U$1") (pin "35") (pinfunction "RHMC5_35") (pintype "bidirectional"))
    )
    (net (code "184") (name "Net-(U$1-RLC1)") (class "Default")
      (node (ref "C23") (pin "1") (pinfunction "1_1") (pintype "passive"))
      (node (ref "U$1") (pin "48") (pinfunction "RLC1_48") (pintype "bidirectional"))
    )
    (net (code "185") (name "Net-(U$1-RLC2)") (class "Default")
      (node (ref "C23") (pin "2") (pinfunction "2_2") (pintype "passive"))
      (node (ref "U$1") (pin "49") (pinfunction "RLC2_49") (pintype "bidirectional"))
    )
    (net (code "186") (name "Net-(U$1-RLC3)") (class "Default")
      (node (ref "C22") (pin "2") (pinfunction "2_2") (pintype "passive"))
      (node (ref "C32") (pin "2") (pinfunction "2_2") (pintype "passive"))
      (node (ref "U$1") (pin "46") (pinfunction "RLC3_46") (pintype "bidirectional"))
    )
    (net (code "187") (name "Net-(U$1-RLC4)") (class "Default")
      (node (ref "C22") (pin "1") (pinfunction "1_1") (pintype "passive"))
      (node (ref "U$1") (pin "47") (pinfunction "RLC4_47") (pintype "bidirectional"))
    )
    (net (code "188") (name "Net-(U$1-RLC5)") (class "Default")
      (node (ref "C32") (pin "1") (pinfunction "1_1") (pintype "passive"))
      (node (ref "U$1") (pin "45") (pinfunction "RLC5_45") (pintype "bidirectional"))
    )
    (net (code "189") (name "Net-(U$1-RLMC1)") (class "Default")
      (node (ref "C21") (pin "1") (pinfunction "1_1") (pintype "passive"))
      (node (ref "U$1") (pin "43") (pinfunction "RLMC1_43") (pintype "bidirectional"))
    )
    (net (code "190") (name "Net-(U$1-RLMC2)") (class "Default")
      (node (ref "C21") (pin "2") (pinfunction "2_2") (pintype "passive"))
      (node (ref "U$1") (pin "44") (pinfunction "RLMC2_44") (pintype "bidirectional"))
    )
    (net (code "191") (name "Net-(U$1-RLMC3)") (class "Default")
      (node (ref "C20") (pin "2") (pinfunction "2_2") (pintype "passive"))
      (node (ref "C31") (pin "2") (pinfunction "2_2") (pintype "passive"))
      (node (ref "U$1") (pin "41") (pinfunction "RLMC3_41") (pintype "bidirectional"))
    )
    (net (code "192") (name "Net-(U$1-RLMC4)") (class "Default")
      (node (ref "C20") (pin "1") (pinfunction "1_1") (pintype "passive"))
      (node (ref "U$1") (pin "42") (pinfunction "RLMC4_42") (pintype "bidirectional"))
    )
    (net (code "193") (name "Net-(U$1-RLMC5)") (class "Default")
      (node (ref "C31") (pin "1") (pinfunction "1_1") (pintype "passive"))
      (node (ref "U$1") (pin "40") (pinfunction "RLMC5_40") (pintype "bidirectional"))
    )
    (net (code "194") (name "Net-(U$1-ROUT)") (class "Default")
      (node (ref "C33") (pin "1") (pinfunction "1_1") (pintype "passive"))
      (node (ref "U$1") (pin "50") (pinfunction "ROUT_50") (pintype "bidirectional"))
    )
    (net (code "195") (name "Net-(U$1-V_REF)") (class "Default")
      (node (ref "C28") (pin "1") (pinfunction "1_1") (pintype "passive"))
      (node (ref "C39") (pin "1") (pinfunction "1_1") (pintype "passive"))
      (node (ref "U$1") (pin "23") (pinfunction "V_REF_23") (pintype "bidirectional"))
    )
    (net (code "196") (name "Net-(U$3-LBOOS1)") (class "Default")
      (node (ref "C132") (pin "1") (pinfunction "1_1") (pintype "passive"))
      (node (ref "U$3") (pin "62") (pinfunction "LBOOS1_62") (pintype "bidirectional"))
    )
    (net (code "197") (name "Net-(U$3-LBOOS2)") (class "Default")
      (node (ref "C132") (pin "2") (pinfunction "2_2") (pintype "passive"))
      (node (ref "U$3") (pin "61") (pinfunction "LBOOS2_61") (pintype "bidirectional"))
    )
    (net (code "198") (name "Net-(U$3-LCUT1)") (class "Default")
      (node (ref "C131") (pin "1") (pinfunction "1_1") (pintype "passive"))
      (node (ref "U$3") (pin "59") (pinfunction "LCUT1_59") (pintype "bidirectional"))
    )
    (net (code "199") (name "Net-(U$3-LCUT2)") (class "Default")
      (node (ref "C131") (pin "2") (pinfunction "2_2") (pintype "passive"))
      (node (ref "U$3") (pin "58") (pinfunction "LCUT2_58") (pintype "bidirectional"))
    )
    (net (code "200") (name "Net-(U$3-LHC1)") (class "Default")
      (node (ref "C109") (pin "1") (pinfunction "1_1") (pintype "passive"))
      (node (ref "U$3") (pin "16") (pinfunction "LHC1_16") (pintype "bidirectional"))
    )
    (net (code "201") (name "Net-(U$3-LHC2)") (class "Default")
      (node (ref "C109") (pin "2") (pinfunction "2_2") (pintype "passive"))
      (node (ref "U$3") (pin "15") (pinfunction "LHC2_15") (pintype "bidirectional"))
    )
    (net (code "202") (name "Net-(U$3-LHC3)") (class "Default")
      (node (ref "C110") (pin "2") (pinfunction "2_2") (pintype "passive"))
      (node (ref "C122") (pin "2") (pinfunction "2_2") (pintype "passive"))
      (node (ref "U$3") (pin "18") (pinfunction "LHC3_18") (pintype "bidirectional"))
    )
    (net (code "203") (name "Net-(U$3-LHC4)") (class "Default")
      (node (ref "C110") (pin "1") (pinfunction "1_1") (pintype "passive"))
      (node (ref "U$3") (pin "17") (pinfunction "LHC4_17") (pintype "bidirectional"))
    )
    (net (code "204") (name "Net-(U$3-LHC5)") (class "Default")
      (node (ref "C122") (pin "1") (pinfunction "1_1") (pintype "passive"))
      (node (ref "U$3") (pin "19") (pinfunction "LHC5_19") (pintype "bidirectional"))
    )
    (net (code "205") (name "Net-(U$3-LHMC1)") (class "Default")
      (node (ref "C107") (pin "1") (pinfunction "1_1") (pintype "passive"))
      (node (ref "U$3") (pin "11") (pinfunction "LHMC1_11") (pintype "bidirectional"))
    )
    (net (code "206") (name "Net-(U$3-LHMC2)") (class "Default")
      (node (ref "C107") (pin "2") (pinfunction "2_2") (pintype "passive"))
      (node (ref "U$3") (pin "10") (pinfunction "LHMC2_10") (pintype "bidirectional"))
    )
    (net (code "207") (name "Net-(U$3-LHMC3)") (class "Default")
      (node (ref "C108") (pin "2") (pinfunction "2_2") (pintype "passive"))
      (node (ref "C121") (pin "2") (pinfunction "2_2") (pintype "passive"))
      (node (ref "U$3") (pin "13") (pinfunction "LHMC3_13") (pintype "bidirectional"))
    )
    (net (code "208") (name "Net-(U$3-LHMC4)") (class "Default")
      (node (ref "C108") (pin "1") (pinfunction "1_1") (pintype "passive"))
      (node (ref "U$3") (pin "12") (pinfunction "LHMC4_12") (pintype "bidirectional"))
    )
    (net (code "209") (name "Net-(U$3-LHMC5)") (class "Default")
      (node (ref "C121") (pin "1") (pinfunction "1_1") (pintype "passive"))
      (node (ref "U$3") (pin "14") (pinfunction "LHMC5_14") (pintype "bidirectional"))
    )
    (net (code "210") (name "Net-(U$3-LLC1)") (class "Default")
      (node (ref "C103") (pin "1") (pinfunction "1_1") (pintype "passive"))
      (node (ref "U$3") (pin "1") (pinfunction "LLC1_1") (pintype "bidirectional"))
    )
    (net (code "211") (name "Net-(U$3-LLC2)") (class "Default")
      (node (ref "C103") (pin "2") (pinfunction "2_2") (pintype "passive"))
      (node (ref "U$3") (pin "64") (pinfunction "LLC2_64") (pintype "bidirectional"))
    )
    (net (code "212") (name "Net-(U$3-LLC3)") (class "Default")
      (node (ref "C104") (pin "2") (pinfunction "2_2") (pintype "passive"))
      (node (ref "C119") (pin "2") (pinfunction "2_2") (pintype "passive"))
      (node (ref "U$3") (pin "3") (pinfunction "LLC3_3") (pintype "bidirectional"))
    )
    (net (code "213") (name "Net-(U$3-LLC4)") (class "Default")
      (node (ref "C104") (pin "1") (pinfunction "1_1") (pintype "passive"))
      (node (ref "U$3") (pin "2") (pinfunction "LLC4_2") (pintype "bidirectional"))
    )
    (net (code "214") (name "Net-(U$3-LLC5)") (class "Default")
      (node (ref "C119") (pin "1") (pinfunction "1_1") (pintype "passive"))
      (node (ref "U$3") (pin "4") (pinfunction "LLC5_4") (pintype "bidirectional"))
    )
    (net (code "215") (name "Net-(U$3-LLMC1)") (class "Default")
      (node (ref "C105") (pin "1") (pinfunction "1_1") (pintype "passive"))
      (node (ref "U$3") (pin "6") (pinfunction "LLMC1_6") (pintype "bidirectional"))
    )
    (net (code "216") (name "Net-(U$3-LLMC2)") (class "Default")
      (node (ref "C105") (pin "2") (pinfunction "2_2") (pintype "passive"))
      (node (ref "U$3") (pin "5") (pinfunction "LLMC2_5") (pintype "bidirectional"))
    )
    (net (code "217") (name "Net-(U$3-LLMC3)") (class "Default")
      (node (ref "C106") (pin "2") (pinfunction "2_2") (pintype "passive"))
      (node (ref "C120") (pin "2") (pinfunction "2_2") (pintype "passive"))
      (node (ref "U$3") (pin "8") (pinfunction "LLMC3_8") (pintype "bidirectional"))
    )
    (net (code "218") (name "Net-(U$3-LLMC4)") (class "Default")
      (node (ref "C106") (pin "1") (pinfunction "1_1") (pintype "passive"))
      (node (ref "U$3") (pin "7") (pinfunction "LLMC4_7") (pintype "bidirectional"))
    )
    (net (code "219") (name "Net-(U$3-LLMC5)") (class "Default")
      (node (ref "C120") (pin "1") (pinfunction "1_1") (pintype "passive"))
      (node (ref "U$3") (pin "9") (pinfunction "LLMC5_9") (pintype "bidirectional"))
    )
    (net (code "220") (name "Net-(U$3-LOUT)") (class "Default")
      (node (ref "C133") (pin "1") (pinfunction "1_1") (pintype "passive"))
      (node (ref "U$3") (pin "63") (pinfunction "LOUT_63") (pintype "bidirectional"))
    )
    (net (code "221") (name "Net-(U$3-RBOOS1)") (class "Default")
      (node (ref "C129") (pin "2") (pinfunction "2_2") (pintype "passive"))
      (node (ref "U$3") (pin "51") (pinfunction "RBOOS1_51") (pintype "bidirectional"))
    )
    (net (code "222") (name "Net-(U$3-RBOOS2)") (class "Default")
      (node (ref "C129") (pin "1") (pinfunction "1_1") (pintype "passive"))
      (node (ref "U$3") (pin "52") (pinfunction "RBOOS2_52") (pintype "bidirectional"))
    )
    (net (code "223") (name "Net-(U$3-RCUT1)") (class "Default")
      (node (ref "C130") (pin "2") (pinfunction "2_2") (pintype "passive"))
      (node (ref "U$3") (pin "54") (pinfunction "RCUT1_54") (pintype "bidirectional"))
    )
    (net (code "224") (name "Net-(U$3-RCUT2)") (class "Default")
      (node (ref "C130") (pin "1") (pinfunction "1_1") (pintype "passive"))
      (node (ref "U$3") (pin "55") (pinfunction "RCUT2_55") (pintype "bidirectional"))
    )
    (net (code "225") (name "Net-(U$3-RHC1)") (class "Default")
      (node (ref "C112") (pin "1") (pinfunction "1_1") (pintype "passive"))
      (node (ref "U$3") (pin "33") (pinfunction "RHC1_33") (pintype "bidirectional"))
    )
    (net (code "226") (name "Net-(U$3-RHC2)") (class "Default")
      (node (ref "C112") (pin "2") (pinfunction "2_2") (pintype "passive"))
      (node (ref "U$3") (pin "34") (pinfunction "RHC2_34") (pintype "bidirectional"))
    )
    (net (code "227") (name "Net-(U$3-RHC3)") (class "Default")
      (node (ref "C111") (pin "2") (pinfunction "2_2") (pintype "passive"))
      (node (ref "C124") (pin "2") (pinfunction "2_2") (pintype "passive"))
      (node (ref "U$3") (pin "31") (pinfunction "RHC3_31") (pintype "bidirectional"))
    )
    (net (code "228") (name "Net-(U$3-RHC4)") (class "Default")
      (node (ref "C111") (pin "1") (pinfunction "1_1") (pintype "passive"))
      (node (ref "U$3") (pin "32") (pinfunction "RHC4_32") (pintype "bidirectional"))
    )
    (net (code "229") (name "Net-(U$3-RHC5)") (class "Default")
      (node (ref "C124") (pin "1") (pinfunction "1_1") (pintype "passive"))
      (node (ref "U$3") (pin "30") (pinfunction "RHC5_30") (pintype "bidirectional"))
    )
    (net (code "230") (name "Net-(U$3-RHMC1)") (class "Default")
      (node (ref "C114") (pin "1") (pinfunction "1_1") (pintype "passive"))
      (node (ref "U$3") (pin "38") (pinfunction "RHMC1_38") (pintype "bidirectional"))
    )
    (net (code "231") (name "Net-(U$3-RHMC2)") (class "Default")
      (node (ref "C114") (pin "2") (pinfunction "2_2") (pintype "passive"))
      (node (ref "U$3") (pin "39") (pinfunction "RHMC2_39") (pintype "bidirectional"))
    )
    (net (code "232") (name "Net-(U$3-RHMC3)") (class "Default")
      (node (ref "C113") (pin "2") (pinfunction "2_2") (pintype "passive"))
      (node (ref "C125") (pin "2") (pinfunction "2_2") (pintype "passive"))
      (node (ref "U$3") (pin "36") (pinfunction "RHMC3_36") (pintype "bidirectional"))
    )
    (net (code "233") (name "Net-(U$3-RHMC4)") (class "Default")
      (node (ref "C113") (pin "1") (pinfunction "1_1") (pintype "passive"))
      (node (ref "U$3") (pin "37") (pinfunction "RHMC4_37") (pintype "bidirectional"))
    )
    (net (code "234") (name "Net-(U$3-RHMC5)") (class "Default")
      (node (ref "C125") (pin "1") (pinfunction "1_1") (pintype "passive"))
      (node (ref "U$3") (pin "35") (pinfunction "RHMC5_35") (pintype "bidirectional"))
    )
    (net (code "235") (name "Net-(U$3-RLC1)") (class "Default")
      (node (ref "C118") (pin "1") (pinfunction "1_1") (pintype "passive"))
      (node (ref "U$3") (pin "48") (pinfunction "RLC1_48") (pintype "bidirectional"))
    )
    (net (code "236") (name "Net-(U$3-RLC2)") (class "Default")
      (node (ref "C118") (pin "2") (pinfunction "2_2") (pintype "passive"))
      (node (ref "U$3") (pin "49") (pinfunction "RLC2_49") (pintype "bidirectional"))
    )
    (net (code "237") (name "Net-(U$3-RLC3)") (class "Default")
      (node (ref "C117") (pin "2") (pinfunction "2_2") (pintype "passive"))
      (node (ref "C127") (pin "2") (pinfunction "2_2") (pintype "passive"))
      (node (ref "U$3") (pin "46") (pinfunction "RLC3_46") (pintype "bidirectional"))
    )
    (net (code "238") (name "Net-(U$3-RLC4)") (class "Default")
      (node (ref "C117") (pin "1") (pinfunction "1_1") (pintype "passive"))
      (node (ref "U$3") (pin "47") (pinfunction "RLC4_47") (pintype "bidirectional"))
    )
    (net (code "239") (name "Net-(U$3-RLC5)") (class "Default")
      (node (ref "C127") (pin "1") (pinfunction "1_1") (pintype "passive"))
      (node (ref "U$3") (pin "45") (pinfunction "RLC5_45") (pintype "bidirectional"))
    )
    (net (code "240") (name "Net-(U$3-RLMC1)") (class "Default")
      (node (ref "C116") (pin "1") (pinfunction "1_1") (pintype "passive"))
      (node (ref "U$3") (pin "43") (pinfunction "RLMC1_43") (pintype "bidirectional"))
    )
    (net (code "241") (name "Net-(U$3-RLMC2)") (class "Default")
      (node (ref "C116") (pin "2") (pinfunction "2_2") (pintype "passive"))
      (node (ref "U$3") (pin "44") (pinfunction "RLMC2_44") (pintype "bidirectional"))
    )
    (net (code "242") (name "Net-(U$3-RLMC3)") (class "Default")
      (node (ref "C115") (pin "2") (pinfunction "2_2") (pintype "passive"))
      (node (ref "C126") (pin "2") (pinfunction "2_2") (pintype "passive"))
      (node (ref "U$3") (pin "41") (pinfunction "RLMC3_41") (pintype "bidirectional"))
    )
    (net (code "243") (name "Net-(U$3-RLMC4)") (class "Default")
      (node (ref "C115") (pin "1") (pinfunction "1_1") (pintype "passive"))
      (node (ref "U$3") (pin "42") (pinfunction "RLMC4_42") (pintype "bidirectional"))
    )
    (net (code "244") (name "Net-(U$3-RLMC5)") (class "Default")
      (node (ref "C126") (pin "1") (pinfunction "1_1") (pintype "passive"))
      (node (ref "U$3") (pin "40") (pinfunction "RLMC5_40") (pintype "bidirectional"))
    )
    (net (code "245") (name "Net-(U$3-ROUT)") (class "Default")
      (node (ref "C128") (pin "1") (pinfunction "1_1") (pintype "passive"))
      (node (ref "U$3") (pin "50") (pinfunction "ROUT_50") (pintype "bidirectional"))
    )
    (net (code "246") (name "Net-(U$3-V_REF)") (class "Default")
      (node (ref "C123") (pin "1") (pinfunction "1_1") (pintype "passive"))
      (node (ref "C134") (pin "1") (pinfunction "1_1") (pintype "passive"))
      (node (ref "U$3") (pin "23") (pinfunction "V_REF_23") (pintype "bidirectional"))
    )
    (net (code "247") (name "Net-(U2-POS_A)") (class "Default")
      (node (ref "R22") (pin "2") (pinfunction "2_2") (pintype "passive"))
      (node (ref "R9") (pin "2") (pinfunction "2_2") (pintype "passive"))
      (node (ref "U2") (pin "3") (pinfunction "POS_A_3") (pintype "input"))
    )
    (net (code "248") (name "Net-(U2-POS_B)") (class "Default")
      (node (ref "R5") (pin "2") (pinfunction "2_2") (pintype "passive"))
      (node (ref "R8") (pin "2") (pinfunction "2_2") (pintype "passive"))
      (node (ref "U2") (pin "5") (pinfunction "POS_B_5") (pintype "input"))
    )
    (net (code "249") (name "OUT1_EQ1") (class "Default")
      (node (ref "C33") (pin "2") (pinfunction "2_2") (pintype "passive"))
      (node (ref "C6") (pin "1") (pinfunction "1_1") (pintype "passive"))
      (node (ref "PAD16") (pin "1") (pinfunction "P_1") (pintype "passive"))
    )
    (net (code "250") (name "OUT1_EQ2") (class "Default")
      (node (ref "C128") (pin "2") (pinfunction "2_2") (pintype "passive"))
      (node (ref "C5") (pin "1") (pinfunction "1_1") (pintype "passive"))
      (node (ref "PAD14") (pin "1") (pinfunction "P_1") (pintype "passive"))
    )
    (net (code "251") (name "OUT2_EQ1") (class "Default")
      (node (ref "C38") (pin "2") (pinfunction "2_2") (pintype "passive"))
      (node (ref "C8") (pin "1") (pinfunction "1_1") (pintype "passive"))
      (node (ref "PAD15") (pin "1") (pinfunction "P_1") (pintype "passive"))
    )
    (net (code "252") (name "OUT2_EQ2") (class "Default")
      (node (ref "C133") (pin "2") (pinfunction "2_2") (pintype "passive"))
      (node (ref "C2") (pin "1") (pinfunction "1_1") (pintype "passive"))
      (node (ref "PAD13") (pin "1") (pinfunction "P_1") (pintype "passive"))
    )
    (net (code "253") (name "OUTL_PAN1") (class "Default")
      (node (ref "C79") (pin "1") (pinfunction "1_1") (pintype "passive"))
      (node (ref "OPAMP1_PAN1") (pin "1") (pinfunction "OUT_A_1") (pintype "output"))
      (node (ref "PAD3") (pin "1") (pinfunction "P_1") (pintype "passive"))
      (node (ref "R55") (pin "1") (pinfunction "1_1") (pintype "passive"))
      (node (ref "R74") (pin "2") (pinfunction "2_2") (pintype "passive"))
    )
    (net (code "254") (name "OUTL_PAN2") (class "Default")
      (node (ref "C80") (pin "1") (pinfunction "1_1") (pintype "passive"))
      (node (ref "OPAMP1_PAN3") (pin "1") (pinfunction "OUT_A_1") (pintype "output"))
      (node (ref "PAD5") (pin "1") (pinfunction "P_1") (pintype "passive"))
      (node (ref "R31") (pin "1") (pinfunction "1_1") (pintype "passive"))
      (node (ref "R88") (pin "2") (pinfunction "2_2") (pintype "passive"))
    )
    (net (code "255") (name "OUTL_PAN3") (class "Default")
      (node (ref "C78") (pin "1") (pinfunction "1_1") (pintype "passive"))
      (node (ref "OPAMP1_PAN2") (pin "1") (pinfunction "OUT_A_1") (pintype "output"))
      (node (ref "PAD1") (pin "1") (pinfunction "P_1") (pintype "passive"))
      (node (ref "R14") (pin "2") (pinfunction "2_2") (pintype "passive"))
      (node (ref "R46") (pin "1") (pinfunction "1_1") (pintype "passive"))
    )
    (net (code "256") (name "OUTL_PAN4") (class "Default")
      (node (ref "C84") (pin "1") (pinfunction "1_1") (pintype "passive"))
      (node (ref "OPAMP1_PAN4") (pin "1") (pinfunction "OUT_A_1") (pintype "output"))
      (node (ref "PAD7") (pin "1") (pinfunction "P_1") (pintype "passive"))
      (node (ref "R21") (pin "2") (pinfunction "2_2") (pintype "passive"))
      (node (ref "R40") (pin "1") (pinfunction "1_1") (pintype "passive"))
    )
    (net (code "257") (name "OUTR_PAN1") (class "Default")
      (node (ref "C82") (pin "1") (pinfunction "1_1") (pintype "passive"))
      (node (ref "OPAMP1_PAN1") (pin "7") (pinfunction "OUT_B_7") (pintype "output"))
      (node (ref "PAD6") (pin "1") (pinfunction "P_1") (pintype "passive"))
      (node (ref "R33") (pin "1") (pinfunction "1_1") (pintype "passive"))
      (node (ref "R72") (pin "1") (pinfunction "1_1") (pintype "passive"))
    )
    (net (code "258") (name "OUTR_PAN2") (class "Default")
      (node (ref "C83") (pin "1") (pinfunction "1_1") (pintype "passive"))
      (node (ref "OPAMP1_PAN3") (pin "7") (pinfunction "OUT_B_7") (pintype "output"))
      (node (ref "PAD4") (pin "1") (pinfunction "P_1") (pintype "passive"))
      (node (ref "R54") (pin "1") (pinfunction "1_1") (pintype "passive"))
      (node (ref "R86") (pin "1") (pinfunction "1_1") (pintype "passive"))
    )
    (net (code "259") (name "OUTR_PAN3") (class "Default")
      (node (ref "C81") (pin "1") (pinfunction "1_1") (pintype "passive"))
      (node (ref "OPAMP1_PAN2") (pin "7") (pinfunction "OUT_B_7") (pintype "output"))
      (node (ref "PAD8") (pin "1") (pinfunction "P_1") (pintype "passive"))
      (node (ref "R12") (pin "1") (pinfunction "1_1") (pintype "passive"))
      (node (ref "R39") (pin "1") (pinfunction "1_1") (pintype "passive"))
    )
    (net (code "260") (name "OUTR_PAN4") (class "Default")
      (node (ref "C77") (pin "1") (pinfunction "1_1") (pintype "passive"))
      (node (ref "OPAMP1_PAN4") (pin "7") (pinfunction "OUT_B_7") (pintype "output"))
      (node (ref "PAD2") (pin "1") (pinfunction "P_1") (pintype "passive"))
      (node (ref "R19") (pin "1") (pinfunction "1_1") (pintype "passive"))
      (node (ref "R48") (pin "1") (pinfunction "1_1") (pintype "passive"))
    )
    (net (code "261") (name "OUT_A1_COMP1") (class "Default")
      (node (ref "OPAMP1_COMP1") (pin "1") (pinfunction "OUT_A_1") (pintype "output"))
      (node (ref "R65") (pin "2") (pinfunction "2_2") (pintype "passive"))
    )
    (net (code "262") (name "OUT_A1_COMP2") (class "Default")
      (node (ref "OPAMP1_COMP3") (pin "1") (pinfunction "OUT_A_1") (pintype "output"))
      (node (ref "R115") (pin "2") (pinfunction "2_2") (pintype "passive"))
    )
    (net (code "263") (name "OUT_A1_COMP3") (class "Default")
      (node (ref "OPAMP1_COMP2") (pin "1") (pinfunction "OUT_A_1") (pintype "output"))
      (node (ref "R97") (pin "2") (pinfunction "2_2") (pintype "passive"))
    )
    (net (code "264") (name "OUT_A1_COMP4") (class "Default")
      (node (ref "OPAMP1_COMP5") (pin "1") (pinfunction "OUT_A_1") (pintype "output"))
      (node (ref "R151") (pin "2") (pinfunction "2_2") (pintype "passive"))
    )
    (net (code "265") (name "OUT_A2_COMP1") (class "Default")
      (node (ref "100POT1_COMP1") (pin "10") (pinfunction "PB0_10") (pintype "passive"))
      (node (ref "OPAMP2_COMP1") (pin "1") (pinfunction "OUT_A_1") (pintype "output"))
      (node (ref "R75") (pin "2") (pinfunction "2_2") (pintype "passive"))
    )
    (net (code "266") (name "OUT_A2_COMP2") (class "Default")
      (node (ref "100POT1_COMP3") (pin "10") (pinfunction "PB0_10") (pintype "passive"))
      (node (ref "OPAMP2_COMP3") (pin "1") (pinfunction "OUT_A_1") (pintype "output"))
      (node (ref "R118") (pin "2") (pinfunction "2_2") (pintype "passive"))
    )
    (net (code "267") (name "OUT_A2_COMP3") (class "Default")
      (node (ref "100POT1_COMP2") (pin "10") (pinfunction "PB0_10") (pintype "passive"))
      (node (ref "OPAMP2_COMP2") (pin "1") (pinfunction "OUT_A_1") (pintype "output"))
      (node (ref "R100") (pin "2") (pinfunction "2_2") (pintype "passive"))
    )
    (net (code "268") (name "OUT_A2_COMP4") (class "Default")
      (node (ref "100POT1_COMP5") (pin "10") (pinfunction "PB0_10") (pintype "passive"))
      (node (ref "OPAMP2_COMP5") (pin "1") (pinfunction "OUT_A_1") (pintype "output"))
      (node (ref "R154") (pin "2") (pinfunction "2_2") (pintype "passive"))
    )
    (net (code "269") (name "OUT_A3_COMP1") (class "Default")
      (node (ref "D26") (pin "2") (pinfunction "2_2") (pintype "passive"))
      (node (ref "OPAMP3_COMP1") (pin "1") (pinfunction "OUT_A_1") (pintype "output"))
    )
    (net (code "270") (name "OUT_A3_COMP2") (class "Default")
      (node (ref "D48") (pin "2") (pinfunction "2_2") (pintype "passive"))
      (node (ref "OPAMP3_COMP3") (pin "1") (pinfunction "OUT_A_1") (pintype "output"))
    )
    (net (code "271") (name "OUT_A3_COMP3") (class "Default")
      (node (ref "D37") (pin "2") (pinfunction "2_2") (pintype "passive"))
      (node (ref "OPAMP3_COMP2") (pin "1") (pinfunction "OUT_A_1") (pintype "output"))
    )
    (net (code "272") (name "OUT_A3_COMP4") (class "Default")
      (node (ref "D70") (pin "2") (pinfunction "2_2") (pintype "passive"))
      (node (ref "OPAMP3_COMP5") (pin "1") (pinfunction "OUT_A_1") (pintype "output"))
    )
    (net (code "273") (name "OUT_A4_COMP1") (class "Default")
      (node (ref "OPAMP4_COMP1") (pin "1") (pinfunction "OUT_A_1") (pintype "output"))
      (node (ref "OPAMP4_COMP1") (pin "5") (pinfunction "POS_B_5") (pintype "input"))
      (node (ref "R78") (pin "1") (pinfunction "1_1") (pintype "passive"))
      (node (ref "R79") (pin "1") (pinfunction "1_1") (pintype "passive"))
    )
    (net (code "274") (name "OUT_A4_COMP2") (class "Default")
      (node (ref "OPAMP4_COMP3") (pin "1") (pinfunction "OUT_A_1") (pintype "output"))
      (node (ref "OPAMP4_COMP3") (pin "5") (pinfunction "POS_B_5") (pintype "input"))
      (node (ref "R121") (pin "1") (pinfunction "1_1") (pintype "passive"))
      (node (ref "R122") (pin "1") (pinfunction "1_1") (pintype "passive"))
    )
    (net (code "275") (name "OUT_A4_COMP3") (class "Default")
      (node (ref "OPAMP4_COMP2") (pin "1") (pinfunction "OUT_A_1") (pintype "output"))
      (node (ref "OPAMP4_COMP2") (pin "5") (pinfunction "POS_B_5") (pintype "input"))
      (node (ref "R103") (pin "1") (pinfunction "1_1") (pintype "passive"))
      (node (ref "R104") (pin "1") (pinfunction "1_1") (pintype "passive"))
    )
    (net (code "276") (name "OUT_A4_COMP4") (class "Default")
      (node (ref "OPAMP4_COMP5") (pin "1") (pinfunction "OUT_A_1") (pintype "output"))
      (node (ref "OPAMP4_COMP5") (pin "5") (pinfunction "POS_B_5") (pintype "input"))
      (node (ref "R157") (pin "1") (pinfunction "1_1") (pintype "passive"))
      (node (ref "R158") (pin "1") (pinfunction "1_1") (pintype "passive"))
    )
    (net (code "277") (name "OUT_A_MIX") (class "Default")
      (node (ref "OPAMP1_MIX1") (pin "1") (pinfunction "OUT_A_1") (pintype "output"))
      (node (ref "R44") (pin "2") (pinfunction "2_2") (pintype "passive"))
      (node (ref "R45") (pin "1") (pinfunction "1_1") (pintype "passive"))
    )
    (net (code "278") (name "OUT_B1_COMP1") (class "Default")
      (node (ref "D19") (pin "2") (pinfunction "2_2") (pintype "passive"))
      (node (ref "OPAMP1_COMP1") (pin "7") (pinfunction "OUT_B_7") (pintype "output"))
    )
    (net (code "279") (name "OUT_B1_COMP2") (class "Default")
      (node (ref "D41") (pin "2") (pinfunction "2_2") (pintype "passive"))
      (node (ref "OPAMP1_COMP3") (pin "7") (pinfunction "OUT_B_7") (pintype "output"))
    )
    (net (code "280") (name "OUT_B1_COMP3") (class "Default")
      (node (ref "D30") (pin "2") (pinfunction "2_2") (pintype "passive"))
      (node (ref "OPAMP1_COMP2") (pin "7") (pinfunction "OUT_B_7") (pintype "output"))
    )
    (net (code "281") (name "OUT_B1_COMP4") (class "Default")
      (node (ref "D63") (pin "2") (pinfunction "2_2") (pintype "passive"))
      (node (ref "OPAMP1_COMP5") (pin "7") (pinfunction "OUT_B_7") (pintype "output"))
    )
    (net (code "282") (name "OUT_B3_COMP1") (class "Default")
      (node (ref "D20") (pin "1") (pinfunction "1_1") (pintype "passive"))
      (node (ref "OPAMP3_COMP1") (pin "7") (pinfunction "OUT_B_7") (pintype "output"))
      (node (ref "R90") (pin "1") (pinfunction "1_1") (pintype "passive"))
    )
    (net (code "283") (name "OUT_B3_COMP2") (class "Default")
      (node (ref "D42") (pin "1") (pinfunction "1_1") (pintype "passive"))
      (node (ref "OPAMP3_COMP3") (pin "7") (pinfunction "OUT_B_7") (pintype "output"))
      (node (ref "R126") (pin "1") (pinfunction "1_1") (pintype "passive"))
    )
    (net (code "284") (name "OUT_B3_COMP3") (class "Default")
      (node (ref "D31") (pin "1") (pinfunction "1_1") (pintype "passive"))
      (node (ref "OPAMP3_COMP2") (pin "7") (pinfunction "OUT_B_7") (pintype "output"))
      (node (ref "R108") (pin "1") (pinfunction "1_1") (pintype "passive"))
    )
    (net (code "285") (name "OUT_B3_COMP4") (class "Default")
      (node (ref "D64") (pin "1") (pinfunction "1_1") (pintype "passive"))
      (node (ref "OPAMP3_COMP5") (pin "7") (pinfunction "OUT_B_7") (pintype "output"))
      (node (ref "R162") (pin "1") (pinfunction "1_1") (pintype "passive"))
    )
    (net (code "286") (name "OUT_B_MIX") (class "Default")
      (node (ref "OPAMP1_MIX1") (pin "7") (pinfunction "OUT_B_7") (pintype "output"))
      (node (ref "R59") (pin "2") (pinfunction "2_2") (pintype "passive"))
      (node (ref "R60") (pin "1") (pinfunction "1_1") (pintype "passive"))
    )
    (net (code "287") (name "OUT_COMP1") (class "Default")
      (node (ref "100POT1_COMP1") (pin "6") (pinfunction "PW1_6") (pintype "passive"))
      (node (ref "100POT1_COMP1") (pin "7") (pinfunction "PA1_7") (pintype "passive"))
      (node (ref "OPAMP4_COMP1") (pin "7") (pinfunction "OUT_B_7") (pintype "output"))
      (node (ref "PAD10") (pin "1") (pinfunction "P_1") (pintype "passive"))
      (node (ref "U$1") (pin "60") (pinfunction "LIN_60") (pintype "bidirectional"))
    )
    (net (code "288") (name "OUT_COMP2") (class "Default")
      (node (ref "100POT1_COMP3") (pin "6") (pinfunction "PW1_6") (pintype "passive"))
      (node (ref "100POT1_COMP3") (pin "7") (pinfunction "PA1_7") (pintype "passive"))
      (node (ref "OPAMP4_COMP3") (pin "7") (pinfunction "OUT_B_7") (pintype "output"))
      (node (ref "PAD9") (pin "1") (pinfunction "P_1") (pintype "passive"))
      (node (ref "U$1") (pin "53") (pinfunction "RIN_53") (pintype "bidirectional"))
    )
    (net (code "289") (name "OUT_COMP3") (class "Default")
      (node (ref "100POT1_COMP2") (pin "6") (pinfunction "PW1_6") (pintype "passive"))
      (node (ref "100POT1_COMP2") (pin "7") (pinfunction "PA1_7") (pintype "passive"))
      (node (ref "OPAMP4_COMP2") (pin "7") (pinfunction "OUT_B_7") (pintype "output"))
      (node (ref "PAD12") (pin "1") (pinfunction "P_1") (pintype "passive"))
      (node (ref "U$3") (pin "60") (pinfunction "LIN_60") (pintype "bidirectional"))
    )
    (net (code "290") (name "OUT_COMP4") (class "Default")
      (node (ref "100POT1_COMP5") (pin "6") (pinfunction "PW1_6") (pintype "passive"))
      (node (ref "100POT1_COMP5") (pin "7") (pinfunction "PA1_7") (pintype "passive"))
      (node (ref "OPAMP4_COMP5") (pin "7") (pinfunction "OUT_B_7") (pintype "output"))
      (node (ref "PAD11") (pin "1") (pinfunction "P_1") (pintype "passive"))
      (node (ref "U$3") (pin "53") (pinfunction "RIN_53") (pintype "bidirectional"))
    )
    (net (code "291") (name "P0A1_COMP1") (class "Default")
      (node (ref "10POT1_COMP1") (pin "5") (pinfunction "P0A_5") (pintype "bidirectional"))
      (node (ref "R76") (pin "2") (pinfunction "2_2") (pintype "passive"))
    )
    (net (code "292") (name "P0A1_COMP2") (class "Default")
      (node (ref "10POT1_COMP3") (pin "5") (pinfunction "P0A_5") (pintype "bidirectional"))
      (node (ref "R119") (pin "2") (pinfunction "2_2") (pintype "passive"))
    )
    (net (code "293") (name "P0A1_COMP3") (class "Default")
      (node (ref "10POT1_COMP2") (pin "5") (pinfunction "P0A_5") (pintype "bidirectional"))
      (node (ref "R101") (pin "2") (pinfunction "2_2") (pintype "passive"))
    )
    (net (code "294") (name "P0A1_COMP4") (class "Default")
      (node (ref "10POT1_COMP5") (pin "5") (pinfunction "P0A_5") (pintype "bidirectional"))
      (node (ref "R155") (pin "2") (pinfunction "2_2") (pintype "passive"))
    )
    (net (code "295") (name "P0A2_COMP1") (class "Default")
      (node (ref "10POT2_COMP1") (pin "5") (pinfunction "P0A_5") (pintype "bidirectional"))
      (node (ref "R92") (pin "1") (pinfunction "1_1") (pintype "passive"))
    )
    (net (code "296") (name "P0A2_COMP2") (class "Default")
      (node (ref "10POT2_COMP3") (pin "5") (pinfunction "P0A_5") (pintype "bidirectional"))
      (node (ref "R128") (pin "1") (pinfunction "1_1") (pintype "passive"))
    )
    (net (code "297") (name "P0A2_COMP3") (class "Default")
      (node (ref "10POT2_COMP2") (pin "5") (pinfunction "P0A_5") (pintype "bidirectional"))
      (node (ref "R110") (pin "1") (pinfunction "1_1") (pintype "passive"))
    )
    (net (code "298") (name "P0A2_COMP4") (class "Default")
      (node (ref "10POT2_COMP5") (pin "5") (pinfunction "P0A_5") (pintype "bidirectional"))
      (node (ref "R164") (pin "1") (pinfunction "1_1") (pintype "passive"))
    )
    (net (code "299") (name "P0A_PAN1") (class "Default")
      (node (ref "10KPOT1_PAN1") (pin "5") (pinfunction "P0A_5") (pintype "bidirectional"))
      (node (ref "R70") (pin "1") (pinfunction "1_1") (pintype "passive"))
      (node (ref "R71") (pin "2") (pinfunction "2_2") (pintype "passive"))
    )
    (net (code "300") (name "P0A_PAN2") (class "Default")
      (node (ref "10KPOT1_PAN3") (pin "5") (pinfunction "P0A_5") (pintype "bidirectional"))
      (node (ref "R84") (pin "1") (pinfunction "1_1") (pintype "passive"))
      (node (ref "R85") (pin "2") (pinfunction "2_2") (pintype "passive"))
    )
    (net (code "301") (name "P0A_PAN3") (class "Default")
      (node (ref "10KPOT1_PAN2") (pin "5") (pinfunction "P0A_5") (pintype "bidirectional"))
      (node (ref "R10") (pin "1") (pinfunction "1_1") (pintype "passive"))
      (node (ref "R11") (pin "2") (pinfunction "2_2") (pintype "passive"))
    )
    (net (code "302") (name "P0A_PAN4") (class "Default")
      (node (ref "10KPOT1_PAN4") (pin "5") (pinfunction "P0A_5") (pintype "bidirectional"))
      (node (ref "R17") (pin "1") (pinfunction "1_1") (pintype "passive"))
      (node (ref "R18") (pin "2") (pinfunction "2_2") (pintype "passive"))
    )
    (net (code "303") (name "P0B_PAN1") (class "Default")
      (node (ref "10KPOT1_PAN1") (pin "7") (pinfunction "P0B_7") (pintype "bidirectional"))
      (node (ref "R69") (pin "1") (pinfunction "1_1") (pintype "passive"))
      (node (ref "R73") (pin "1") (pinfunction "1_1") (pintype "passive"))
    )
    (net (code "304") (name "P0B_PAN2") (class "Default")
      (node (ref "10KPOT1_PAN3") (pin "7") (pinfunction "P0B_7") (pintype "bidirectional"))
      (node (ref "R83") (pin "1") (pinfunction "1_1") (pintype "passive"))
      (node (ref "R87") (pin "1") (pinfunction "1_1") (pintype "passive"))
    )
    (net (code "305") (name "P0B_PAN3") (class "Default")
      (node (ref "10KPOT1_PAN2") (pin "7") (pinfunction "P0B_7") (pintype "bidirectional"))
      (node (ref "R13") (pin "1") (pinfunction "1_1") (pintype "passive"))
      (node (ref "R7") (pin "1") (pinfunction "1_1") (pintype "passive"))
    )
    (net (code "306") (name "P0B_PAN4") (class "Default")
      (node (ref "10KPOT1_PAN4") (pin "7") (pinfunction "P0B_7") (pintype "bidirectional"))
      (node (ref "R16") (pin "1") (pinfunction "1_1") (pintype "passive"))
      (node (ref "R20") (pin "1") (pinfunction "1_1") (pintype "passive"))
    )
    (net (code "307") (name "P0W1_COMP1") (class "Default")
      (node (ref "10POT1_COMP1") (pin "6") (pinfunction "P0W_6") (pintype "bidirectional"))
      (node (ref "R67") (pin "1") (pinfunction "1_1") (pintype "passive"))
    )
    (net (code "308") (name "P0W1_COMP2") (class "Default")
      (node (ref "10POT1_COMP3") (pin "6") (pinfunction "P0W_6") (pintype "bidirectional"))
      (node (ref "R117") (pin "1") (pinfunction "1_1") (pintype "passive"))
    )
    (net (code "309") (name "P0W1_COMP3") (class "Default")
      (node (ref "10POT1_COMP2") (pin "6") (pinfunction "P0W_6") (pintype "bidirectional"))
      (node (ref "R99") (pin "1") (pinfunction "1_1") (pintype "passive"))
    )
    (net (code "310") (name "P0W1_COMP4") (class "Default")
      (node (ref "10POT1_COMP5") (pin "6") (pinfunction "P0W_6") (pintype "bidirectional"))
      (node (ref "R153") (pin "1") (pinfunction "1_1") (pintype "passive"))
    )
    (net (code "311") (name "P0W_PAN1") (class "Default")
      (node (ref "10KPOT1_PAN1") (pin "6") (pinfunction "P0W_6") (pintype "bidirectional"))
      (node (ref "D2") (pin "1") (pinfunction "1_1") (pintype "passive"))
    )
    (net (code "312") (name "P0W_PAN2") (class "Default")
      (node (ref "10KPOT1_PAN3") (pin "6") (pinfunction "P0W_6") (pintype "bidirectional"))
      (node (ref "D4") (pin "1") (pinfunction "1_1") (pintype "passive"))
    )
    (net (code "313") (name "P0W_PAN3") (class "Default")
      (node (ref "10KPOT1_PAN2") (pin "6") (pinfunction "P0W_6") (pintype "bidirectional"))
      (node (ref "D3") (pin "1") (pinfunction "1_1") (pintype "passive"))
    )
    (net (code "314") (name "P0W_PAN4") (class "Default")
      (node (ref "10KPOT1_PAN4") (pin "6") (pinfunction "P0W_6") (pintype "bidirectional"))
      (node (ref "D5") (pin "1") (pinfunction "1_1") (pintype "passive"))
    )
    (net (code "315") (name "POS_A1_COMP1") (class "Default")
      (node (ref "100POT1_COMP1") (pin "9") (pinfunction "PW0_9") (pintype "passive"))
      (node (ref "OPAMP1_COMP1") (pin "3") (pinfunction "POS_A_3") (pintype "input"))
    )
    (net (code "316") (name "POS_A1_COMP2") (class "Default")
      (node (ref "100POT1_COMP3") (pin "9") (pinfunction "PW0_9") (pintype "passive"))
      (node (ref "OPAMP1_COMP3") (pin "3") (pinfunction "POS_A_3") (pintype "input"))
    )
    (net (code "317") (name "POS_A1_COMP3") (class "Default")
      (node (ref "100POT1_COMP2") (pin "9") (pinfunction "PW0_9") (pintype "passive"))
      (node (ref "OPAMP1_COMP2") (pin "3") (pinfunction "POS_A_3") (pintype "input"))
    )
    (net (code "318") (name "POS_A1_COMP4") (class "Default")
      (node (ref "100POT1_COMP5") (pin "9") (pinfunction "PW0_9") (pintype "passive"))
      (node (ref "OPAMP1_COMP5") (pin "3") (pinfunction "POS_A_3") (pintype "input"))
    )
    (net (code "319") (name "POS_A2_COMP1") (class "Default")
      (node (ref "OPAMP2_COMP1") (pin "3") (pinfunction "POS_A_3") (pintype "input"))
      (node (ref "R64") (pin "2") (pinfunction "2_2") (pintype "passive"))
      (node (ref "R66") (pin "2") (pinfunction "2_2") (pintype "passive"))
    )
    (net (code "320") (name "POS_A2_COMP2") (class "Default")
      (node (ref "OPAMP2_COMP3") (pin "3") (pinfunction "POS_A_3") (pintype "input"))
      (node (ref "R114") (pin "2") (pinfunction "2_2") (pintype "passive"))
      (node (ref "R116") (pin "2") (pinfunction "2_2") (pintype "passive"))
    )
    (net (code "321") (name "POS_A2_COMP3") (class "Default")
      (node (ref "OPAMP2_COMP2") (pin "3") (pinfunction "POS_A_3") (pintype "input"))
      (node (ref "R96") (pin "2") (pinfunction "2_2") (pintype "passive"))
      (node (ref "R98") (pin "2") (pinfunction "2_2") (pintype "passive"))
    )
    (net (code "322") (name "POS_A2_COMP4") (class "Default")
      (node (ref "OPAMP2_COMP5") (pin "3") (pinfunction "POS_A_3") (pintype "input"))
      (node (ref "R150") (pin "2") (pinfunction "2_2") (pintype "passive"))
      (node (ref "R152") (pin "2") (pinfunction "2_2") (pintype "passive"))
    )
    (net (code "323") (name "POS_A4_COMP1") (class "Default")
      (node (ref "D22") (pin "2") (pinfunction "2_2") (pintype "passive"))
      (node (ref "D23") (pin "1") (pinfunction "1_1") (pintype "passive"))
      (node (ref "OPAMP4_COMP1") (pin "3") (pinfunction "POS_A_3") (pintype "input"))
      (node (ref "R93") (pin "1") (pinfunction "1_1") (pintype "passive"))
    )
    (net (code "324") (name "POS_A4_COMP2") (class "Default")
      (node (ref "D44") (pin "2") (pinfunction "2_2") (pintype "passive"))
      (node (ref "D45") (pin "1") (pinfunction "1_1") (pintype "passive"))
      (node (ref "OPAMP4_COMP3") (pin "3") (pinfunction "POS_A_3") (pintype "input"))
      (node (ref "R129") (pin "1") (pinfunction "1_1") (pintype "passive"))
    )
    (net (code "325") (name "POS_A4_COMP3") (class "Default")
      (node (ref "D33") (pin "2") (pinfunction "2_2") (pintype "passive"))
      (node (ref "D34") (pin "1") (pinfunction "1_1") (pintype "passive"))
      (node (ref "OPAMP4_COMP2") (pin "3") (pinfunction "POS_A_3") (pintype "input"))
      (node (ref "R111") (pin "1") (pinfunction "1_1") (pintype "passive"))
    )
    (net (code "326") (name "POS_A4_COMP4") (class "Default")
      (node (ref "D66") (pin "2") (pinfunction "2_2") (pintype "passive"))
      (node (ref "D67") (pin "1") (pinfunction "1_1") (pintype "passive"))
      (node (ref "OPAMP4_COMP5") (pin "3") (pinfunction "POS_A_3") (pintype "input"))
      (node (ref "R165") (pin "1") (pinfunction "1_1") (pintype "passive"))
    )
    (net (code "327") (name "POS_B1_COMP1") (class "Default")
      (node (ref "D26") (pin "1") (pinfunction "1_1") (pintype "passive"))
      (node (ref "OPAMP1_COMP1") (pin "5") (pinfunction "POS_B_5") (pintype "input"))
      (node (ref "R77") (pin "2") (pinfunction "2_2") (pintype "passive"))
    )
    (net (code "328") (name "POS_B1_COMP2") (class "Default")
      (node (ref "D48") (pin "1") (pinfunction "1_1") (pintype "passive"))
      (node (ref "OPAMP1_COMP3") (pin "5") (pinfunction "POS_B_5") (pintype "input"))
      (node (ref "R120") (pin "2") (pinfunction "2_2") (pintype "passive"))
    )
    (net (code "329") (name "POS_B1_COMP3") (class "Default")
      (node (ref "D37") (pin "1") (pinfunction "1_1") (pintype "passive"))
      (node (ref "OPAMP1_COMP2") (pin "5") (pinfunction "POS_B_5") (pintype "input"))
      (node (ref "R102") (pin "2") (pinfunction "2_2") (pintype "passive"))
    )
    (net (code "330") (name "POS_B1_COMP4") (class "Default")
      (node (ref "D70") (pin "1") (pinfunction "1_1") (pintype "passive"))
      (node (ref "OPAMP1_COMP5") (pin "5") (pinfunction "POS_B_5") (pintype "input"))
      (node (ref "R156") (pin "2") (pinfunction "2_2") (pintype "passive"))
    )
    (net (code "331") (name "POS_B2_COMP1") (class "Default")
      (node (ref "10POT2_COMP1") (pin "6") (pinfunction "P0W_6") (pintype "bidirectional"))
      (node (ref "10POT2_COMP1") (pin "7") (pinfunction "P0B_7") (pintype "bidirectional"))
      (node (ref "OPAMP2_COMP1") (pin "5") (pinfunction "POS_B_5") (pintype "input"))
      (node (ref "R91") (pin "1") (pinfunction "1_1") (pintype "passive"))
    )
    (net (code "332") (name "POS_B2_COMP2") (class "Default")
      (node (ref "10POT2_COMP3") (pin "6") (pinfunction "P0W_6") (pintype "bidirectional"))
      (node (ref "10POT2_COMP3") (pin "7") (pinfunction "P0B_7") (pintype "bidirectional"))
      (node (ref "OPAMP2_COMP3") (pin "5") (pinfunction "POS_B_5") (pintype "input"))
      (node (ref "R127") (pin "1") (pinfunction "1_1") (pintype "passive"))
    )
    (net (code "333") (name "POS_B2_COMP3") (class "Default")
      (node (ref "10POT2_COMP2") (pin "6") (pinfunction "P0W_6") (pintype "bidirectional"))
      (node (ref "10POT2_COMP2") (pin "7") (pinfunction "P0B_7") (pintype "bidirectional"))
      (node (ref "OPAMP2_COMP2") (pin "5") (pinfunction "POS_B_5") (pintype "input"))
      (node (ref "R109") (pin "1") (pinfunction "1_1") (pintype "passive"))
    )
    (net (code "334") (name "POS_B2_COMP4") (class "Default")
      (node (ref "10POT2_COMP5") (pin "6") (pinfunction "P0W_6") (pintype "bidirectional"))
      (node (ref "10POT2_COMP5") (pin "7") (pinfunction "P0B_7") (pintype "bidirectional"))
      (node (ref "OPAMP2_COMP5") (pin "5") (pinfunction "POS_B_5") (pintype "input"))
      (node (ref "R163") (pin "1") (pinfunction "1_1") (pintype "passive"))
    )
    (net (code "335") (name "SCK") (class "Default")
      (node (ref "100POT1_COMP1") (pin "2") (pinfunction "SCK_2") (pintype "input"))
      (node (ref "100POT1_COMP2") (pin "2") (pinfunction "SCK_2") (pintype "input"))
      (node (ref "100POT1_COMP3") (pin "2") (pinfunction "SCK_2") (pintype "input"))
      (node (ref "100POT1_COMP5") (pin "2") (pinfunction "SCK_2") (pintype "input"))
      (node (ref "10KPOT1_PAN1") (pin "2") (pinfunction "SCK_2") (pintype "input"))
      (node (ref "10KPOT1_PAN2") (pin "2") (pinfunction "SCK_2") (pintype "input"))
      (node (ref "10KPOT1_PAN3") (pin "2") (pinfunction "SCK_2") (pintype "input"))
      (node (ref "10KPOT1_PAN4") (pin "2") (pinfunction "SCK_2") (pintype "input"))
      (node (ref "10POT1_COMP1") (pin "2") (pinfunction "SCK_2") (pintype "input"))
      (node (ref "10POT1_COMP2") (pin "2") (pinfunction "SCK_2") (pintype "input"))
      (node (ref "10POT1_COMP3") (pin "2") (pinfunction "SCK_2") (pintype "input"))
      (node (ref "10POT1_COMP5") (pin "2") (pinfunction "SCK_2") (pintype "input"))
      (node (ref "10POT2_COMP1") (pin "2") (pinfunction "SCK_2") (pintype "input"))
      (node (ref "10POT2_COMP2") (pin "2") (pinfunction "SCK_2") (pintype "input"))
      (node (ref "10POT2_COMP3") (pin "2") (pinfunction "SCK_2") (pintype "input"))
      (node (ref "10POT2_COMP5") (pin "2") (pinfunction "SCK_2") (pintype "input"))
      (node (ref "SCK1") (pin "1") (pinfunction "P_1") (pintype "passive"))
      (node (ref "U$1") (pin "25") (pinfunction "CL_25") (pintype "bidirectional"))
      (node (ref "U$3") (pin "25") (pinfunction "CL_25") (pintype "bidirectional"))
    )
    (net (code "336") (name "SCL") (class "Default")
      (node (ref "200POT1_COMP1") (pin "2") (pinfunction "SCL_2") (pintype "input"))
      (node (ref "200POT1_COMP2") (pin "2") (pinfunction "SCL_2") (pintype "input"))
      (node (ref "200POT1_COMP3") (pin "2") (pinfunction "SCL_2") (pintype "input"))
      (node (ref "200POT1_COMP5") (pin "2") (pinfunction "SCL_2") (pintype "input"))
      (node (ref "200POT2_COMP1") (pin "2") (pinfunction "SCL_2") (pintype "input"))
      (node (ref "200POT2_COMP2") (pin "2") (pinfunction "SCL_2") (pintype "input"))
      (node (ref "200POT2_COMP3") (pin "2") (pinfunction "SCL_2") (pintype "input"))
      (node (ref "200POT2_COMP5") (pin "2") (pinfunction "SCL_2") (pintype "input"))
      (node (ref "SCL1") (pin "1") (pinfunction "P_1") (pintype "passive"))
    )
    (net (code "337") (name "SCL1") (class "Default")
      (node (ref "IC2") (pin "24") (pinfunction "MC/SCL_24") (pintype "bidirectional"))
      (node (ref "SCL2") (pin "1") (pinfunction "P_1") (pintype "passive"))
    )
    (net (code "338") (name "SDA") (class "Default")
      (node (ref "200POT1_COMP1") (pin "3") (pinfunction "SDA_3") (pintype "input"))
      (node (ref "200POT1_COMP2") (pin "3") (pinfunction "SDA_3") (pintype "input"))
      (node (ref "200POT1_COMP3") (pin "3") (pinfunction "SDA_3") (pintype "input"))
      (node (ref "200POT1_COMP5") (pin "3") (pinfunction "SDA_3") (pintype "input"))
      (node (ref "200POT2_COMP1") (pin "3") (pinfunction "SDA_3") (pintype "input"))
      (node (ref "200POT2_COMP2") (pin "3") (pinfunction "SDA_3") (pintype "input"))
      (node (ref "200POT2_COMP3") (pin "3") (pinfunction "SDA_3") (pintype "input"))
      (node (ref "200POT2_COMP5") (pin "3") (pinfunction "SDA_3") (pintype "input"))
      (node (ref "SDA1") (pin "1") (pinfunction "P_1") (pintype "passive"))
    )
    (net (code "339") (name "SDA1") (class "Default")
      (node (ref "IC2") (pin "23") (pinfunction "MOSI/SDA_23") (pintype "bidirectional"))
      (node (ref "SDA2") (pin "1") (pinfunction "P_1") (pintype "passive"))
    )
    (net (code "340") (name "SDI{slash}O") (class "Default")
      (node (ref "100POT1_COMP1") (pin "3") (pinfunction "SI_3") (pintype "input"))
      (node (ref "100POT1_COMP2") (pin "3") (pinfunction "SI_3") (pintype "input"))
      (node (ref "100POT1_COMP3") (pin "3") (pinfunction "SI_3") (pintype "input"))
      (node (ref "100POT1_COMP5") (pin "3") (pinfunction "SI_3") (pintype "input"))
      (node (ref "10KPOT1_PAN1") (pin "3") (pinfunction "SDI/SDO_3") (pintype "bidirectional"))
      (node (ref "10KPOT1_PAN2") (pin "3") (pinfunction "SDI/SDO_3") (pintype "bidirectional"))
      (node (ref "10KPOT1_PAN3") (pin "3") (pinfunction "SDI/SDO_3") (pintype "bidirectional"))
      (node (ref "10KPOT1_PAN4") (pin "3") (pinfunction "SDI/SDO_3") (pintype "bidirectional"))
      (node (ref "10POT1_COMP1") (pin "3") (pinfunction "SDI/SDO_3") (pintype "bidirectional"))
      (node (ref "10POT1_COMP2") (pin "3") (pinfunction "SDI/SDO_3") (pintype "bidirectional"))
      (node (ref "10POT1_COMP3") (pin "3") (pinfunction "SDI/SDO_3") (pintype "bidirectional"))
      (node (ref "10POT1_COMP5") (pin "3") (pinfunction "SDI/SDO_3") (pintype "bidirectional"))
      (node (ref "10POT2_COMP1") (pin "3") (pinfunction "SDI/SDO_3") (pintype "bidirectional"))
      (node (ref "10POT2_COMP2") (pin "3") (pinfunction "SDI/SDO_3") (pintype "bidirectional"))
      (node (ref "10POT2_COMP3") (pin "3") (pinfunction "SDI/SDO_3") (pintype "bidirectional"))
      (node (ref "10POT2_COMP5") (pin "3") (pinfunction "SDI/SDO_3") (pintype "bidirectional"))
      (node (ref "SDI/O1") (pin "1") (pinfunction "P_1") (pintype "passive"))
      (node (ref "U$1") (pin "26") (pinfunction "DI_26") (pintype "bidirectional"))
      (node (ref "U$3") (pin "26") (pinfunction "DI_26") (pintype "bidirectional"))
    )
    (net (code "341") (name "VDD") (class "Default")
      (node (ref "9VDD1") (pin "1") (pinfunction "P_1") (pintype "passive"))
      (node (ref "OPAMP1_COMP1") (pin "8") (pinfunction "V+_8") (pintype "power_in"))
      (node (ref "OPAMP1_COMP2") (pin "8") (pinfunction "V+_8") (pintype "power_in"))
      (node (ref "OPAMP1_COMP3") (pin "8") (pinfunction "V+_8") (pintype "power_in"))
      (node (ref "OPAMP1_COMP5") (pin "8") (pinfunction "V+_8") (pintype "power_in"))
      (node (ref "OPAMP1_MIX1") (pin "8") (pinfunction "V+_8") (pintype "power_in"))
      (node (ref "OPAMP1_PAN1") (pin "8") (pinfunction "V+_8") (pintype "power_in"))
      (node (ref "OPAMP1_PAN2") (pin "8") (pinfunction "V+_8") (pintype "power_in"))
      (node (ref "OPAMP1_PAN3") (pin "8") (pinfunction "V+_8") (pintype "power_in"))
      (node (ref "OPAMP1_PAN4") (pin "8") (pinfunction "V+_8") (pintype "power_in"))
      (node (ref "OPAMP2_COMP1") (pin "8") (pinfunction "V+_8") (pintype "power_in"))
      (node (ref "OPAMP2_COMP2") (pin "8") (pinfunction "V+_8") (pintype "power_in"))
      (node (ref "OPAMP2_COMP3") (pin "8") (pinfunction "V+_8") (pintype "power_in"))
      (node (ref "OPAMP2_COMP5") (pin "8") (pinfunction "V+_8") (pintype "power_in"))
      (node (ref "OPAMP3_COMP1") (pin "8") (pinfunction "V+_8") (pintype "power_in"))
      (node (ref "OPAMP3_COMP2") (pin "8") (pinfunction "V+_8") (pintype "power_in"))
      (node (ref "OPAMP3_COMP3") (pin "8") (pinfunction "V+_8") (pintype "power_in"))
      (node (ref "OPAMP3_COMP5") (pin "8") (pinfunction "V+_8") (pintype "power_in"))
      (node (ref "OPAMP4_COMP1") (pin "8") (pinfunction "V+_8") (pintype "power_in"))
      (node (ref "OPAMP4_COMP2") (pin "8") (pinfunction "V+_8") (pintype "power_in"))
      (node (ref "OPAMP4_COMP3") (pin "8") (pinfunction "V+_8") (pintype "power_in"))
      (node (ref "OPAMP4_COMP5") (pin "8") (pinfunction "V+_8") (pintype "power_in"))
      (node (ref "R101") (pin "1") (pinfunction "1_1") (pintype "passive"))
      (node (ref "R119") (pin "1") (pinfunction "1_1") (pintype "passive"))
      (node (ref "R155") (pin "1") (pinfunction "1_1") (pintype "passive"))
      (node (ref "R22") (pin "1") (pinfunction "1_1") (pintype "passive"))
      (node (ref "R76") (pin "1") (pinfunction "1_1") (pintype "passive"))
      (node (ref "R8") (pin "1") (pinfunction "1_1") (pintype "passive"))
      (node (ref "U$1") (pin "22") (pinfunction "V_DD_22") (pintype "bidirectional"))
      (node (ref "U$3") (pin "22") (pinfunction "V_DD_22") (pintype "bidirectional"))
      (node (ref "U2") (pin "8") (pinfunction "V+_8") (pintype "power_in"))
    )
    (net (code "342") (name "VREF") (class "Default")
      (node (ref "100POT1_COMP1") (pin "11") (pinfunction "~{RS}_11") (pintype "input"))
      (node (ref "100POT1_COMP1") (pin "12") (pinfunction "~{SHDN}_12") (pintype "input"))
      (node (ref "100POT1_COMP1") (pin "14") (pinfunction "VDD_14") (pintype "power_in"))
      (node (ref "100POT1_COMP1") (pin "8") (pinfunction "PA0_8") (pintype "passive"))
      (node (ref "100POT1_COMP2") (pin "11") (pinfunction "~{RS}_11") (pintype "input"))
      (node (ref "100POT1_COMP2") (pin "12") (pinfunction "~{SHDN}_12") (pintype "input"))
      (node (ref "100POT1_COMP2") (pin "14") (pinfunction "VDD_14") (pintype "power_in"))
      (node (ref "100POT1_COMP2") (pin "8") (pinfunction "PA0_8") (pintype "passive"))
      (node (ref "100POT1_COMP3") (pin "11") (pinfunction "~{RS}_11") (pintype "input"))
      (node (ref "100POT1_COMP3") (pin "12") (pinfunction "~{SHDN}_12") (pintype "input"))
      (node (ref "100POT1_COMP3") (pin "14") (pinfunction "VDD_14") (pintype "power_in"))
      (node (ref "100POT1_COMP3") (pin "8") (pinfunction "PA0_8") (pintype "passive"))
      (node (ref "100POT1_COMP5") (pin "11") (pinfunction "~{RS}_11") (pintype "input"))
      (node (ref "100POT1_COMP5") (pin "12") (pinfunction "~{SHDN}_12") (pintype "input"))
      (node (ref "100POT1_COMP5") (pin "14") (pinfunction "VDD_14") (pintype "power_in"))
      (node (ref "100POT1_COMP5") (pin "8") (pinfunction "PA0_8") (pintype "passive"))
      (node (ref "10KPOT1_PAN1") (pin "8") (pinfunction "VDD_8") (pintype "power_in"))
      (node (ref "10KPOT1_PAN2") (pin "8") (pinfunction "VDD_8") (pintype "power_in"))
      (node (ref "10KPOT1_PAN3") (pin "8") (pinfunction "VDD_8") (pintype "power_in"))
      (node (ref "10KPOT1_PAN4") (pin "8") (pinfunction "VDD_8") (pintype "power_in"))
      (node (ref "10POT1_COMP1") (pin "7") (pinfunction "P0B_7") (pintype "bidirectional"))
      (node (ref "10POT1_COMP1") (pin "8") (pinfunction "VDD_8") (pintype "power_in"))
      (node (ref "10POT1_COMP2") (pin "7") (pinfunction "P0B_7") (pintype "bidirectional"))
      (node (ref "10POT1_COMP2") (pin "8") (pinfunction "VDD_8") (pintype "power_in"))
      (node (ref "10POT1_COMP3") (pin "7") (pinfunction "P0B_7") (pintype "bidirectional"))
      (node (ref "10POT1_COMP3") (pin "8") (pinfunction "VDD_8") (pintype "power_in"))
      (node (ref "10POT1_COMP5") (pin "7") (pinfunction "P0B_7") (pintype "bidirectional"))
      (node (ref "10POT1_COMP5") (pin "8") (pinfunction "VDD_8") (pintype "power_in"))
      (node (ref "10POT2_COMP1") (pin "8") (pinfunction "VDD_8") (pintype "power_in"))
      (node (ref "10POT2_COMP2") (pin "8") (pinfunction "VDD_8") (pintype "power_in"))
      (node (ref "10POT2_COMP3") (pin "8") (pinfunction "VDD_8") (pintype "power_in"))
      (node (ref "10POT2_COMP5") (pin "8") (pinfunction "VDD_8") (pintype "power_in"))
      (node (ref "200POT1_COMP1") (pin "1") (pinfunction "VDD_1") (pintype "power_in"))
      (node (ref "200POT1_COMP1") (pin "4") (pinfunction "A0_4") (pintype "input"))
      (node (ref "200POT1_COMP2") (pin "1") (pinfunction "VDD_1") (pintype "power_in"))
      (node (ref "200POT1_COMP2") (pin "4") (pinfunction "A0_4") (pintype "input"))
      (node (ref "200POT1_COMP3") (pin "1") (pinfunction "VDD_1") (pintype "power_in"))
      (node (ref "200POT1_COMP3") (pin "4") (pinfunction "A0_4") (pintype "input"))
      (node (ref "200POT1_COMP5") (pin "1") (pinfunction "VDD_1") (pintype "power_in"))
      (node (ref "200POT1_COMP5") (pin "4") (pinfunction "A0_4") (pintype "input"))
      (node (ref "200POT2_COMP1") (pin "1") (pinfunction "VDD_1") (pintype "power_in"))
      (node (ref "200POT2_COMP2") (pin "1") (pinfunction "VDD_1") (pintype "power_in"))
      (node (ref "200POT2_COMP3") (pin "1") (pinfunction "VDD_1") (pintype "power_in"))
      (node (ref "200POT2_COMP5") (pin "1") (pinfunction "VDD_1") (pintype "power_in"))
      (node (ref "C44") (pin "2") (pinfunction "2_2") (pintype "passive"))
      (node (ref "C47") (pin "2") (pinfunction "2_2") (pintype "passive"))
      (node (ref "C50") (pin "2") (pinfunction "2_2") (pintype "passive"))
      (node (ref "C56") (pin "2") (pinfunction "2_2") (pintype "passive"))
      (node (ref "D2") (pin "2") (pinfunction "2_2") (pintype "passive"))
      (node (ref "D3") (pin "2") (pinfunction "2_2") (pintype "passive"))
      (node (ref "D4") (pin "2") (pinfunction "2_2") (pintype "passive"))
      (node (ref "D5") (pin "2") (pinfunction "2_2") (pintype "passive"))
      (node (ref "OPAMP1_MIX1") (pin "3") (pinfunction "POS_A_3") (pintype "input"))
      (node (ref "OPAMP1_MIX1") (pin "5") (pinfunction "POS_B_5") (pintype "input"))
      (node (ref "OPAMP1_PAN1") (pin "3") (pinfunction "POS_A_3") (pintype "input"))
      (node (ref "OPAMP1_PAN1") (pin "5") (pinfunction "POS_B_5") (pintype "input"))
      (node (ref "OPAMP1_PAN2") (pin "3") (pinfunction "POS_A_3") (pintype "input"))
      (node (ref "OPAMP1_PAN2") (pin "5") (pinfunction "POS_B_5") (pintype "input"))
      (node (ref "OPAMP1_PAN3") (pin "3") (pinfunction "POS_A_3") (pintype "input"))
      (node (ref "OPAMP1_PAN3") (pin "5") (pinfunction "POS_B_5") (pintype "input"))
      (node (ref "OPAMP1_PAN4") (pin "3") (pinfunction "POS_A_3") (pintype "input"))
      (node (ref "OPAMP1_PAN4") (pin "5") (pinfunction "POS_B_5") (pintype "input"))
      (node (ref "OPAMP3_COMP1") (pin "3") (pinfunction "POS_A_3") (pintype "input"))
      (node (ref "OPAMP3_COMP1") (pin "5") (pinfunction "POS_B_5") (pintype "input"))
      (node (ref "OPAMP3_COMP2") (pin "3") (pinfunction "POS_A_3") (pintype "input"))
      (node (ref "OPAMP3_COMP2") (pin "5") (pinfunction "POS_B_5") (pintype "input"))
      (node (ref "OPAMP3_COMP3") (pin "3") (pinfunction "POS_A_3") (pintype "input"))
      (node (ref "OPAMP3_COMP3") (pin "5") (pinfunction "POS_B_5") (pintype "input"))
      (node (ref "OPAMP3_COMP5") (pin "3") (pinfunction "POS_A_3") (pintype "input"))
      (node (ref "OPAMP3_COMP5") (pin "5") (pinfunction "POS_B_5") (pintype "input"))
      (node (ref "R105") (pin "1") (pinfunction "1_1") (pintype "passive"))
      (node (ref "R106") (pin "1") (pinfunction "1_1") (pintype "passive"))
      (node (ref "R110") (pin "2") (pinfunction "2_2") (pintype "passive"))
      (node (ref "R112") (pin "1") (pinfunction "1_1") (pintype "passive"))
      (node (ref "R113") (pin "1") (pinfunction "1_1") (pintype "passive"))
      (node (ref "R114") (pin "1") (pinfunction "1_1") (pintype "passive"))
      (node (ref "R123") (pin "1") (pinfunction "1_1") (pintype "passive"))
      (node (ref "R124") (pin "1") (pinfunction "1_1") (pintype "passive"))
      (node (ref "R128") (pin "2") (pinfunction "2_2") (pintype "passive"))
      (node (ref "R130") (pin "1") (pinfunction "1_1") (pintype "passive"))
      (node (ref "R149") (pin "1") (pinfunction "1_1") (pintype "passive"))
      (node (ref "R15") (pin "1") (pinfunction "1_1") (pintype "passive"))
      (node (ref "R150") (pin "1") (pinfunction "1_1") (pintype "passive"))
      (node (ref "R159") (pin "1") (pinfunction "1_1") (pintype "passive"))
      (node (ref "R160") (pin "1") (pinfunction "1_1") (pintype "passive"))
      (node (ref "R164") (pin "2") (pinfunction "2_2") (pintype "passive"))
      (node (ref "R166") (pin "1") (pinfunction "1_1") (pintype "passive"))
      (node (ref "R35") (pin "1") (pinfunction "1_1") (pintype "passive"))
      (node (ref "R36") (pin "2") (pinfunction "2_2") (pintype "passive"))
      (node (ref "R37") (pin "2") (pinfunction "2_2") (pintype "passive"))
      (node (ref "R38") (pin "2") (pinfunction "2_2") (pintype "passive"))
      (node (ref "R50") (pin "1") (pinfunction "1_1") (pintype "passive"))
      (node (ref "R51") (pin "2") (pinfunction "2_2") (pintype "passive"))
      (node (ref "R52") (pin "2") (pinfunction "2_2") (pintype "passive"))
      (node (ref "R53") (pin "2") (pinfunction "2_2") (pintype "passive"))
      (node (ref "R6") (pin "1") (pinfunction "1_1") (pintype "passive"))
      (node (ref "R63") (pin "1") (pinfunction "1_1") (pintype "passive"))
      (node (ref "R64") (pin "1") (pinfunction "1_1") (pintype "passive"))
      (node (ref "R68") (pin "1") (pinfunction "1_1") (pintype "passive"))
      (node (ref "R80") (pin "1") (pinfunction "1_1") (pintype "passive"))
      (node (ref "R81") (pin "1") (pinfunction "1_1") (pintype "passive"))
      (node (ref "R82") (pin "1") (pinfunction "1_1") (pintype "passive"))
      (node (ref "R92") (pin "2") (pinfunction "2_2") (pintype "passive"))
      (node (ref "R94") (pin "1") (pinfunction "1_1") (pintype "passive"))
      (node (ref "R95") (pin "1") (pinfunction "1_1") (pintype "passive"))
      (node (ref "R96") (pin "1") (pinfunction "1_1") (pintype "passive"))
      (node (ref "U2") (pin "6") (pinfunction "NEG_B_6") (pintype "input"))
      (node (ref "U2") (pin "7") (pinfunction "OUT_B_7") (pintype "output"))
    )
    (net (code "343") (name "unconnected-(100POT1_COMP1-SO-Pad13)") (class "Default")
      (node (ref "100POT1_COMP1") (pin "13") (pinfunction "SO_13") (pintype "output"))
    )
    (net (code "344") (name "unconnected-(100POT1_COMP2-SO-Pad13)") (class "Default")
      (node (ref "100POT1_COMP2") (pin "13") (pinfunction "SO_13") (pintype "output"))
    )
    (net (code "345") (name "unconnected-(100POT1_COMP3-SO-Pad13)") (class "Default")
      (node (ref "100POT1_COMP3") (pin "13") (pinfunction "SO_13") (pintype "output"))
    )
    (net (code "346") (name "unconnected-(100POT1_COMP5-SO-Pad13)") (class "Default")
      (node (ref "100POT1_COMP5") (pin "13") (pinfunction "SO_13") (pintype "output"))
    )
    (net (code "347") (name "unconnected-(IC2-GPIO1{slash}INTA{slash}DMIN-Pad21)") (class "Default")
      (node (ref "IC2") (pin "21") (pinfunction "GPIO1/INTA/DMIN_21") (pintype "bidirectional"))
    )
    (net (code "348") (name "unconnected-(IC2-GPIO1{slash}INTB{slash}DMCLK-Pad20)") (class "Default")
      (node (ref "IC2") (pin "20") (pinfunction "GPIO1/INTB/DMCLK_20") (pintype "bidirectional"))
    )
    (net (code "349") (name "unconnected-(IC2-GPIO3{slash}INTC-Pad19)") (class "Default")
      (node (ref "IC2") (pin "19") (pinfunction "GPIO3/INTC_19") (pintype "bidirectional"))
    )
    (net (code "350") (name "unconnected-(IC2-MD0-Pad26)") (class "Default")
      (node (ref "IC2") (pin "26") (pinfunction "MD0_26") (pintype "bidirectional"))
    )
    (net (code "351") (name "unconnected-(IC2-MIC_BIAS-Pad5)") (class "Default")
      (node (ref "IC2") (pin "5") (pinfunction "MIC_BIAS_5") (pintype "bidirectional"))
    )
    (net (code "352") (name "unconnected-(IC2-MISO{slash}GPIO0{slash}DMIN2-Pad22)") (class "Default")
      (node (ref "IC2") (pin "22") (pinfunction "MISO/GPIO0/DMIN2_22") (pintype "bidirectional"))
    )
    (net (code "353") (name "unconnected-(U$1-NC-Pad20)") (class "Default")
      (node (ref "U$1") (pin "20") (pinfunction "NC_20") (pintype "bidirectional"))
    )
    (net (code "354") (name "unconnected-(U$1-NC-Pad24)") (class "Default")
      (node (ref "U$1") (pin "24") (pinfunction "NC_24") (pintype "bidirectional"))
    )
    (net (code "355") (name "unconnected-(U$1-NC-Pad29)") (class "Default")
      (node (ref "U$1") (pin "29") (pinfunction "NC_29") (pintype "bidirectional"))
    )
    (net (code "356") (name "unconnected-(U$1-NC-Pad56)") (class "Default")
      (node (ref "U$1") (pin "56") (pinfunction "NC_56") (pintype "bidirectional"))
    )
    (net (code "357") (name "unconnected-(U$1-NC-Pad57)") (class "Default")
      (node (ref "U$1") (pin "57") (pinfunction "NC_57") (pintype "bidirectional"))
    )
    (net (code "358") (name "unconnected-(U$3-NC-Pad20)") (class "Default")
      (node (ref "U$3") (pin "20") (pinfunction "NC_20") (pintype "bidirectional"))
    )
    (net (code "359") (name "unconnected-(U$3-NC-Pad24)") (class "Default")
      (node (ref "U$3") (pin "24") (pinfunction "NC_24") (pintype "bidirectional"))
    )
    (net (code "360") (name "unconnected-(U$3-NC-Pad29)") (class "Default")
      (node (ref "U$3") (pin "29") (pinfunction "NC_29") (pintype "bidirectional"))
    )
    (net (code "361") (name "unconnected-(U$3-NC-Pad56)") (class "Default")
      (node (ref "U$3") (pin "56") (pinfunction "NC_56") (pintype "bidirectional"))
    )
    (net (code "362") (name "unconnected-(U$3-NC-Pad57)") (class "Default")
      (node (ref "U$3") (pin "57") (pinfunction "NC_57") (pintype "bidirectional"))
    )
  )
)
